# pc_badge_hrv_v1_1.net
KiCad netlist of a schematic drawn in EAGLE
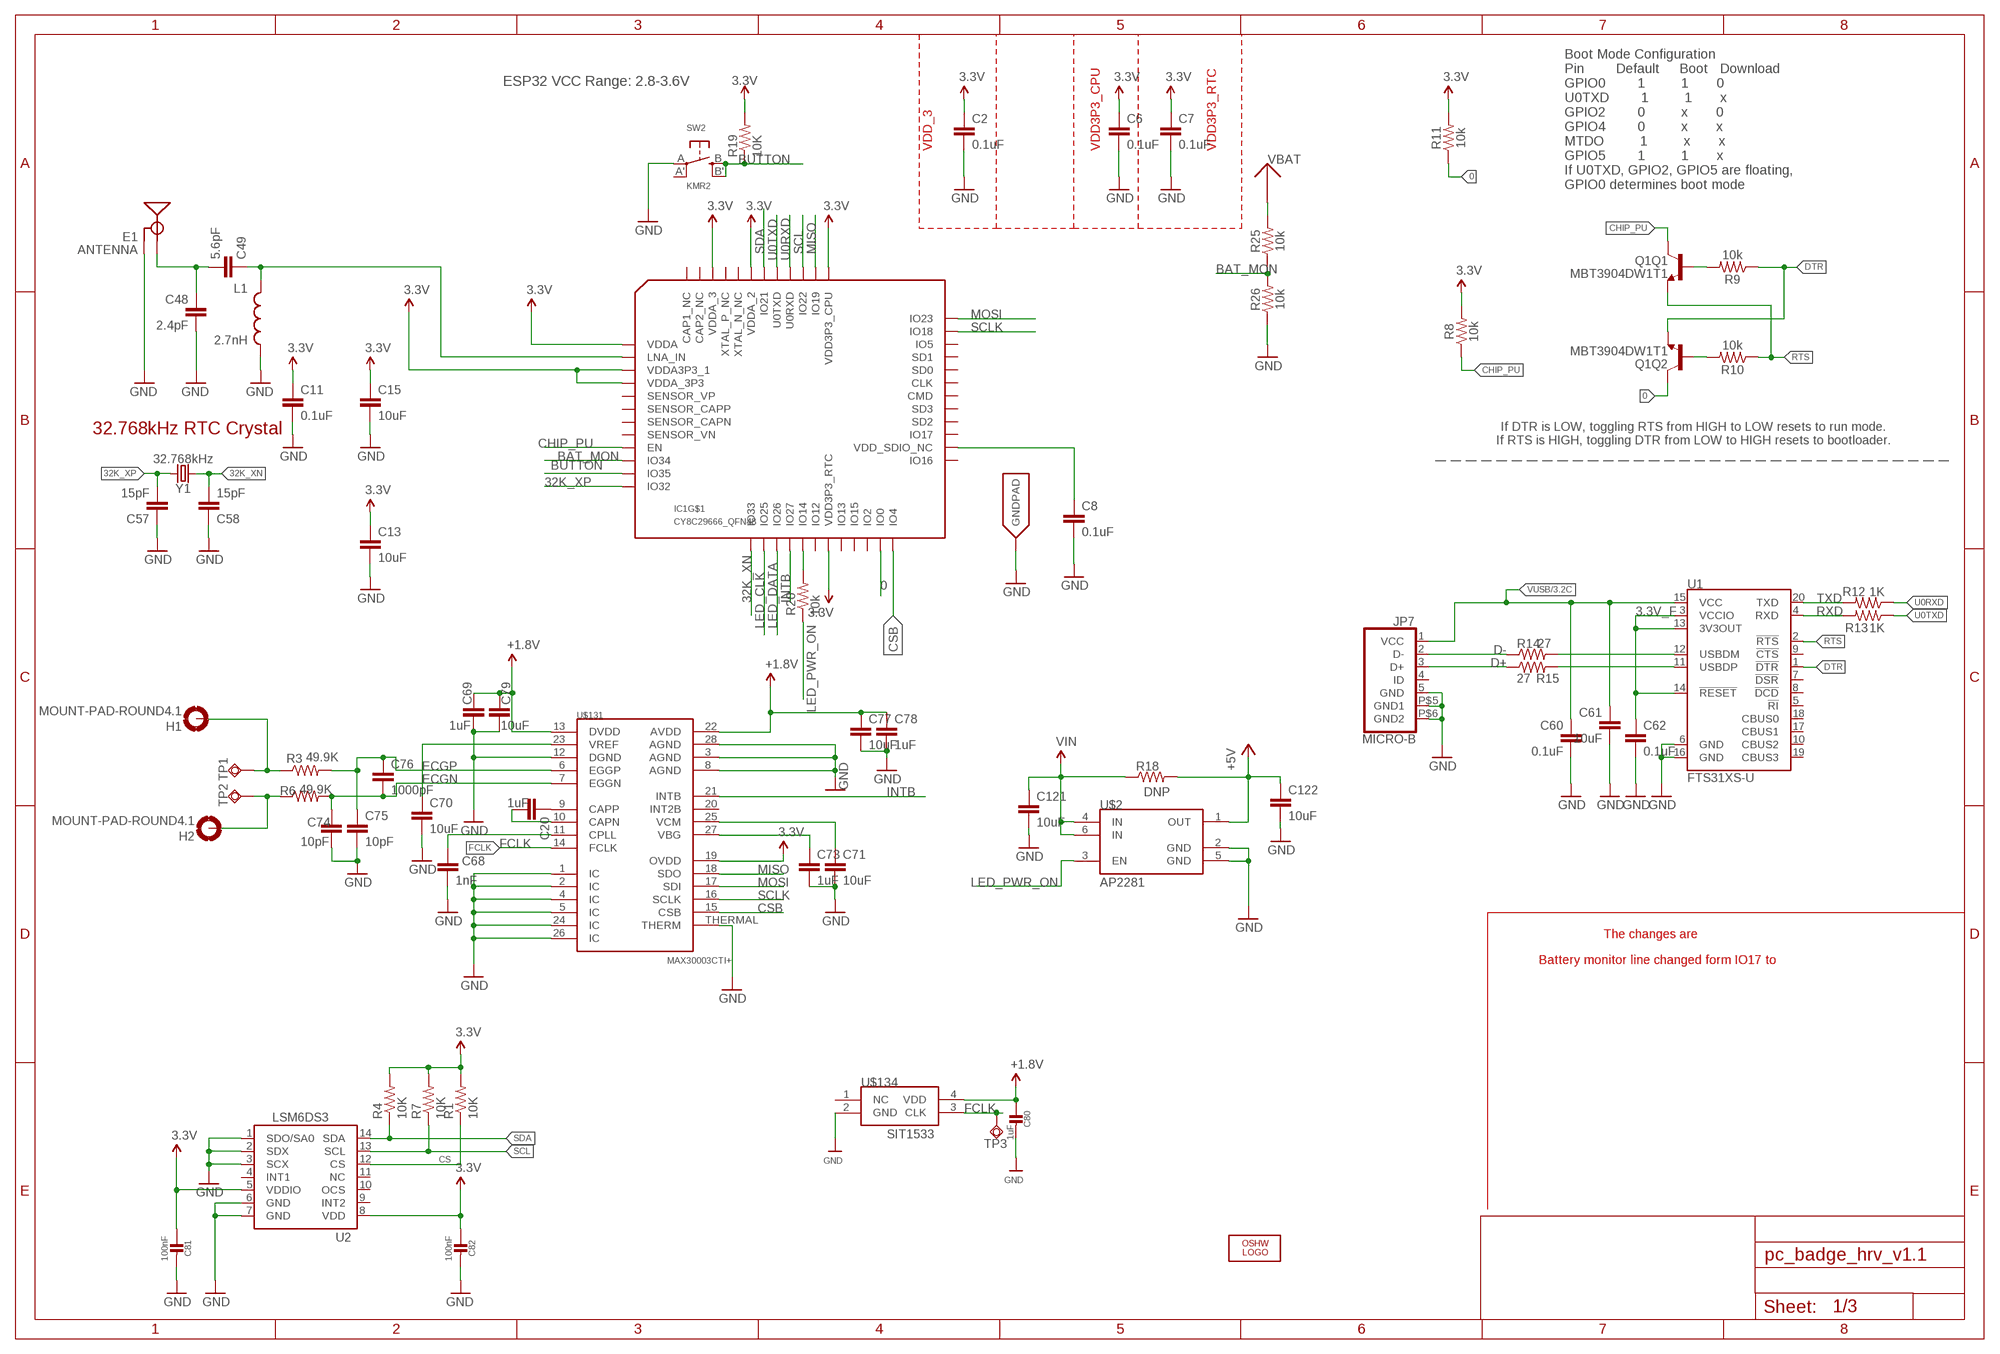
[diagram p0: schematic, sheet 1]
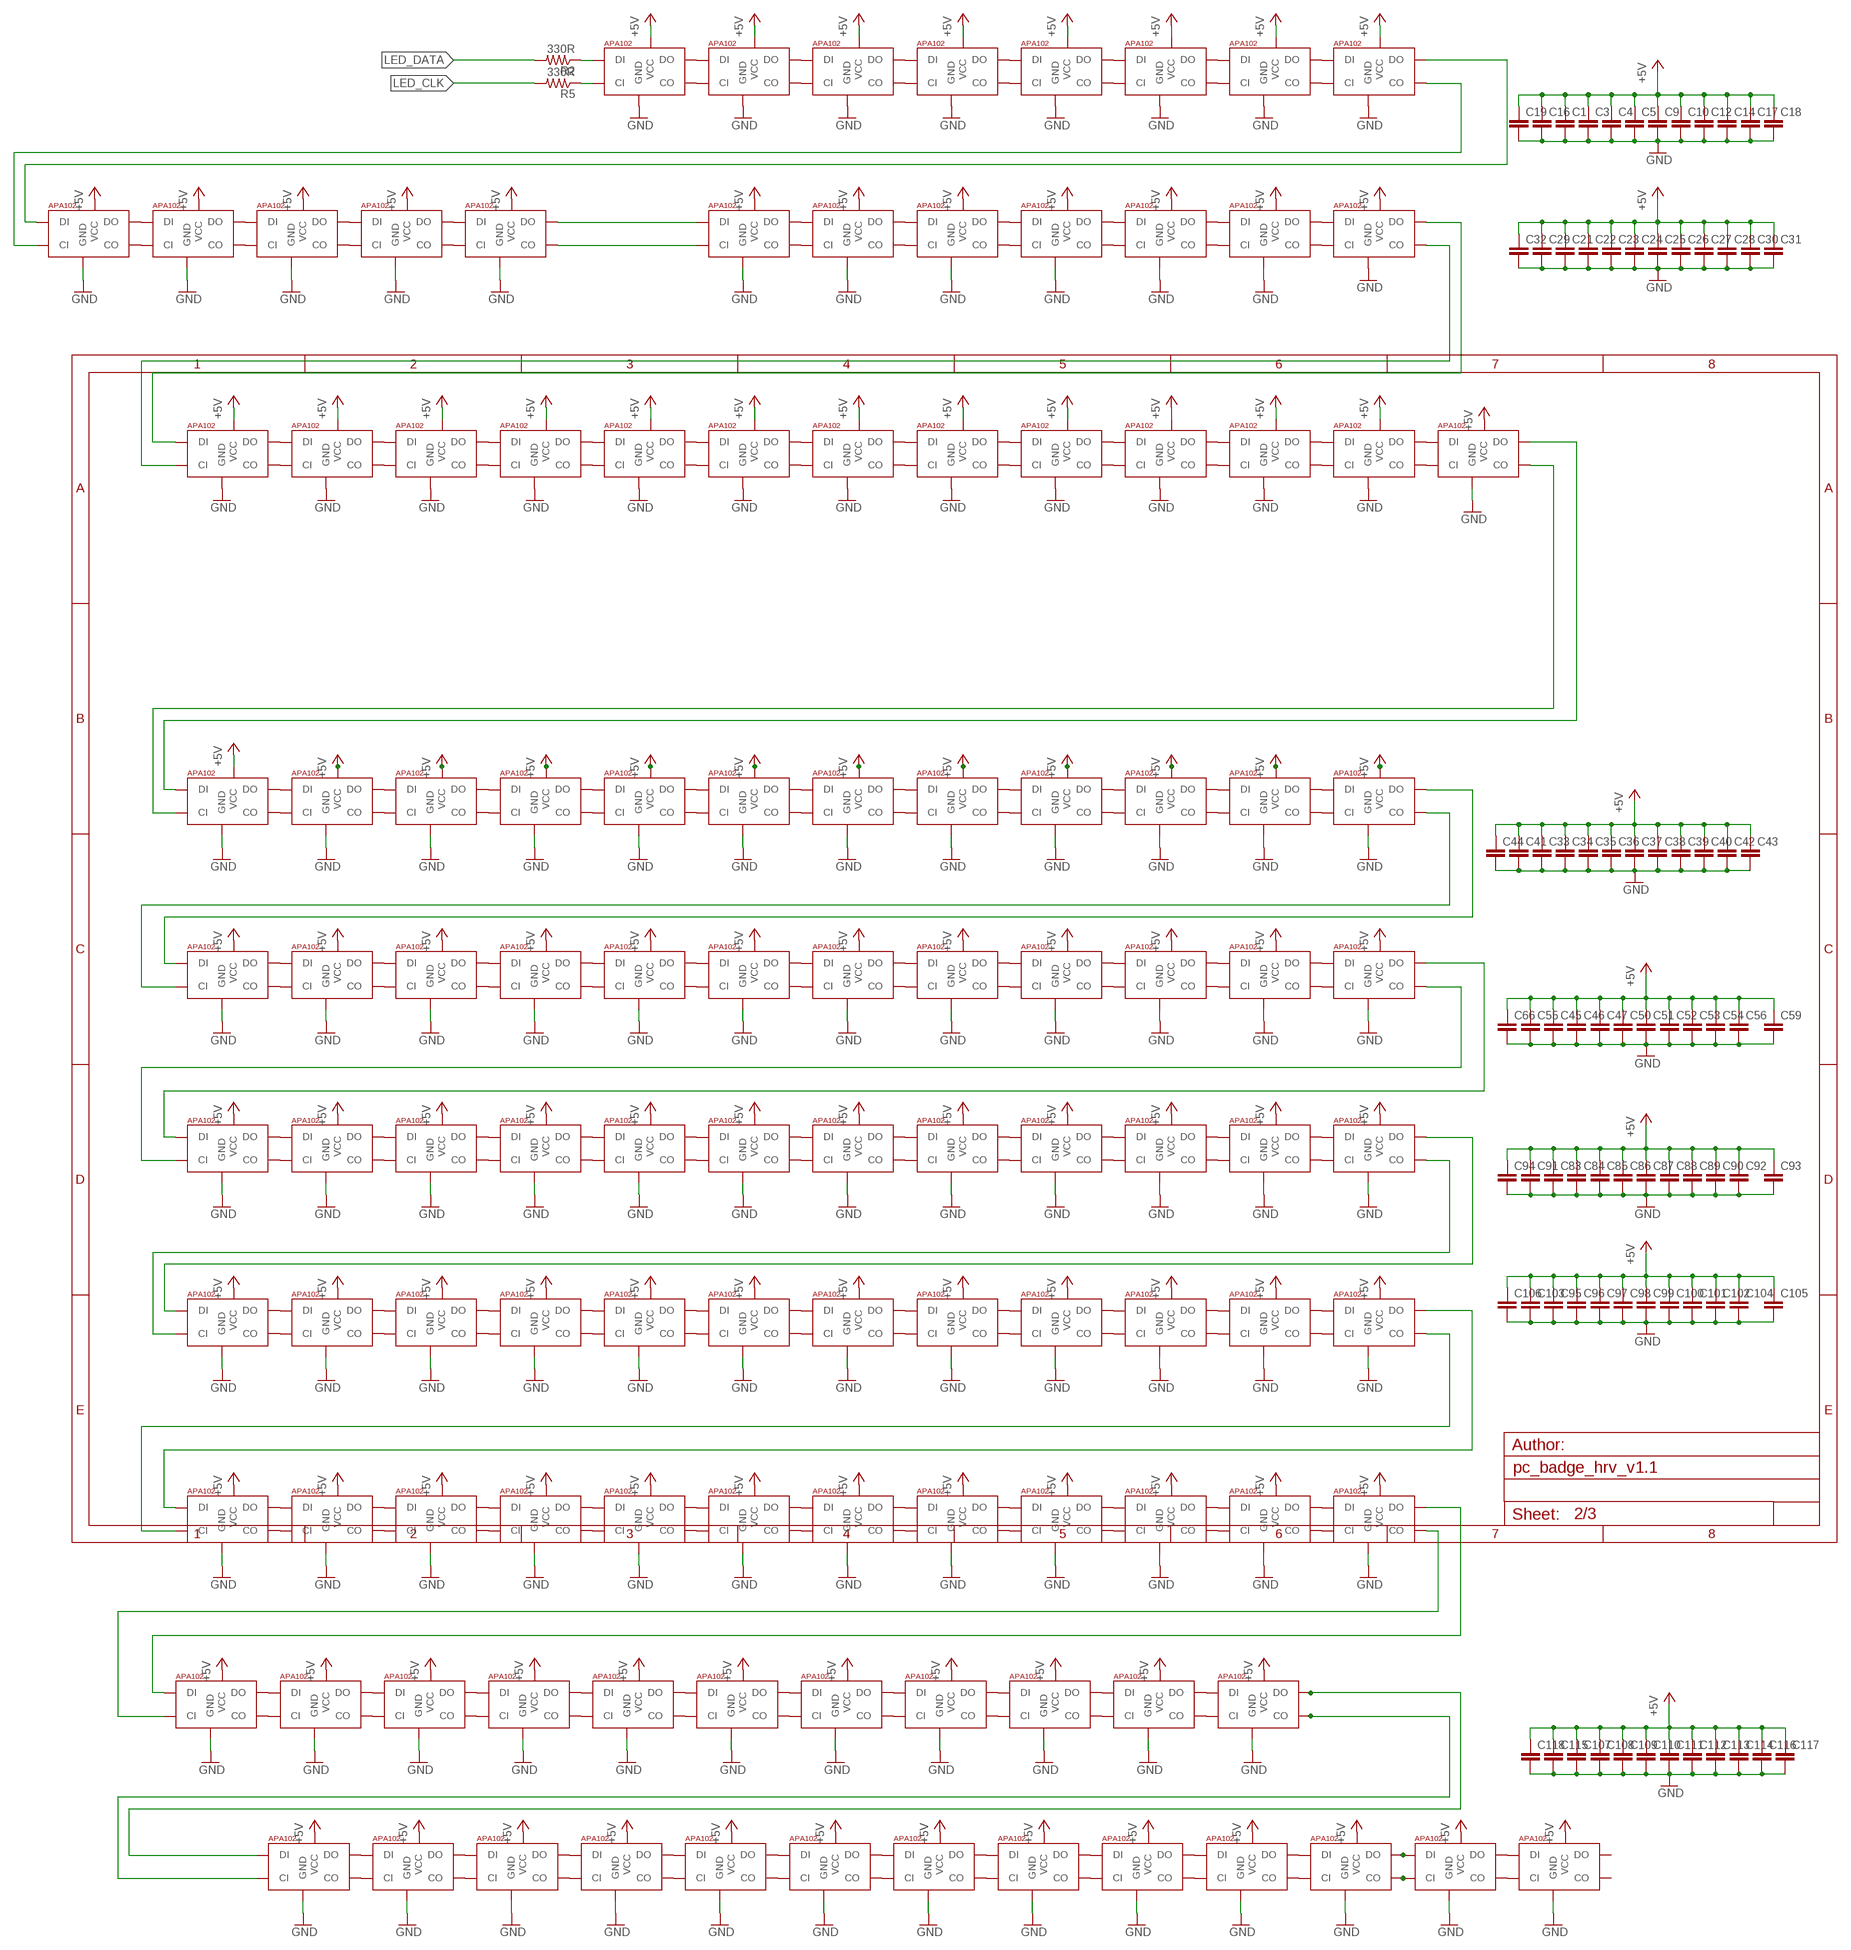
[diagram p1: schematic, sheet 2]
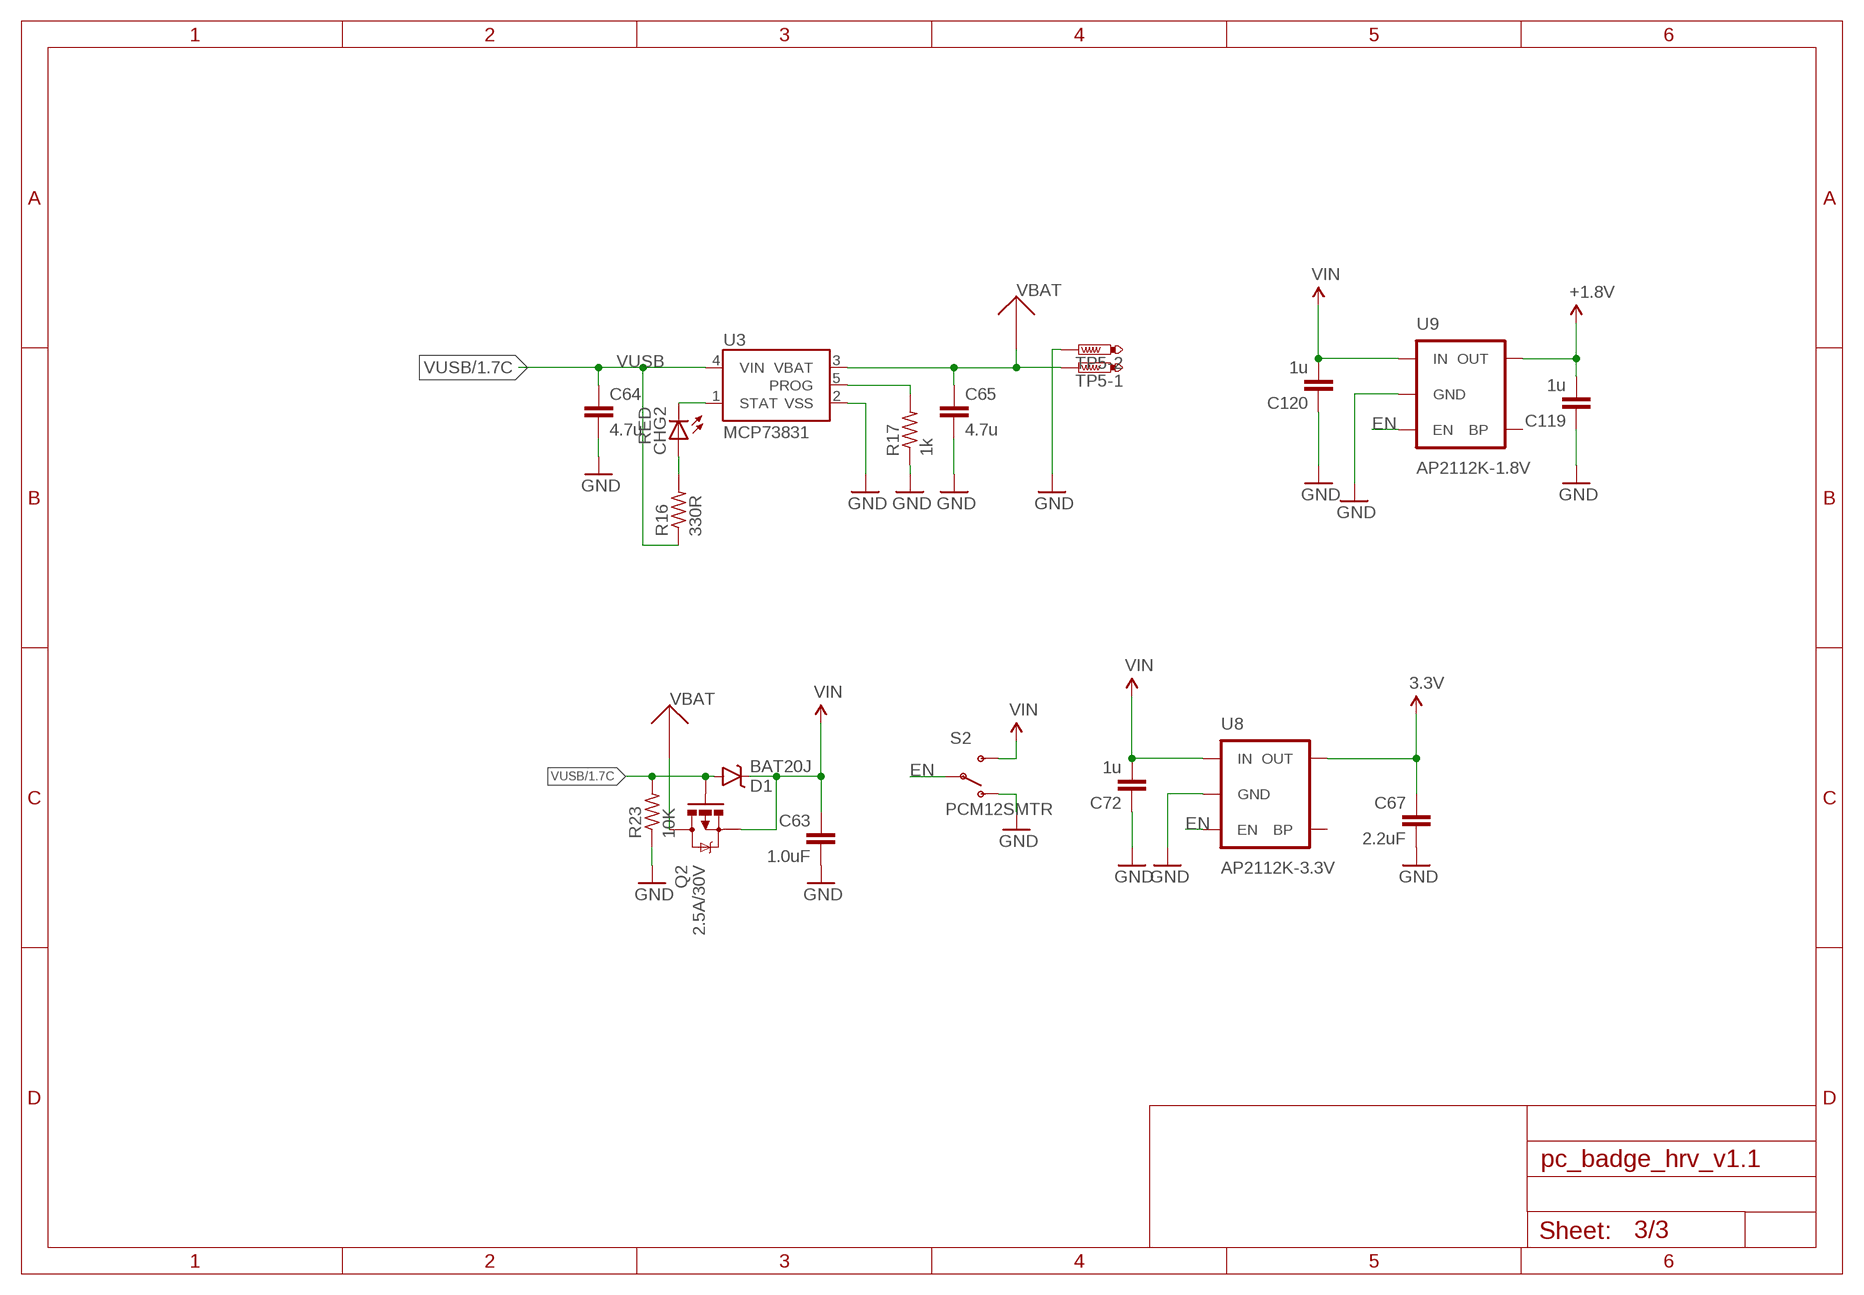
[diagram p2: schematic, sheet 3]

(export (version "E")
  (design (tool "Eeschema 10.0.6"))
  (components
    (comp (ref "C2")
      (value "0.1uF")
      (footprint "eagle-import:0402")
      (libsource (lib "eagle-import") (part "0.1UF-0402-16V-10%"))
    )
    (comp (ref "C6")
      (value "0.1uF")
      (footprint "eagle-import:0402")
      (libsource (lib "eagle-import") (part "0.1UF-0402-16V-10%"))
    )
    (comp (ref "C7")
      (value "0.1uF")
      (footprint "eagle-import:0402")
      (libsource (lib "eagle-import") (part "0.1UF-0402-16V-10%"))
    )
    (comp (ref "C8")
      (value "0.1uF")
      (footprint "eagle-import:0402")
      (libsource (lib "eagle-import") (part "0.1UF-0402-16V-10%"))
    )
    (comp (ref "C11")
      (value "0.1uF")
      (footprint "eagle-import:0402")
      (libsource (lib "eagle-import") (part "0.1UF-0402-16V-10%"))
    )
    (comp (ref "C13")
      (value "10uF")
      (footprint "eagle-import:0603")
      (libsource (lib "eagle-import") (part "10UF-0603-6.3V-20%"))
    )
    (comp (ref "C15")
      (value "10uF")
      (footprint "eagle-import:0603")
      (libsource (lib "eagle-import") (part "10UF-0603-6.3V-20%"))
    )
    (comp (ref "C20")
      (value "1uF")
      (footprint "eagle-import:C0402")
      (libsource (lib "eagle-import") (part "C-EUC0402"))
    )
    (comp (ref "C48")
      (value "2.4pF")
      (footprint "eagle-import:0603")
      (libsource (lib "eagle-import") (part "2.4PF-0603-50V-5%"))
    )
    (comp (ref "C49")
      (value "5.6pF")
      (footprint "eagle-import:0603")
      (libsource (lib "eagle-import") (part "5.6PF-50V-5%(0603)"))
    )
    (comp (ref "C57")
      (value "15pF")
      (footprint "eagle-import:0603")
      (libsource (lib "eagle-import") (part "15PF-0603-50V-5%"))
    )
    (comp (ref "C58")
      (value "15pF")
      (footprint "eagle-import:0603")
      (libsource (lib "eagle-import") (part "15PF-0603-50V-5%"))
    )
    (comp (ref "C60")
      (value "0.1uF")
      (footprint "eagle-import:C0402")
      (libsource (lib "eagle-import") (part "C-EUC0402"))
    )
    (comp (ref "C61")
      (value "10uF")
      (footprint "eagle-import:C0805")
      (libsource (lib "eagle-import") (part "C-EUC0805"))
    )
    (comp (ref "C62")
      (value "0.1uF")
      (footprint "eagle-import:C0402")
      (libsource (lib "eagle-import") (part "C-EUC0402"))
    )
    (comp (ref "C68")
      (value "1nF")
      (footprint "eagle-import:C0402")
      (libsource (lib "eagle-import") (part "C-EUC0402"))
    )
    (comp (ref "C69")
      (value "1uF")
      (footprint "eagle-import:C0402")
      (libsource (lib "eagle-import") (part "C-EUC0402"))
    )
    (comp (ref "C70")
      (value "10uF")
      (footprint "eagle-import:C0402")
      (libsource (lib "eagle-import") (part "C-EUC0402"))
    )
    (comp (ref "C71")
      (value "10uF")
      (footprint "eagle-import:C0402")
      (libsource (lib "eagle-import") (part "C-EUC0402"))
    )
    (comp (ref "C73")
      (value "1uF")
      (footprint "eagle-import:C0402")
      (libsource (lib "eagle-import") (part "C-EUC0402"))
    )
    (comp (ref "C74")
      (value "10pF")
      (footprint "eagle-import:C0402")
      (libsource (lib "eagle-import") (part "C-EUC0402"))
    )
    (comp (ref "C75")
      (value "10pF")
      (footprint "eagle-import:C0402")
      (libsource (lib "eagle-import") (part "C-EUC0402"))
    )
    (comp (ref "C76")
      (value "1000pF")
      (footprint "eagle-import:C0402")
      (libsource (lib "eagle-import") (part "C-EUC0402"))
    )
    (comp (ref "C77")
      (value "10uF")
      (footprint "eagle-import:C0402")
      (libsource (lib "eagle-import") (part "C-EUC0402"))
    )
    (comp (ref "C78")
      (value "1uF")
      (footprint "eagle-import:C0402")
      (libsource (lib "eagle-import") (part "C-EUC0402"))
    )
    (comp (ref "C79")
      (value "10uF")
      (footprint "eagle-import:C0402")
      (libsource (lib "eagle-import") (part "C-EUC0402"))
    )
    (comp (ref "C80")
      (value "1uF")
      (footprint "eagle-import:_0402")
      (libsource (lib "eagle-import") (part "CAP_CERAMIC_0402"))
    )
    (comp (ref "C81")
      (value "100nF")
      (footprint "eagle-import:_0402")
      (libsource (lib "eagle-import") (part "CAP_CERAMIC_0402"))
    )
    (comp (ref "C82")
      (value "100nF")
      (footprint "eagle-import:_0402")
      (libsource (lib "eagle-import") (part "CAP_CERAMIC_0402"))
    )
    (comp (ref "C121")
      (value "10uF")
      (footprint "eagle-import:C0402")
      (libsource (lib "eagle-import") (part "C-EUC0402"))
    )
    (comp (ref "C122")
      (value "10uF")
      (footprint "eagle-import:C0402")
      (libsource (lib "eagle-import") (part "C-EUC0402"))
    )
    (comp (ref "E1")
      (value "ANTENNA")
      (footprint "eagle-import:TRACE_ANTENNA_2.4GHZ_25.7MM_TUNED")
      (libsource (lib "eagle-import") (part "ANTENNATRACE-TUNED"))
    )
    (comp (ref "H1")
      (value "MOUNT-PAD-ROUND4.1")
      (footprint "eagle-import:4,1-PAD")
      (libsource (lib "eagle-import") (part "MOUNT-PAD-ROUND4.1"))
    )
    (comp (ref "H2")
      (value "MOUNT-PAD-ROUND4.1")
      (footprint "eagle-import:4,1-PAD")
      (libsource (lib "eagle-import") (part "MOUNT-PAD-ROUND4.1"))
    )
    (comp (ref "IC1")
      (value "CY8C29666_QFN48")
      (footprint "eagle-import:QFN48")
      (libsource (lib "eagle-import") (part "CY8C29666_QFN48"))
    )
    (comp (ref "JP7")
      (value "MICRO-B")
      (footprint "eagle-import:MICRO-B")
      (libsource (lib "eagle-import") (part "MICRO-B"))
    )
    (comp (ref "L1")
      (value "2.7nH")
      (footprint "eagle-import:0603")
      (libsource (lib "eagle-import") (part "INDUCTOR0603"))
    )
    (comp (ref "LOGO3")
      (value "OSHW_LOGO_FILLX0200-NT")
      (footprint "eagle-import:OSHW_FILLX200_NOTEXT")
      (libsource (lib "eagle-import") (part "OSHW_LOGO_FILLX0200-NT"))
    )
    (comp (ref "Q1")
      (value "MBT3904DW1T1")
      (footprint "eagle-import:SC70-6")
      (libsource (lib "eagle-import") (part "MBT3904DW1T1"))
    )
    (comp (ref "R1")
      (value "10K")
      (footprint "eagle-import:0402-RES")
      (libsource (lib "eagle-import") (part "RESISTOR0402-RES"))
    )
    (comp (ref "R3")
      (value "49.9K")
      (footprint "eagle-import:0402-RES")
      (libsource (lib "eagle-import") (part "RESISTOR0402-RES"))
    )
    (comp (ref "R4")
      (value "10K")
      (footprint "eagle-import:0402-RES")
      (libsource (lib "eagle-import") (part "RESISTOR0402-RES"))
    )
    (comp (ref "R6")
      (value "49.9K")
      (footprint "eagle-import:0402-RES")
      (libsource (lib "eagle-import") (part "RESISTOR0402-RES"))
    )
    (comp (ref "R7")
      (value "10K")
      (footprint "eagle-import:0402-RES")
      (libsource (lib "eagle-import") (part "RESISTOR0402-RES"))
    )
    (comp (ref "R8")
      (value "10k")
      (footprint "eagle-import:0603")
      (libsource (lib "eagle-import") (part "10KOHM-1/10W-1%(0603)0603"))
    )
    (comp (ref "R9")
      (value "10k")
      (footprint "eagle-import:0603")
      (libsource (lib "eagle-import") (part "10KOHM-0603-1/10W-1%"))
    )
    (comp (ref "R10")
      (value "10k")
      (footprint "eagle-import:0603")
      (libsource (lib "eagle-import") (part "10KOHM-0603-1/10W-1%"))
    )
    (comp (ref "R11")
      (value "10k")
      (footprint "eagle-import:0603")
      (libsource (lib "eagle-import") (part "10KOHM-1/10W-1%(0603)0603"))
    )
    (comp (ref "R12")
      (value "1K")
      (footprint "eagle-import:R0402")
      (libsource (lib "eagle-import") (part "R-US_R0402"))
    )
    (comp (ref "R13")
      (value "1K")
      (footprint "eagle-import:R0402")
      (libsource (lib "eagle-import") (part "R-US_R0402"))
    )
    (comp (ref "R14")
      (value "27")
      (footprint "eagle-import:R0402")
      (libsource (lib "eagle-import") (part "R-US_R0402"))
    )
    (comp (ref "R15")
      (value "27")
      (footprint "eagle-import:R0402")
      (libsource (lib "eagle-import") (part "R-US_R0402"))
    )
    (comp (ref "R18")
      (value "DNP")
      (footprint "eagle-import:R0402")
      (libsource (lib "eagle-import") (part "R-US_R0402"))
    )
    (comp (ref "R19")
      (value "10K")
      (footprint "eagle-import:R0402")
      (libsource (lib "eagle-import") (part "R-US_R0402"))
    )
    (comp (ref "R20")
      (value "10k")
      (footprint "eagle-import:R0402")
      (libsource (lib "eagle-import") (part "R-US_R0402"))
    )
    (comp (ref "R25")
      (value "10k")
      (footprint "eagle-import:0603")
      (libsource (lib "eagle-import") (part "10KOHM-1/10W-1%(0603)0603"))
    )
    (comp (ref "R26")
      (value "10k")
      (footprint "eagle-import:0603")
      (libsource (lib "eagle-import") (part "10KOHM-1/10W-1%(0603)0603"))
    )
    (comp (ref "SW2")
      (value "KMR2")
      (footprint "eagle-import:BTN_KMR2_4.6X2.8")
      (libsource (lib "eagle-import") (part "SWITCH_TACT_SMT4.6X2.8"))
    )
    (comp (ref "TP1")
      (value "TPSQTP11R")
      (footprint "eagle-import:TP11R")
      (libsource (lib "eagle-import") (part "TPSQTP11R"))
    )
    (comp (ref "TP2")
      (value "TPSQTP11R")
      (footprint "eagle-import:TP11R")
      (libsource (lib "eagle-import") (part "TPSQTP11R"))
    )
    (comp (ref "TP3")
      (value "TPSQTP11R")
      (footprint "eagle-import:TP11R")
      (libsource (lib "eagle-import") (part "TPSQTP11R"))
    )
    (comp (ref "U$2")
      (value "AP2281")
      (footprint "eagle-import:SOT26")
      (libsource (lib "eagle-import") (part "AP2281"))
    )
    (comp (ref "U$131")
      (value "MAX30003CTI+")
      (footprint "eagle-import:QFN-28")
      (libsource (lib "eagle-import") (part "MAX30003"))
    )
    (comp (ref "U$134")
      (value "SIT1533")
      (footprint "eagle-import:SIT1533")
      (libsource (lib "eagle-import") (part "SIT1533"))
    )
    (comp (ref "U1")
      (value "FTS31XS-U")
      (footprint "eagle-import:SSOP20_L")
      (libsource (lib "eagle-import") (part "FT231XS"))
    )
    (comp (ref "U2")
      (value "LSM6DS3")
      (footprint "eagle-import:LGA14L")
      (libsource (lib "eagle-import") (part "LSM6DS3"))
    )
    (comp (ref "Y1")
      (value "32.768kHz")
      (footprint "eagle-import:CRYSTAL-SMD-3.2X1.5MM")
      (libsource (lib "eagle-import") (part "CRYSTAL-32.768KHZSMD-3.2X1.5"))
    )
    (comp (ref "C1")
      (value "C-EUC0402K")
      (footprint "eagle-import:C0402K")
      (libsource (lib "eagle-import") (part "C-EUC0402K"))
    )
    (comp (ref "C3")
      (value "C-EUC0402K")
      (footprint "eagle-import:C0402K")
      (libsource (lib "eagle-import") (part "C-EUC0402K"))
    )
    (comp (ref "C4")
      (value "C-EUC0402K")
      (footprint "eagle-import:C0402K")
      (libsource (lib "eagle-import") (part "C-EUC0402K"))
    )
    (comp (ref "C5")
      (value "C-EUC0402K")
      (footprint "eagle-import:C0402K")
      (libsource (lib "eagle-import") (part "C-EUC0402K"))
    )
    (comp (ref "C9")
      (value "C-EUC0402K")
      (footprint "eagle-import:C0402K")
      (libsource (lib "eagle-import") (part "C-EUC0402K"))
    )
    (comp (ref "C10")
      (value "C-EUC0402K")
      (footprint "eagle-import:C0402K")
      (libsource (lib "eagle-import") (part "C-EUC0402K"))
    )
    (comp (ref "C12")
      (value "C-EUC0402K")
      (footprint "eagle-import:C0402K")
      (libsource (lib "eagle-import") (part "C-EUC0402K"))
    )
    (comp (ref "C14")
      (value "C-EUC0402K")
      (footprint "eagle-import:C0402K")
      (libsource (lib "eagle-import") (part "C-EUC0402K"))
    )
    (comp (ref "C16")
      (value "C-EUC0402K")
      (footprint "eagle-import:C0402K")
      (libsource (lib "eagle-import") (part "C-EUC0402K"))
    )
    (comp (ref "C17")
      (value "C-EUC0402K")
      (footprint "eagle-import:C0402K")
      (libsource (lib "eagle-import") (part "C-EUC0402K"))
    )
    (comp (ref "C18")
      (value "C-EUC0402K")
      (footprint "eagle-import:C0402K")
      (libsource (lib "eagle-import") (part "C-EUC0402K"))
    )
    (comp (ref "C19")
      (value "C-EUC0402K")
      (footprint "eagle-import:C0402K")
      (libsource (lib "eagle-import") (part "C-EUC0402K"))
    )
    (comp (ref "C21")
      (value "C-EUC0402K")
      (footprint "eagle-import:C0402K")
      (libsource (lib "eagle-import") (part "C-EUC0402K"))
    )
    (comp (ref "C22")
      (value "C-EUC0402K")
      (footprint "eagle-import:C0402K")
      (libsource (lib "eagle-import") (part "C-EUC0402K"))
    )
    (comp (ref "C23")
      (value "C-EUC0402K")
      (footprint "eagle-import:C0402K")
      (libsource (lib "eagle-import") (part "C-EUC0402K"))
    )
    (comp (ref "C24")
      (value "C-EUC0402K")
      (footprint "eagle-import:C0402K")
      (libsource (lib "eagle-import") (part "C-EUC0402K"))
    )
    (comp (ref "C25")
      (value "C-EUC0402K")
      (footprint "eagle-import:C0402K")
      (libsource (lib "eagle-import") (part "C-EUC0402K"))
    )
    (comp (ref "C26")
      (value "C-EUC0402K")
      (footprint "eagle-import:C0402K")
      (libsource (lib "eagle-import") (part "C-EUC0402K"))
    )
    (comp (ref "C27")
      (value "C-EUC0402K")
      (footprint "eagle-import:C0402K")
      (libsource (lib "eagle-import") (part "C-EUC0402K"))
    )
    (comp (ref "C28")
      (value "C-EUC0402K")
      (footprint "eagle-import:C0402K")
      (libsource (lib "eagle-import") (part "C-EUC0402K"))
    )
    (comp (ref "C29")
      (value "C-EUC0402K")
      (footprint "eagle-import:C0402K")
      (libsource (lib "eagle-import") (part "C-EUC0402K"))
    )
    (comp (ref "C30")
      (value "C-EUC0402K")
      (footprint "eagle-import:C0402K")
      (libsource (lib "eagle-import") (part "C-EUC0402K"))
    )
    (comp (ref "C31")
      (value "C-EUC0402K")
      (footprint "eagle-import:C0402K")
      (libsource (lib "eagle-import") (part "C-EUC0402K"))
    )
    (comp (ref "C32")
      (value "C-EUC0402K")
      (footprint "eagle-import:C0402K")
      (libsource (lib "eagle-import") (part "C-EUC0402K"))
    )
    (comp (ref "C33")
      (value "C-EUC0402K")
      (footprint "eagle-import:C0402K")
      (libsource (lib "eagle-import") (part "C-EUC0402K"))
    )
    (comp (ref "C34")
      (value "C-EUC0402K")
      (footprint "eagle-import:C0402K")
      (libsource (lib "eagle-import") (part "C-EUC0402K"))
    )
    (comp (ref "C35")
      (value "C-EUC0402K")
      (footprint "eagle-import:C0402K")
      (libsource (lib "eagle-import") (part "C-EUC0402K"))
    )
    (comp (ref "C36")
      (value "C-EUC0402K")
      (footprint "eagle-import:C0402K")
      (libsource (lib "eagle-import") (part "C-EUC0402K"))
    )
    (comp (ref "C37")
      (value "C-EUC0402K")
      (footprint "eagle-import:C0402K")
      (libsource (lib "eagle-import") (part "C-EUC0402K"))
    )
    (comp (ref "C38")
      (value "C-EUC0402K")
      (footprint "eagle-import:C0402K")
      (libsource (lib "eagle-import") (part "C-EUC0402K"))
    )
    (comp (ref "C39")
      (value "C-EUC0402K")
      (footprint "eagle-import:C0402K")
      (libsource (lib "eagle-import") (part "C-EUC0402K"))
    )
    (comp (ref "C40")
      (value "C-EUC0402K")
      (footprint "eagle-import:C0402K")
      (libsource (lib "eagle-import") (part "C-EUC0402K"))
    )
    (comp (ref "C41")
      (value "C-EUC0402K")
      (footprint "eagle-import:C0402K")
      (libsource (lib "eagle-import") (part "C-EUC0402K"))
    )
    (comp (ref "C42")
      (value "C-EUC0402K")
      (footprint "eagle-import:C0402K")
      (libsource (lib "eagle-import") (part "C-EUC0402K"))
    )
    (comp (ref "C43")
      (value "C-EUC0402K")
      (footprint "eagle-import:C0402K")
      (libsource (lib "eagle-import") (part "C-EUC0402K"))
    )
    (comp (ref "C44")
      (value "C-EUC0402K")
      (footprint "eagle-import:C0402K")
      (libsource (lib "eagle-import") (part "C-EUC0402K"))
    )
    (comp (ref "C45")
      (value "C-EUC0402K")
      (footprint "eagle-import:C0402K")
      (libsource (lib "eagle-import") (part "C-EUC0402K"))
    )
    (comp (ref "C46")
      (value "C-EUC0402K")
      (footprint "eagle-import:C0402K")
      (libsource (lib "eagle-import") (part "C-EUC0402K"))
    )
    (comp (ref "C47")
      (value "C-EUC0402K")
      (footprint "eagle-import:C0402K")
      (libsource (lib "eagle-import") (part "C-EUC0402K"))
    )
    (comp (ref "C50")
      (value "C-EUC0402K")
      (footprint "eagle-import:C0402K")
      (libsource (lib "eagle-import") (part "C-EUC0402K"))
    )
    (comp (ref "C51")
      (value "C-EUC0402K")
      (footprint "eagle-import:C0402K")
      (libsource (lib "eagle-import") (part "C-EUC0402K"))
    )
    (comp (ref "C52")
      (value "C-EUC0402K")
      (footprint "eagle-import:C0402K")
      (libsource (lib "eagle-import") (part "C-EUC0402K"))
    )
    (comp (ref "C53")
      (value "C-EUC0402K")
      (footprint "eagle-import:C0402K")
      (libsource (lib "eagle-import") (part "C-EUC0402K"))
    )
    (comp (ref "C54")
      (value "C-EUC0402K")
      (footprint "eagle-import:C0402K")
      (libsource (lib "eagle-import") (part "C-EUC0402K"))
    )
    (comp (ref "C55")
      (value "C-EUC0402K")
      (footprint "eagle-import:C0402K")
      (libsource (lib "eagle-import") (part "C-EUC0402K"))
    )
    (comp (ref "C56")
      (value "C-EUC0402K")
      (footprint "eagle-import:C0402K")
      (libsource (lib "eagle-import") (part "C-EUC0402K"))
    )
    (comp (ref "C59")
      (value "C-EUC0402K")
      (footprint "eagle-import:C0402K")
      (libsource (lib "eagle-import") (part "C-EUC0402K"))
    )
    (comp (ref "C66")
      (value "C-EUC0402K")
      (footprint "eagle-import:C0402K")
      (libsource (lib "eagle-import") (part "C-EUC0402K"))
    )
    (comp (ref "C83")
      (value "C-EUC0402K")
      (footprint "eagle-import:C0402K")
      (libsource (lib "eagle-import") (part "C-EUC0402K"))
    )
    (comp (ref "C84")
      (value "C-EUC0402K")
      (footprint "eagle-import:C0402K")
      (libsource (lib "eagle-import") (part "C-EUC0402K"))
    )
    (comp (ref "C85")
      (value "C-EUC0402K")
      (footprint "eagle-import:C0402K")
      (libsource (lib "eagle-import") (part "C-EUC0402K"))
    )
    (comp (ref "C86")
      (value "C-EUC0402K")
      (footprint "eagle-import:C0402K")
      (libsource (lib "eagle-import") (part "C-EUC0402K"))
    )
    (comp (ref "C87")
      (value "C-EUC0402K")
      (footprint "eagle-import:C0402K")
      (libsource (lib "eagle-import") (part "C-EUC0402K"))
    )
    (comp (ref "C88")
      (value "C-EUC0402K")
      (footprint "eagle-import:C0402K")
      (libsource (lib "eagle-import") (part "C-EUC0402K"))
    )
    (comp (ref "C89")
      (value "C-EUC0402K")
      (footprint "eagle-import:C0402K")
      (libsource (lib "eagle-import") (part "C-EUC0402K"))
    )
    (comp (ref "C90")
      (value "C-EUC0402K")
      (footprint "eagle-import:C0402K")
      (libsource (lib "eagle-import") (part "C-EUC0402K"))
    )
    (comp (ref "C91")
      (value "C-EUC0402K")
      (footprint "eagle-import:C0402K")
      (libsource (lib "eagle-import") (part "C-EUC0402K"))
    )
    (comp (ref "C92")
      (value "C-EUC0402K")
      (footprint "eagle-import:C0402K")
      (libsource (lib "eagle-import") (part "C-EUC0402K"))
    )
    (comp (ref "C93")
      (value "C-EUC0402K")
      (footprint "eagle-import:C0402K")
      (libsource (lib "eagle-import") (part "C-EUC0402K"))
    )
    (comp (ref "C94")
      (value "C-EUC0402K")
      (footprint "eagle-import:C0402K")
      (libsource (lib "eagle-import") (part "C-EUC0402K"))
    )
    (comp (ref "C95")
      (value "C-EUC0402K")
      (footprint "eagle-import:C0402K")
      (libsource (lib "eagle-import") (part "C-EUC0402K"))
    )
    (comp (ref "C96")
      (value "C-EUC0402K")
      (footprint "eagle-import:C0402K")
      (libsource (lib "eagle-import") (part "C-EUC0402K"))
    )
    (comp (ref "C97")
      (value "C-EUC0402K")
      (footprint "eagle-import:C0402K")
      (libsource (lib "eagle-import") (part "C-EUC0402K"))
    )
    (comp (ref "C98")
      (value "C-EUC0402K")
      (footprint "eagle-import:C0402K")
      (libsource (lib "eagle-import") (part "C-EUC0402K"))
    )
    (comp (ref "C99")
      (value "C-EUC0402K")
      (footprint "eagle-import:C0402K")
      (libsource (lib "eagle-import") (part "C-EUC0402K"))
    )
    (comp (ref "C100")
      (value "C-EUC0402K")
      (footprint "eagle-import:C0402K")
      (libsource (lib "eagle-import") (part "C-EUC0402K"))
    )
    (comp (ref "C101")
      (value "C-EUC0402K")
      (footprint "eagle-import:C0402K")
      (libsource (lib "eagle-import") (part "C-EUC0402K"))
    )
    (comp (ref "C102")
      (value "C-EUC0402K")
      (footprint "eagle-import:C0402K")
      (libsource (lib "eagle-import") (part "C-EUC0402K"))
    )
    (comp (ref "C103")
      (value "C-EUC0402K")
      (footprint "eagle-import:C0402K")
      (libsource (lib "eagle-import") (part "C-EUC0402K"))
    )
    (comp (ref "C104")
      (value "C-EUC0402K")
      (footprint "eagle-import:C0402K")
      (libsource (lib "eagle-import") (part "C-EUC0402K"))
    )
    (comp (ref "C105")
      (value "C-EUC0402K")
      (footprint "eagle-import:C0402K")
      (libsource (lib "eagle-import") (part "C-EUC0402K"))
    )
    (comp (ref "C106")
      (value "C-EUC0402K")
      (footprint "eagle-import:C0402K")
      (libsource (lib "eagle-import") (part "C-EUC0402K"))
    )
    (comp (ref "C107")
      (value "C-EUC0402K")
      (footprint "eagle-import:C0402K")
      (libsource (lib "eagle-import") (part "C-EUC0402K"))
    )
    (comp (ref "C108")
      (value "C-EUC0402K")
      (footprint "eagle-import:C0402K")
      (libsource (lib "eagle-import") (part "C-EUC0402K"))
    )
    (comp (ref "C109")
      (value "C-EUC0402K")
      (footprint "eagle-import:C0402K")
      (libsource (lib "eagle-import") (part "C-EUC0402K"))
    )
    (comp (ref "C110")
      (value "C-EUC0402K")
      (footprint "eagle-import:C0402K")
      (libsource (lib "eagle-import") (part "C-EUC0402K"))
    )
    (comp (ref "C111")
      (value "C-EUC0402K")
      (footprint "eagle-import:C0402K")
      (libsource (lib "eagle-import") (part "C-EUC0402K"))
    )
    (comp (ref "C112")
      (value "C-EUC0402K")
      (footprint "eagle-import:C0402K")
      (libsource (lib "eagle-import") (part "C-EUC0402K"))
    )
    (comp (ref "C113")
      (value "C-EUC0402K")
      (footprint "eagle-import:C0402K")
      (libsource (lib "eagle-import") (part "C-EUC0402K"))
    )
    (comp (ref "C114")
      (value "C-EUC0402K")
      (footprint "eagle-import:C0402K")
      (libsource (lib "eagle-import") (part "C-EUC0402K"))
    )
    (comp (ref "C115")
      (value "C-EUC0402K")
      (footprint "eagle-import:C0402K")
      (libsource (lib "eagle-import") (part "C-EUC0402K"))
    )
    (comp (ref "C116")
      (value "C-EUC0402K")
      (footprint "eagle-import:C0402K")
      (libsource (lib "eagle-import") (part "C-EUC0402K"))
    )
    (comp (ref "C117")
      (value "C-EUC0402K")
      (footprint "eagle-import:C0402K")
      (libsource (lib "eagle-import") (part "C-EUC0402K"))
    )
    (comp (ref "C118")
      (value "C-EUC0402K")
      (footprint "eagle-import:C0402K")
      (libsource (lib "eagle-import") (part "C-EUC0402K"))
    )
    (comp (ref "R2")
      (value "330R")
      (footprint "eagle-import:R0402")
      (libsource (lib "eagle-import") (part "R-US_R0402"))
    )
    (comp (ref "R5")
      (value "330R")
      (footprint "eagle-import:R0402")
      (libsource (lib "eagle-import") (part "R-US_R0402"))
    )
    (comp (ref "U$9")
      (value "APA1022020")
      (footprint "eagle-import:APA102_2020")
      (libsource (lib "eagle-import") (part "APA1022020"))
    )
    (comp (ref "U$10")
      (value "APA1022020")
      (footprint "eagle-import:APA102_2020")
      (libsource (lib "eagle-import") (part "APA1022020"))
    )
    (comp (ref "U$11")
      (value "APA1022020")
      (footprint "eagle-import:APA102_2020")
      (libsource (lib "eagle-import") (part "APA1022020"))
    )
    (comp (ref "U$12")
      (value "APA1022020")
      (footprint "eagle-import:APA102_2020")
      (libsource (lib "eagle-import") (part "APA1022020"))
    )
    (comp (ref "U$13")
      (value "APA1022020")
      (footprint "eagle-import:APA102_2020")
      (libsource (lib "eagle-import") (part "APA1022020"))
    )
    (comp (ref "U$14")
      (value "APA1022020")
      (footprint "eagle-import:APA102_2020")
      (libsource (lib "eagle-import") (part "APA1022020"))
    )
    (comp (ref "U$15")
      (value "APA1022020")
      (footprint "eagle-import:APA102_2020")
      (libsource (lib "eagle-import") (part "APA1022020"))
    )
    (comp (ref "U$18")
      (value "APA1022020")
      (footprint "eagle-import:APA102_2020")
      (libsource (lib "eagle-import") (part "APA1022020"))
    )
    (comp (ref "U$19")
      (value "APA1022020")
      (footprint "eagle-import:APA102_2020")
      (libsource (lib "eagle-import") (part "APA1022020"))
    )
    (comp (ref "U$20")
      (value "APA1022020")
      (footprint "eagle-import:APA102_2020")
      (libsource (lib "eagle-import") (part "APA1022020"))
    )
    (comp (ref "U$21")
      (value "APA1022020")
      (footprint "eagle-import:APA102_2020")
      (libsource (lib "eagle-import") (part "APA1022020"))
    )
    (comp (ref "U$22")
      (value "APA1022020")
      (footprint "eagle-import:APA102_2020")
      (libsource (lib "eagle-import") (part "APA1022020"))
    )
    (comp (ref "U$24")
      (value "APA1022020")
      (footprint "eagle-import:APA102_2020")
      (libsource (lib "eagle-import") (part "APA1022020"))
    )
    (comp (ref "U$25")
      (value "APA1022020")
      (footprint "eagle-import:APA102_2020")
      (libsource (lib "eagle-import") (part "APA1022020"))
    )
    (comp (ref "U$27")
      (value "APA1022020")
      (footprint "eagle-import:APA102_2020")
      (libsource (lib "eagle-import") (part "APA1022020"))
    )
    (comp (ref "U$28")
      (value "APA1022020")
      (footprint "eagle-import:APA102_2020")
      (libsource (lib "eagle-import") (part "APA1022020"))
    )
    (comp (ref "U$29")
      (value "APA1022020")
      (footprint "eagle-import:APA102_2020")
      (libsource (lib "eagle-import") (part "APA1022020"))
    )
    (comp (ref "U$30")
      (value "APA1022020")
      (footprint "eagle-import:APA102_2020")
      (libsource (lib "eagle-import") (part "APA1022020"))
    )
    (comp (ref "U$31")
      (value "APA1022020")
      (footprint "eagle-import:APA102_2020")
      (libsource (lib "eagle-import") (part "APA1022020"))
    )
    (comp (ref "U$32")
      (value "APA1022020")
      (footprint "eagle-import:APA102_2020")
      (libsource (lib "eagle-import") (part "APA1022020"))
    )
    (comp (ref "U$33")
      (value "APA1022020")
      (footprint "eagle-import:APA102_2020")
      (libsource (lib "eagle-import") (part "APA1022020"))
    )
    (comp (ref "U$34")
      (value "APA1022020")
      (footprint "eagle-import:APA102_2020")
      (libsource (lib "eagle-import") (part "APA1022020"))
    )
    (comp (ref "U$35")
      (value "APA1022020")
      (footprint "eagle-import:APA102_2020")
      (libsource (lib "eagle-import") (part "APA1022020"))
    )
    (comp (ref "U$36")
      (value "APA1022020")
      (footprint "eagle-import:APA102_2020")
      (libsource (lib "eagle-import") (part "APA1022020"))
    )
    (comp (ref "U$37")
      (value "APA1022020")
      (footprint "eagle-import:APA102_2020")
      (libsource (lib "eagle-import") (part "APA1022020"))
    )
    (comp (ref "U$38")
      (value "APA1022020")
      (footprint "eagle-import:APA102_2020")
      (libsource (lib "eagle-import") (part "APA1022020"))
    )
    (comp (ref "U$39")
      (value "APA1022020")
      (footprint "eagle-import:APA102_2020")
      (libsource (lib "eagle-import") (part "APA1022020"))
    )
    (comp (ref "U$40")
      (value "APA1022020")
      (footprint "eagle-import:APA102_2020")
      (libsource (lib "eagle-import") (part "APA1022020"))
    )
    (comp (ref "U$41")
      (value "APA1022020")
      (footprint "eagle-import:APA102_2020")
      (libsource (lib "eagle-import") (part "APA1022020"))
    )
    (comp (ref "U$42")
      (value "APA1022020")
      (footprint "eagle-import:APA102_2020")
      (libsource (lib "eagle-import") (part "APA1022020"))
    )
    (comp (ref "U$43")
      (value "APA1022020")
      (footprint "eagle-import:APA102_2020")
      (libsource (lib "eagle-import") (part "APA1022020"))
    )
    (comp (ref "U$44")
      (value "APA1022020")
      (footprint "eagle-import:APA102_2020")
      (libsource (lib "eagle-import") (part "APA1022020"))
    )
    (comp (ref "U$45")
      (value "APA1022020")
      (footprint "eagle-import:APA102_2020")
      (libsource (lib "eagle-import") (part "APA1022020"))
    )
    (comp (ref "U$46")
      (value "APA1022020")
      (footprint "eagle-import:APA102_2020")
      (libsource (lib "eagle-import") (part "APA1022020"))
    )
    (comp (ref "U$47")
      (value "APA1022020")
      (footprint "eagle-import:APA102_2020")
      (libsource (lib "eagle-import") (part "APA1022020"))
    )
    (comp (ref "U$48")
      (value "APA1022020")
      (footprint "eagle-import:APA102_2020")
      (libsource (lib "eagle-import") (part "APA1022020"))
    )
    (comp (ref "U$49")
      (value "APA1022020")
      (footprint "eagle-import:APA102_2020")
      (libsource (lib "eagle-import") (part "APA1022020"))
    )
    (comp (ref "U$50")
      (value "APA1022020")
      (footprint "eagle-import:APA102_2020")
      (libsource (lib "eagle-import") (part "APA1022020"))
    )
    (comp (ref "U$51")
      (value "APA1022020")
      (footprint "eagle-import:APA102_2020")
      (libsource (lib "eagle-import") (part "APA1022020"))
    )
    (comp (ref "U$52")
      (value "APA1022020")
      (footprint "eagle-import:APA102_2020")
      (libsource (lib "eagle-import") (part "APA1022020"))
    )
    (comp (ref "U$53")
      (value "APA1022020")
      (footprint "eagle-import:APA102_2020")
      (libsource (lib "eagle-import") (part "APA1022020"))
    )
    (comp (ref "U$54")
      (value "APA1022020")
      (footprint "eagle-import:APA102_2020")
      (libsource (lib "eagle-import") (part "APA1022020"))
    )
    (comp (ref "U$55")
      (value "APA1022020")
      (footprint "eagle-import:APA102_2020")
      (libsource (lib "eagle-import") (part "APA1022020"))
    )
    (comp (ref "U$56")
      (value "APA1022020")
      (footprint "eagle-import:APA102_2020")
      (libsource (lib "eagle-import") (part "APA1022020"))
    )
    (comp (ref "U$57")
      (value "APA1022020")
      (footprint "eagle-import:APA102_2020")
      (libsource (lib "eagle-import") (part "APA1022020"))
    )
    (comp (ref "U$58")
      (value "APA1022020")
      (footprint "eagle-import:APA102_2020")
      (libsource (lib "eagle-import") (part "APA1022020"))
    )
    (comp (ref "U$59")
      (value "APA1022020")
      (footprint "eagle-import:APA102_2020")
      (libsource (lib "eagle-import") (part "APA1022020"))
    )
    (comp (ref "U$60")
      (value "APA1022020")
      (footprint "eagle-import:APA102_2020")
      (libsource (lib "eagle-import") (part "APA1022020"))
    )
    (comp (ref "U$61")
      (value "APA1022020")
      (footprint "eagle-import:APA102_2020")
      (libsource (lib "eagle-import") (part "APA1022020"))
    )
    (comp (ref "U$62")
      (value "APA1022020")
      (footprint "eagle-import:APA102_2020")
      (libsource (lib "eagle-import") (part "APA1022020"))
    )
    (comp (ref "U$63")
      (value "APA1022020")
      (footprint "eagle-import:APA102_2020")
      (libsource (lib "eagle-import") (part "APA1022020"))
    )
    (comp (ref "U$64")
      (value "APA1022020")
      (footprint "eagle-import:APA102_2020")
      (libsource (lib "eagle-import") (part "APA1022020"))
    )
    (comp (ref "U$65")
      (value "APA1022020")
      (footprint "eagle-import:APA102_2020")
      (libsource (lib "eagle-import") (part "APA1022020"))
    )
    (comp (ref "U$66")
      (value "APA1022020")
      (footprint "eagle-import:APA102_2020")
      (libsource (lib "eagle-import") (part "APA1022020"))
    )
    (comp (ref "U$67")
      (value "APA1022020")
      (footprint "eagle-import:APA102_2020")
      (libsource (lib "eagle-import") (part "APA1022020"))
    )
    (comp (ref "U$68")
      (value "APA1022020")
      (footprint "eagle-import:APA102_2020")
      (libsource (lib "eagle-import") (part "APA1022020"))
    )
    (comp (ref "U$69")
      (value "APA1022020")
      (footprint "eagle-import:APA102_2020")
      (libsource (lib "eagle-import") (part "APA1022020"))
    )
    (comp (ref "U$70")
      (value "APA1022020")
      (footprint "eagle-import:APA102_2020")
      (libsource (lib "eagle-import") (part "APA1022020"))
    )
    (comp (ref "U$71")
      (value "APA1022020")
      (footprint "eagle-import:APA102_2020")
      (libsource (lib "eagle-import") (part "APA1022020"))
    )
    (comp (ref "U$72")
      (value "APA1022020")
      (footprint "eagle-import:APA102_2020")
      (libsource (lib "eagle-import") (part "APA1022020"))
    )
    (comp (ref "U$73")
      (value "APA1022020")
      (footprint "eagle-import:APA102_2020")
      (libsource (lib "eagle-import") (part "APA1022020"))
    )
    (comp (ref "U$74")
      (value "APA1022020")
      (footprint "eagle-import:APA102_2020")
      (libsource (lib "eagle-import") (part "APA1022020"))
    )
    (comp (ref "U$75")
      (value "APA1022020")
      (footprint "eagle-import:APA102_2020")
      (libsource (lib "eagle-import") (part "APA1022020"))
    )
    (comp (ref "U$76")
      (value "APA1022020")
      (footprint "eagle-import:APA102_2020")
      (libsource (lib "eagle-import") (part "APA1022020"))
    )
    (comp (ref "U$77")
      (value "APA1022020")
      (footprint "eagle-import:APA102_2020")
      (libsource (lib "eagle-import") (part "APA1022020"))
    )
    (comp (ref "U$78")
      (value "APA1022020")
      (footprint "eagle-import:APA102_2020")
      (libsource (lib "eagle-import") (part "APA1022020"))
    )
    (comp (ref "U$79")
      (value "APA1022020")
      (footprint "eagle-import:APA102_2020")
      (libsource (lib "eagle-import") (part "APA1022020"))
    )
    (comp (ref "U$80")
      (value "APA1022020")
      (footprint "eagle-import:APA102_2020")
      (libsource (lib "eagle-import") (part "APA1022020"))
    )
    (comp (ref "U$81")
      (value "APA1022020")
      (footprint "eagle-import:APA102_2020")
      (libsource (lib "eagle-import") (part "APA1022020"))
    )
    (comp (ref "U$82")
      (value "APA1022020")
      (footprint "eagle-import:APA102_2020")
      (libsource (lib "eagle-import") (part "APA1022020"))
    )
    (comp (ref "U$83")
      (value "APA1022020")
      (footprint "eagle-import:APA102_2020")
      (libsource (lib "eagle-import") (part "APA1022020"))
    )
    (comp (ref "U$84")
      (value "APA1022020")
      (footprint "eagle-import:APA102_2020")
      (libsource (lib "eagle-import") (part "APA1022020"))
    )
    (comp (ref "U$85")
      (value "APA1022020")
      (footprint "eagle-import:APA102_2020")
      (libsource (lib "eagle-import") (part "APA1022020"))
    )
    (comp (ref "U$86")
      (value "APA1022020")
      (footprint "eagle-import:APA102_2020")
      (libsource (lib "eagle-import") (part "APA1022020"))
    )
    (comp (ref "U$87")
      (value "APA1022020")
      (footprint "eagle-import:APA102_2020")
      (libsource (lib "eagle-import") (part "APA1022020"))
    )
    (comp (ref "U$88")
      (value "APA1022020")
      (footprint "eagle-import:APA102_2020")
      (libsource (lib "eagle-import") (part "APA1022020"))
    )
    (comp (ref "U$89")
      (value "APA1022020")
      (footprint "eagle-import:APA102_2020")
      (libsource (lib "eagle-import") (part "APA1022020"))
    )
    (comp (ref "U$90")
      (value "APA1022020")
      (footprint "eagle-import:APA102_2020")
      (libsource (lib "eagle-import") (part "APA1022020"))
    )
    (comp (ref "U$91")
      (value "APA1022020")
      (footprint "eagle-import:APA102_2020")
      (libsource (lib "eagle-import") (part "APA1022020"))
    )
    (comp (ref "U$92")
      (value "APA1022020")
      (footprint "eagle-import:APA102_2020")
      (libsource (lib "eagle-import") (part "APA1022020"))
    )
    (comp (ref "U$93")
      (value "APA1022020")
      (footprint "eagle-import:APA102_2020")
      (libsource (lib "eagle-import") (part "APA1022020"))
    )
    (comp (ref "U$94")
      (value "APA1022020")
      (footprint "eagle-import:APA102_2020")
      (libsource (lib "eagle-import") (part "APA1022020"))
    )
    (comp (ref "U$95")
      (value "APA1022020")
      (footprint "eagle-import:APA102_2020")
      (libsource (lib "eagle-import") (part "APA1022020"))
    )
    (comp (ref "U$96")
      (value "APA1022020")
      (footprint "eagle-import:APA102_2020")
      (libsource (lib "eagle-import") (part "APA1022020"))
    )
    (comp (ref "U$97")
      (value "APA1022020")
      (footprint "eagle-import:APA102_2020")
      (libsource (lib "eagle-import") (part "APA1022020"))
    )
    (comp (ref "U$98")
      (value "APA1022020")
      (footprint "eagle-import:APA102_2020")
      (libsource (lib "eagle-import") (part "APA1022020"))
    )
    (comp (ref "U$99")
      (value "APA1022020")
      (footprint "eagle-import:APA102_2020")
      (libsource (lib "eagle-import") (part "APA1022020"))
    )
    (comp (ref "U$100")
      (value "APA1022020")
      (footprint "eagle-import:APA102_2020")
      (libsource (lib "eagle-import") (part "APA1022020"))
    )
    (comp (ref "U$101")
      (value "APA1022020")
      (footprint "eagle-import:APA102_2020")
      (libsource (lib "eagle-import") (part "APA1022020"))
    )
    (comp (ref "U$102")
      (value "APA1022020")
      (footprint "eagle-import:APA102_2020")
      (libsource (lib "eagle-import") (part "APA1022020"))
    )
    (comp (ref "U$103")
      (value "APA1022020")
      (footprint "eagle-import:APA102_2020")
      (libsource (lib "eagle-import") (part "APA1022020"))
    )
    (comp (ref "U$104")
      (value "APA1022020")
      (footprint "eagle-import:APA102_2020")
      (libsource (lib "eagle-import") (part "APA1022020"))
    )
    (comp (ref "U$106")
      (value "APA1022020")
      (footprint "eagle-import:APA102_2020")
      (libsource (lib "eagle-import") (part "APA1022020"))
    )
    (comp (ref "U$107")
      (value "APA1022020")
      (footprint "eagle-import:APA102_2020")
      (libsource (lib "eagle-import") (part "APA1022020"))
    )
    (comp (ref "U$108")
      (value "APA1022020")
      (footprint "eagle-import:APA102_2020")
      (libsource (lib "eagle-import") (part "APA1022020"))
    )
    (comp (ref "U$109")
      (value "APA1022020")
      (footprint "eagle-import:APA102_2020")
      (libsource (lib "eagle-import") (part "APA1022020"))
    )
    (comp (ref "U$110")
      (value "APA1022020")
      (footprint "eagle-import:APA102_2020")
      (libsource (lib "eagle-import") (part "APA1022020"))
    )
    (comp (ref "U$111")
      (value "APA1022020")
      (footprint "eagle-import:APA102_2020")
      (libsource (lib "eagle-import") (part "APA1022020"))
    )
    (comp (ref "U$112")
      (value "APA1022020")
      (footprint "eagle-import:APA102_2020")
      (libsource (lib "eagle-import") (part "APA1022020"))
    )
    (comp (ref "U$113")
      (value "APA1022020")
      (footprint "eagle-import:APA102_2020")
      (libsource (lib "eagle-import") (part "APA1022020"))
    )
    (comp (ref "U$114")
      (value "APA1022020")
      (footprint "eagle-import:APA102_2020")
      (libsource (lib "eagle-import") (part "APA1022020"))
    )
    (comp (ref "U$115")
      (value "APA1022020")
      (footprint "eagle-import:APA102_2020")
      (libsource (lib "eagle-import") (part "APA1022020"))
    )
    (comp (ref "U$116")
      (value "APA1022020")
      (footprint "eagle-import:APA102_2020")
      (libsource (lib "eagle-import") (part "APA1022020"))
    )
    (comp (ref "U$117")
      (value "APA1022020")
      (footprint "eagle-import:APA102_2020")
      (libsource (lib "eagle-import") (part "APA1022020"))
    )
    (comp (ref "U$118")
      (value "APA1022020")
      (footprint "eagle-import:APA102_2020")
      (libsource (lib "eagle-import") (part "APA1022020"))
    )
    (comp (ref "U$119")
      (value "APA1022020")
      (footprint "eagle-import:APA102_2020")
      (libsource (lib "eagle-import") (part "APA1022020"))
    )
    (comp (ref "U$120")
      (value "APA1022020")
      (footprint "eagle-import:APA102_2020")
      (libsource (lib "eagle-import") (part "APA1022020"))
    )
    (comp (ref "U$121")
      (value "APA1022020")
      (footprint "eagle-import:APA102_2020")
      (libsource (lib "eagle-import") (part "APA1022020"))
    )
    (comp (ref "U$122")
      (value "APA1022020")
      (footprint "eagle-import:APA102_2020")
      (libsource (lib "eagle-import") (part "APA1022020"))
    )
    (comp (ref "U$123")
      (value "APA1022020")
      (footprint "eagle-import:APA102_2020")
      (libsource (lib "eagle-import") (part "APA1022020"))
    )
    (comp (ref "U$124")
      (value "APA1022020")
      (footprint "eagle-import:APA102_2020")
      (libsource (lib "eagle-import") (part "APA1022020"))
    )
    (comp (ref "U$125")
      (value "APA1022020")
      (footprint "eagle-import:APA102_2020")
      (libsource (lib "eagle-import") (part "APA1022020"))
    )
    (comp (ref "U$126")
      (value "APA1022020")
      (footprint "eagle-import:APA102_2020")
      (libsource (lib "eagle-import") (part "APA1022020"))
    )
    (comp (ref "U$127")
      (value "APA1022020")
      (footprint "eagle-import:APA102_2020")
      (libsource (lib "eagle-import") (part "APA1022020"))
    )
    (comp (ref "U$128")
      (value "APA1022020")
      (footprint "eagle-import:APA102_2020")
      (libsource (lib "eagle-import") (part "APA1022020"))
    )
    (comp (ref "U$129")
      (value "APA1022020")
      (footprint "eagle-import:APA102_2020")
      (libsource (lib "eagle-import") (part "APA1022020"))
    )
    (comp (ref "U$130")
      (value "APA1022020")
      (footprint "eagle-import:APA102_2020")
      (libsource (lib "eagle-import") (part "APA1022020"))
    )
    (comp (ref "C63")
      (value "1.0uF")
      (footprint "eagle-import:C0402")
      (libsource (lib "eagle-import") (part "C-EUC0402"))
    )
    (comp (ref "C64")
      (value "4.7u")
      (footprint "eagle-import:C0805")
      (libsource (lib "eagle-import") (part "C-EUC0805"))
    )
    (comp (ref "C65")
      (value "4.7u")
      (footprint "eagle-import:C0805")
      (libsource (lib "eagle-import") (part "C-EUC0805"))
    )
    (comp (ref "C67")
      (value "2.2uF")
      (footprint "eagle-import:C0402")
      (libsource (lib "eagle-import") (part "C-EUC0402"))
    )
    (comp (ref "C72")
      (value "1u")
      (footprint "eagle-import:C0402")
      (libsource (lib "eagle-import") (part "C-EUC0402"))
    )
    (comp (ref "C119")
      (value "1u")
      (footprint "eagle-import:C0402")
      (libsource (lib "eagle-import") (part "C-EUC0402"))
    )
    (comp (ref "C120")
      (value "1u")
      (footprint "eagle-import:C0402")
      (libsource (lib "eagle-import") (part "C-EUC0402"))
    )
    (comp (ref "CHG2")
      (value "RED")
      (footprint "eagle-import:CHIPLED_0603")
      (libsource (lib "eagle-import") (part "LEDCHIPLED_0603"))
    )
    (comp (ref "D1")
      (value "BAT20J")
      (footprint "eagle-import:SOD-323")
      (libsource (lib "eagle-import") (part "DIODE-SCHOTTKY-BAT20J"))
    )
    (comp (ref "Q2")
      (value "2.5A/30V")
      (footprint "eagle-import:SOT23-3")
      (libsource (lib "eagle-import") (part "MOSFET-PCHANNELDMG2307L"))
    )
    (comp (ref "R16")
      (value "330R")
      (footprint "eagle-import:R0402")
      (libsource (lib "eagle-import") (part "R-US_R0402"))
    )
    (comp (ref "R17")
      (value "1k")
      (footprint "eagle-import:R0402")
      (libsource (lib "eagle-import") (part "R-US_R0402"))
    )
    (comp (ref "R23")
      (value "10K")
      (footprint "eagle-import:R0402")
      (libsource (lib "eagle-import") (part "R-US_R0402"))
    )
    (comp (ref "S2")
      (value "PCM12SMTR")
      (footprint "eagle-import:SWITCH-SPST-SMD-A")
      (libsource (lib "eagle-import") (part "SWITCH-SPDT-SMD-A"))
    )
    (comp (ref "TP5")
      (value "PTR2")
      (footprint "eagle-import:P2-38-17")
      (libsource (lib "eagle-import") (part "PTR2"))
    )
    (comp (ref "U3")
      (value "MCP73831")
      (footprint "eagle-import:SOT23-5")
      (libsource (lib "eagle-import") (part "MCP73831"))
    )
    (comp (ref "U8")
      (value "AP2112K-3.3V")
      (footprint "eagle-import:SOT23-5")
      (libsource (lib "eagle-import") (part "V_REG_LDOSMD"))
    )
    (comp (ref "U9")
      (value "AP2112K-1.8V")
      (footprint "eagle-import:SOT23-5")
      (libsource (lib "eagle-import") (part "V_REG_LDOSMD"))
    )
  )
  (nets
    (net (code "1") (name "+1.8V") (class "Default")
      (node (ref "C119") (pin "2") (pinfunction "2_2") (pintype "passive"))
      (node (ref "C69") (pin "1") (pinfunction "1_1") (pintype "passive"))
      (node (ref "C77") (pin "1") (pinfunction "1_1") (pintype "passive"))
      (node (ref "C78") (pin "1") (pinfunction "1_1") (pintype "passive"))
      (node (ref "C79") (pin "1") (pinfunction "1_1") (pintype "passive"))
      (node (ref "C80") (pin "1") (pinfunction "1_1") (pintype "passive"))
      (node (ref "U$131") (pin "13") (pinfunction "DVDD_13") (pintype "bidirectional"))
      (node (ref "U$131") (pin "22") (pinfunction "AVDD_22") (pintype "bidirectional"))
      (node (ref "U$134") (pin "4") (pinfunction "VDD_4") (pintype "bidirectional"))
      (node (ref "U9") (pin "5") (pinfunction "OUT_5") (pintype "passive"))
    )
    (net (code "2") (name "+5V") (class "Default")
      (node (ref "C1") (pin "1") (pinfunction "1_1") (pintype "passive"))
      (node (ref "C10") (pin "1") (pinfunction "1_1") (pintype "passive"))
      (node (ref "C100") (pin "1") (pinfunction "1_1") (pintype "passive"))
      (node (ref "C101") (pin "1") (pinfunction "1_1") (pintype "passive"))
      (node (ref "C102") (pin "1") (pinfunction "1_1") (pintype "passive"))
      (node (ref "C103") (pin "1") (pinfunction "1_1") (pintype "passive"))
      (node (ref "C104") (pin "1") (pinfunction "1_1") (pintype "passive"))
      (node (ref "C105") (pin "1") (pinfunction "1_1") (pintype "passive"))
      (node (ref "C106") (pin "1") (pinfunction "1_1") (pintype "passive"))
      (node (ref "C107") (pin "1") (pinfunction "1_1") (pintype "passive"))
      (node (ref "C108") (pin "1") (pinfunction "1_1") (pintype "passive"))
      (node (ref "C109") (pin "1") (pinfunction "1_1") (pintype "passive"))
      (node (ref "C110") (pin "1") (pinfunction "1_1") (pintype "passive"))
      (node (ref "C111") (pin "1") (pinfunction "1_1") (pintype "passive"))
      (node (ref "C112") (pin "1") (pinfunction "1_1") (pintype "passive"))
      (node (ref "C113") (pin "1") (pinfunction "1_1") (pintype "passive"))
      (node (ref "C114") (pin "1") (pinfunction "1_1") (pintype "passive"))
      (node (ref "C115") (pin "1") (pinfunction "1_1") (pintype "passive"))
      (node (ref "C116") (pin "1") (pinfunction "1_1") (pintype "passive"))
      (node (ref "C117") (pin "1") (pinfunction "1_1") (pintype "passive"))
      (node (ref "C118") (pin "1") (pinfunction "1_1") (pintype "passive"))
      (node (ref "C12") (pin "1") (pinfunction "1_1") (pintype "passive"))
      (node (ref "C122") (pin "1") (pinfunction "1_1") (pintype "passive"))
      (node (ref "C14") (pin "1") (pinfunction "1_1") (pintype "passive"))
      (node (ref "C16") (pin "1") (pinfunction "1_1") (pintype "passive"))
      (node (ref "C17") (pin "1") (pinfunction "1_1") (pintype "passive"))
      (node (ref "C18") (pin "1") (pinfunction "1_1") (pintype "passive"))
      (node (ref "C19") (pin "1") (pinfunction "1_1") (pintype "passive"))
      (node (ref "C21") (pin "1") (pinfunction "1_1") (pintype "passive"))
      (node (ref "C22") (pin "1") (pinfunction "1_1") (pintype "passive"))
      (node (ref "C23") (pin "1") (pinfunction "1_1") (pintype "passive"))
      (node (ref "C24") (pin "1") (pinfunction "1_1") (pintype "passive"))
      (node (ref "C25") (pin "1") (pinfunction "1_1") (pintype "passive"))
      (node (ref "C26") (pin "1") (pinfunction "1_1") (pintype "passive"))
      (node (ref "C27") (pin "1") (pinfunction "1_1") (pintype "passive"))
      (node (ref "C28") (pin "1") (pinfunction "1_1") (pintype "passive"))
      (node (ref "C29") (pin "1") (pinfunction "1_1") (pintype "passive"))
      (node (ref "C3") (pin "1") (pinfunction "1_1") (pintype "passive"))
      (node (ref "C30") (pin "1") (pinfunction "1_1") (pintype "passive"))
      (node (ref "C31") (pin "1") (pinfunction "1_1") (pintype "passive"))
      (node (ref "C32") (pin "1") (pinfunction "1_1") (pintype "passive"))
      (node (ref "C33") (pin "1") (pinfunction "1_1") (pintype "passive"))
      (node (ref "C34") (pin "1") (pinfunction "1_1") (pintype "passive"))
      (node (ref "C35") (pin "1") (pinfunction "1_1") (pintype "passive"))
      (node (ref "C36") (pin "1") (pinfunction "1_1") (pintype "passive"))
      (node (ref "C37") (pin "1") (pinfunction "1_1") (pintype "passive"))
      (node (ref "C38") (pin "1") (pinfunction "1_1") (pintype "passive"))
      (node (ref "C39") (pin "1") (pinfunction "1_1") (pintype "passive"))
      (node (ref "C4") (pin "1") (pinfunction "1_1") (pintype "passive"))
      (node (ref "C40") (pin "1") (pinfunction "1_1") (pintype "passive"))
      (node (ref "C41") (pin "1") (pinfunction "1_1") (pintype "passive"))
      (node (ref "C42") (pin "1") (pinfunction "1_1") (pintype "passive"))
      (node (ref "C43") (pin "1") (pinfunction "1_1") (pintype "passive"))
      (node (ref "C44") (pin "1") (pinfunction "1_1") (pintype "passive"))
      (node (ref "C45") (pin "1") (pinfunction "1_1") (pintype "passive"))
      (node (ref "C46") (pin "1") (pinfunction "1_1") (pintype "passive"))
      (node (ref "C47") (pin "1") (pinfunction "1_1") (pintype "passive"))
      (node (ref "C5") (pin "1") (pinfunction "1_1") (pintype "passive"))
      (node (ref "C50") (pin "1") (pinfunction "1_1") (pintype "passive"))
      (node (ref "C51") (pin "1") (pinfunction "1_1") (pintype "passive"))
      (node (ref "C52") (pin "1") (pinfunction "1_1") (pintype "passive"))
      (node (ref "C53") (pin "1") (pinfunction "1_1") (pintype "passive"))
      (node (ref "C54") (pin "1") (pinfunction "1_1") (pintype "passive"))
      (node (ref "C55") (pin "1") (pinfunction "1_1") (pintype "passive"))
      (node (ref "C56") (pin "1") (pinfunction "1_1") (pintype "passive"))
      (node (ref "C59") (pin "1") (pinfunction "1_1") (pintype "passive"))
      (node (ref "C66") (pin "1") (pinfunction "1_1") (pintype "passive"))
      (node (ref "C83") (pin "1") (pinfunction "1_1") (pintype "passive"))
      (node (ref "C84") (pin "1") (pinfunction "1_1") (pintype "passive"))
      (node (ref "C85") (pin "1") (pinfunction "1_1") (pintype "passive"))
      (node (ref "C86") (pin "1") (pinfunction "1_1") (pintype "passive"))
      (node (ref "C87") (pin "1") (pinfunction "1_1") (pintype "passive"))
      (node (ref "C88") (pin "1") (pinfunction "1_1") (pintype "passive"))
      (node (ref "C89") (pin "1") (pinfunction "1_1") (pintype "passive"))
      (node (ref "C9") (pin "1") (pinfunction "1_1") (pintype "passive"))
      (node (ref "C90") (pin "1") (pinfunction "1_1") (pintype "passive"))
      (node (ref "C91") (pin "1") (pinfunction "1_1") (pintype "passive"))
      (node (ref "C92") (pin "1") (pinfunction "1_1") (pintype "passive"))
      (node (ref "C93") (pin "1") (pinfunction "1_1") (pintype "passive"))
      (node (ref "C94") (pin "1") (pinfunction "1_1") (pintype "passive"))
      (node (ref "C95") (pin "1") (pinfunction "1_1") (pintype "passive"))
      (node (ref "C96") (pin "1") (pinfunction "1_1") (pintype "passive"))
      (node (ref "C97") (pin "1") (pinfunction "1_1") (pintype "passive"))
      (node (ref "C98") (pin "1") (pinfunction "1_1") (pintype "passive"))
      (node (ref "C99") (pin "1") (pinfunction "1_1") (pintype "passive"))
      (node (ref "R18") (pin "2") (pinfunction "2_2") (pintype "passive"))
      (node (ref "U$10") (pin "V_CC") (pinfunction "VCC_V_CC") (pintype "bidirectional"))
      (node (ref "U$100") (pin "V_CC") (pinfunction "VCC_V_CC") (pintype "bidirectional"))
      (node (ref "U$101") (pin "V_CC") (pinfunction "VCC_V_CC") (pintype "bidirectional"))
      (node (ref "U$102") (pin "V_CC") (pinfunction "VCC_V_CC") (pintype "bidirectional"))
      (node (ref "U$103") (pin "V_CC") (pinfunction "VCC_V_CC") (pintype "bidirectional"))
      (node (ref "U$104") (pin "V_CC") (pinfunction "VCC_V_CC") (pintype "bidirectional"))
      (node (ref "U$106") (pin "V_CC") (pinfunction "VCC_V_CC") (pintype "bidirectional"))
      (node (ref "U$107") (pin "V_CC") (pinfunction "VCC_V_CC") (pintype "bidirectional"))
      (node (ref "U$108") (pin "V_CC") (pinfunction "VCC_V_CC") (pintype "bidirectional"))
      (node (ref "U$109") (pin "V_CC") (pinfunction "VCC_V_CC") (pintype "bidirectional"))
      (node (ref "U$11") (pin "V_CC") (pinfunction "VCC_V_CC") (pintype "bidirectional"))
      (node (ref "U$110") (pin "V_CC") (pinfunction "VCC_V_CC") (pintype "bidirectional"))
      (node (ref "U$111") (pin "V_CC") (pinfunction "VCC_V_CC") (pintype "bidirectional"))
      (node (ref "U$112") (pin "V_CC") (pinfunction "VCC_V_CC") (pintype "bidirectional"))
      (node (ref "U$113") (pin "V_CC") (pinfunction "VCC_V_CC") (pintype "bidirectional"))
      (node (ref "U$114") (pin "V_CC") (pinfunction "VCC_V_CC") (pintype "bidirectional"))
      (node (ref "U$115") (pin "V_CC") (pinfunction "VCC_V_CC") (pintype "bidirectional"))
      (node (ref "U$116") (pin "V_CC") (pinfunction "VCC_V_CC") (pintype "bidirectional"))
      (node (ref "U$117") (pin "V_CC") (pinfunction "VCC_V_CC") (pintype "bidirectional"))
      (node (ref "U$118") (pin "V_CC") (pinfunction "VCC_V_CC") (pintype "bidirectional"))
      (node (ref "U$119") (pin "V_CC") (pinfunction "VCC_V_CC") (pintype "bidirectional"))
      (node (ref "U$12") (pin "V_CC") (pinfunction "VCC_V_CC") (pintype "bidirectional"))
      (node (ref "U$120") (pin "V_CC") (pinfunction "VCC_V_CC") (pintype "bidirectional"))
      (node (ref "U$121") (pin "V_CC") (pinfunction "VCC_V_CC") (pintype "bidirectional"))
      (node (ref "U$122") (pin "V_CC") (pinfunction "VCC_V_CC") (pintype "bidirectional"))
      (node (ref "U$123") (pin "V_CC") (pinfunction "VCC_V_CC") (pintype "bidirectional"))
      (node (ref "U$124") (pin "V_CC") (pinfunction "VCC_V_CC") (pintype "bidirectional"))
      (node (ref "U$125") (pin "V_CC") (pinfunction "VCC_V_CC") (pintype "bidirectional"))
      (node (ref "U$126") (pin "V_CC") (pinfunction "VCC_V_CC") (pintype "bidirectional"))
      (node (ref "U$127") (pin "V_CC") (pinfunction "VCC_V_CC") (pintype "bidirectional"))
      (node (ref "U$128") (pin "V_CC") (pinfunction "VCC_V_CC") (pintype "bidirectional"))
      (node (ref "U$129") (pin "V_CC") (pinfunction "VCC_V_CC") (pintype "bidirectional"))
      (node (ref "U$13") (pin "V_CC") (pinfunction "VCC_V_CC") (pintype "bidirectional"))
      (node (ref "U$130") (pin "V_CC") (pinfunction "VCC_V_CC") (pintype "bidirectional"))
      (node (ref "U$14") (pin "V_CC") (pinfunction "VCC_V_CC") (pintype "bidirectional"))
      (node (ref "U$15") (pin "V_CC") (pinfunction "VCC_V_CC") (pintype "bidirectional"))
      (node (ref "U$18") (pin "V_CC") (pinfunction "VCC_V_CC") (pintype "bidirectional"))
      (node (ref "U$19") (pin "V_CC") (pinfunction "VCC_V_CC") (pintype "bidirectional"))
      (node (ref "U$2") (pin "1") (pinfunction "OUT_1") (pintype "bidirectional"))
      (node (ref "U$20") (pin "V_CC") (pinfunction "VCC_V_CC") (pintype "bidirectional"))
      (node (ref "U$21") (pin "V_CC") (pinfunction "VCC_V_CC") (pintype "bidirectional"))
      (node (ref "U$22") (pin "V_CC") (pinfunction "VCC_V_CC") (pintype "bidirectional"))
      (node (ref "U$24") (pin "V_CC") (pinfunction "VCC_V_CC") (pintype "bidirectional"))
      (node (ref "U$25") (pin "V_CC") (pinfunction "VCC_V_CC") (pintype "bidirectional"))
      (node (ref "U$27") (pin "V_CC") (pinfunction "VCC_V_CC") (pintype "bidirectional"))
      (node (ref "U$28") (pin "V_CC") (pinfunction "VCC_V_CC") (pintype "bidirectional"))
      (node (ref "U$29") (pin "V_CC") (pinfunction "VCC_V_CC") (pintype "bidirectional"))
      (node (ref "U$30") (pin "V_CC") (pinfunction "VCC_V_CC") (pintype "bidirectional"))
      (node (ref "U$31") (pin "V_CC") (pinfunction "VCC_V_CC") (pintype "bidirectional"))
      (node (ref "U$32") (pin "V_CC") (pinfunction "VCC_V_CC") (pintype "bidirectional"))
      (node (ref "U$33") (pin "V_CC") (pinfunction "VCC_V_CC") (pintype "bidirectional"))
      (node (ref "U$34") (pin "V_CC") (pinfunction "VCC_V_CC") (pintype "bidirectional"))
      (node (ref "U$35") (pin "V_CC") (pinfunction "VCC_V_CC") (pintype "bidirectional"))
      (node (ref "U$36") (pin "V_CC") (pinfunction "VCC_V_CC") (pintype "bidirectional"))
      (node (ref "U$37") (pin "V_CC") (pinfunction "VCC_V_CC") (pintype "bidirectional"))
      (node (ref "U$38") (pin "V_CC") (pinfunction "VCC_V_CC") (pintype "bidirectional"))
      (node (ref "U$39") (pin "V_CC") (pinfunction "VCC_V_CC") (pintype "bidirectional"))
      (node (ref "U$40") (pin "V_CC") (pinfunction "VCC_V_CC") (pintype "bidirectional"))
      (node (ref "U$41") (pin "V_CC") (pinfunction "VCC_V_CC") (pintype "bidirectional"))
      (node (ref "U$42") (pin "V_CC") (pinfunction "VCC_V_CC") (pintype "bidirectional"))
      (node (ref "U$43") (pin "V_CC") (pinfunction "VCC_V_CC") (pintype "bidirectional"))
      (node (ref "U$44") (pin "V_CC") (pinfunction "VCC_V_CC") (pintype "bidirectional"))
      (node (ref "U$45") (pin "V_CC") (pinfunction "VCC_V_CC") (pintype "bidirectional"))
      (node (ref "U$46") (pin "V_CC") (pinfunction "VCC_V_CC") (pintype "bidirectional"))
      (node (ref "U$47") (pin "V_CC") (pinfunction "VCC_V_CC") (pintype "bidirectional"))
      (node (ref "U$48") (pin "V_CC") (pinfunction "VCC_V_CC") (pintype "bidirectional"))
      (node (ref "U$49") (pin "V_CC") (pinfunction "VCC_V_CC") (pintype "bidirectional"))
      (node (ref "U$50") (pin "V_CC") (pinfunction "VCC_V_CC") (pintype "bidirectional"))
      (node (ref "U$51") (pin "V_CC") (pinfunction "VCC_V_CC") (pintype "bidirectional"))
      (node (ref "U$52") (pin "V_CC") (pinfunction "VCC_V_CC") (pintype "bidirectional"))
      (node (ref "U$53") (pin "V_CC") (pinfunction "VCC_V_CC") (pintype "bidirectional"))
      (node (ref "U$54") (pin "V_CC") (pinfunction "VCC_V_CC") (pintype "bidirectional"))
      (node (ref "U$55") (pin "V_CC") (pinfunction "VCC_V_CC") (pintype "bidirectional"))
      (node (ref "U$56") (pin "V_CC") (pinfunction "VCC_V_CC") (pintype "bidirectional"))
      (node (ref "U$57") (pin "V_CC") (pinfunction "VCC_V_CC") (pintype "bidirectional"))
      (node (ref "U$58") (pin "V_CC") (pinfunction "VCC_V_CC") (pintype "bidirectional"))
      (node (ref "U$59") (pin "V_CC") (pinfunction "VCC_V_CC") (pintype "bidirectional"))
      (node (ref "U$60") (pin "V_CC") (pinfunction "VCC_V_CC") (pintype "bidirectional"))
      (node (ref "U$61") (pin "V_CC") (pinfunction "VCC_V_CC") (pintype "bidirectional"))
      (node (ref "U$62") (pin "V_CC") (pinfunction "VCC_V_CC") (pintype "bidirectional"))
      (node (ref "U$63") (pin "V_CC") (pinfunction "VCC_V_CC") (pintype "bidirectional"))
      (node (ref "U$64") (pin "V_CC") (pinfunction "VCC_V_CC") (pintype "bidirectional"))
      (node (ref "U$65") (pin "V_CC") (pinfunction "VCC_V_CC") (pintype "bidirectional"))
      (node (ref "U$66") (pin "V_CC") (pinfunction "VCC_V_CC") (pintype "bidirectional"))
      (node (ref "U$67") (pin "V_CC") (pinfunction "VCC_V_CC") (pintype "bidirectional"))
      (node (ref "U$68") (pin "V_CC") (pinfunction "VCC_V_CC") (pintype "bidirectional"))
      (node (ref "U$69") (pin "V_CC") (pinfunction "VCC_V_CC") (pintype "bidirectional"))
      (node (ref "U$70") (pin "V_CC") (pinfunction "VCC_V_CC") (pintype "bidirectional"))
      (node (ref "U$71") (pin "V_CC") (pinfunction "VCC_V_CC") (pintype "bidirectional"))
      (node (ref "U$72") (pin "V_CC") (pinfunction "VCC_V_CC") (pintype "bidirectional"))
      (node (ref "U$73") (pin "V_CC") (pinfunction "VCC_V_CC") (pintype "bidirectional"))
      (node (ref "U$74") (pin "V_CC") (pinfunction "VCC_V_CC") (pintype "bidirectional"))
      (node (ref "U$75") (pin "V_CC") (pinfunction "VCC_V_CC") (pintype "bidirectional"))
      (node (ref "U$76") (pin "V_CC") (pinfunction "VCC_V_CC") (pintype "bidirectional"))
      (node (ref "U$77") (pin "V_CC") (pinfunction "VCC_V_CC") (pintype "bidirectional"))
      (node (ref "U$78") (pin "V_CC") (pinfunction "VCC_V_CC") (pintype "bidirectional"))
      (node (ref "U$79") (pin "V_CC") (pinfunction "VCC_V_CC") (pintype "bidirectional"))
      (node (ref "U$80") (pin "V_CC") (pinfunction "VCC_V_CC") (pintype "bidirectional"))
      (node (ref "U$81") (pin "V_CC") (pinfunction "VCC_V_CC") (pintype "bidirectional"))
      (node (ref "U$82") (pin "V_CC") (pinfunction "VCC_V_CC") (pintype "bidirectional"))
      (node (ref "U$83") (pin "V_CC") (pinfunction "VCC_V_CC") (pintype "bidirectional"))
      (node (ref "U$84") (pin "V_CC") (pinfunction "VCC_V_CC") (pintype "bidirectional"))
      (node (ref "U$85") (pin "V_CC") (pinfunction "VCC_V_CC") (pintype "bidirectional"))
      (node (ref "U$86") (pin "V_CC") (pinfunction "VCC_V_CC") (pintype "bidirectional"))
      (node (ref "U$87") (pin "V_CC") (pinfunction "VCC_V_CC") (pintype "bidirectional"))
      (node (ref "U$88") (pin "V_CC") (pinfunction "VCC_V_CC") (pintype "bidirectional"))
      (node (ref "U$89") (pin "V_CC") (pinfunction "VCC_V_CC") (pintype "bidirectional"))
      (node (ref "U$9") (pin "V_CC") (pinfunction "VCC_V_CC") (pintype "bidirectional"))
      (node (ref "U$90") (pin "V_CC") (pinfunction "VCC_V_CC") (pintype "bidirectional"))
      (node (ref "U$91") (pin "V_CC") (pinfunction "VCC_V_CC") (pintype "bidirectional"))
      (node (ref "U$92") (pin "V_CC") (pinfunction "VCC_V_CC") (pintype "bidirectional"))
      (node (ref "U$93") (pin "V_CC") (pinfunction "VCC_V_CC") (pintype "bidirectional"))
      (node (ref "U$94") (pin "V_CC") (pinfunction "VCC_V_CC") (pintype "bidirectional"))
      (node (ref "U$95") (pin "V_CC") (pinfunction "VCC_V_CC") (pintype "bidirectional"))
      (node (ref "U$96") (pin "V_CC") (pinfunction "VCC_V_CC") (pintype "bidirectional"))
      (node (ref "U$97") (pin "V_CC") (pinfunction "VCC_V_CC") (pintype "bidirectional"))
      (node (ref "U$98") (pin "V_CC") (pinfunction "VCC_V_CC") (pintype "bidirectional"))
      (node (ref "U$99") (pin "V_CC") (pinfunction "VCC_V_CC") (pintype "bidirectional"))
    )
    (net (code "3") (name "0") (class "Default")
      (node (ref "IC1") (pin "23") (pinfunction "IO0_23") (pintype "bidirectional"))
      (node (ref "Q1") (pin "6") (pinfunction "C_6") (pintype "passive"))
      (node (ref "R11") (pin "1") (pinfunction "1_1") (pintype "passive"))
    )
    (net (code "4") (name "3.3V") (class "Default")
      (node (ref "C11") (pin "1") (pinfunction "1_1") (pintype "passive"))
      (node (ref "C13") (pin "1") (pinfunction "1_1") (pintype "passive"))
      (node (ref "C15") (pin "1") (pinfunction "1_1") (pintype "passive"))
      (node (ref "C2") (pin "1") (pinfunction "1_1") (pintype "passive"))
      (node (ref "C6") (pin "1") (pinfunction "1_1") (pintype "passive"))
      (node (ref "C67") (pin "1") (pinfunction "1_1") (pintype "passive"))
      (node (ref "C7") (pin "1") (pinfunction "1_1") (pintype "passive"))
      (node (ref "C81") (pin "1") (pinfunction "1_1") (pintype "passive"))
      (node (ref "C82") (pin "1") (pinfunction "1_1") (pintype "passive"))
      (node (ref "IC1") (pin "1") (pinfunction "VDDA_1") (pintype "bidirectional"))
      (node (ref "IC1") (pin "19") (pinfunction "VDD3P3_RTC_19") (pintype "bidirectional"))
      (node (ref "IC1") (pin "3") (pinfunction "VDDA3P3_1_3") (pintype "bidirectional"))
      (node (ref "IC1") (pin "37") (pinfunction "VDD3P3_CPU_37") (pintype "bidirectional"))
      (node (ref "IC1") (pin "4") (pinfunction "VDDA_3P3_4") (pintype "bidirectional"))
      (node (ref "IC1") (pin "43") (pinfunction "VDDA_2_43") (pintype "bidirectional"))
      (node (ref "IC1") (pin "46") (pinfunction "VDDA_3_46") (pintype "bidirectional"))
      (node (ref "R1") (pin "2") (pinfunction "2_2") (pintype "passive"))
      (node (ref "R11") (pin "2") (pinfunction "2_2") (pintype "passive"))
      (node (ref "R19") (pin "2") (pinfunction "2_2") (pintype "passive"))
      (node (ref "R4") (pin "2") (pinfunction "2_2") (pintype "passive"))
      (node (ref "R7") (pin "2") (pinfunction "2_2") (pintype "passive"))
      (node (ref "R8") (pin "2") (pinfunction "2_2") (pintype "passive"))
      (node (ref "U$131") (pin "19") (pinfunction "OVDD_19") (pintype "bidirectional"))
      (node (ref "U2") (pin "5") (pinfunction "VDDIO_5") (pintype "bidirectional"))
      (node (ref "U2") (pin "8") (pinfunction "VDD_8") (pintype "bidirectional"))
      (node (ref "U8") (pin "5") (pinfunction "OUT_5") (pintype "passive"))
    )
    (net (code "5") (name "3.3V_F") (class "Default")
      (node (ref "C62") (pin "1") (pinfunction "1_1") (pintype "passive"))
      (node (ref "U1") (pin "13") (pinfunction "3V3OUT_13") (pintype "bidirectional"))
      (node (ref "U1") (pin "14") (pinfunction "~{RESET}_14") (pintype "bidirectional"))
      (node (ref "U1") (pin "3") (pinfunction "VCCIO_3") (pintype "bidirectional"))
    )
    (net (code "6") (name "32K_XN") (class "Default")
      (node (ref "C58") (pin "2") (pinfunction "2_2") (pintype "passive"))
      (node (ref "IC1") (pin "13") (pinfunction "IO33_13") (pintype "bidirectional"))
      (node (ref "Y1") (pin "P$2") (pinfunction "2_P$2") (pintype "passive"))
    )
    (net (code "7") (name "32K_XP") (class "Default")
      (node (ref "C57") (pin "2") (pinfunction "2_2") (pintype "passive"))
      (node (ref "IC1") (pin "12") (pinfunction "IO32_12") (pintype "bidirectional"))
      (node (ref "Y1") (pin "P$1") (pinfunction "1_P$1") (pintype "passive"))
    )
    (net (code "8") (name "BAT_MON") (class "Default")
      (node (ref "IC1") (pin "10") (pinfunction "IO34_10") (pintype "bidirectional"))
      (node (ref "R25") (pin "1") (pinfunction "1_1") (pintype "passive"))
      (node (ref "R26") (pin "2") (pinfunction "2_2") (pintype "passive"))
    )
    (net (code "9") (name "BUTTON") (class "Default")
      (node (ref "IC1") (pin "11") (pinfunction "IO35_11") (pintype "bidirectional"))
      (node (ref "R19") (pin "1") (pinfunction "1_1") (pintype "passive"))
      (node (ref "SW2") (pin "B") (pinfunction "S_B") (pintype "passive"))
      (node (ref "SW2") (pin "B'") (pinfunction "S1_B'") (pintype "passive"))
    )
    (net (code "10") (name "CHIP_PU") (class "Default")
      (node (ref "IC1") (pin "9") (pinfunction "EN_9") (pintype "bidirectional"))
      (node (ref "Q1") (pin "3") (pinfunction "C_3") (pintype "passive"))
      (node (ref "R8") (pin "1") (pinfunction "1_1") (pintype "passive"))
    )
    (net (code "11") (name "CS") (class "Default")
      (node (ref "R1") (pin "1") (pinfunction "1_1") (pintype "passive"))
      (node (ref "U2") (pin "12") (pinfunction "CS_12") (pintype "bidirectional"))
    )
    (net (code "12") (name "CSB") (class "Default")
      (node (ref "IC1") (pin "24") (pinfunction "IO4_24") (pintype "bidirectional"))
      (node (ref "U$131") (pin "15") (pinfunction "CSB_15") (pintype "bidirectional"))
    )
    (net (code "13") (name "D+") (class "Default")
      (node (ref "JP7") (pin "3") (pinfunction "D+_3") (pintype "bidirectional"))
      (node (ref "R15") (pin "1") (pinfunction "1_1") (pintype "passive"))
    )
    (net (code "14") (name "D-") (class "Default")
      (node (ref "JP7") (pin "2") (pinfunction "D-_2") (pintype "bidirectional"))
      (node (ref "R14") (pin "1") (pinfunction "1_1") (pintype "passive"))
    )
    (net (code "15") (name "DTR") (class "Default")
      (node (ref "Q1") (pin "1") (pinfunction "E_1") (pintype "passive"))
      (node (ref "R9") (pin "1") (pinfunction "1_1") (pintype "passive"))
      (node (ref "U1") (pin "1") (pinfunction "~{DTR}_1") (pintype "bidirectional"))
    )
    (net (code "16") (name "ECGN") (class "Default")
      (node (ref "C74") (pin "1") (pinfunction "1_1") (pintype "passive"))
      (node (ref "C76") (pin "2") (pinfunction "2_2") (pintype "passive"))
      (node (ref "R6") (pin "2") (pinfunction "2_2") (pintype "passive"))
      (node (ref "U$131") (pin "7") (pinfunction "EGGN_7") (pintype "bidirectional"))
    )
    (net (code "17") (name "ECGP") (class "Default")
      (node (ref "C75") (pin "1") (pinfunction "1_1") (pintype "passive"))
      (node (ref "C76") (pin "1") (pinfunction "1_1") (pintype "passive"))
      (node (ref "R3") (pin "2") (pinfunction "2_2") (pintype "passive"))
      (node (ref "U$131") (pin "6") (pinfunction "EGGP_6") (pintype "bidirectional"))
    )
    (net (code "18") (name "EN") (class "Default")
      (node (ref "S2") (pin "2") (pinfunction "P_2") (pintype "passive"))
      (node (ref "U8") (pin "3") (pinfunction "EN_3") (pintype "input"))
      (node (ref "U9") (pin "3") (pinfunction "EN_3") (pintype "input"))
    )
    (net (code "19") (name "FCLK") (class "Default")
      (node (ref "TP3") (pin "TP") (pinfunction "TP_TP") (pintype "input"))
      (node (ref "U$131") (pin "14") (pinfunction "FCLK_14") (pintype "bidirectional"))
      (node (ref "U$134") (pin "3") (pinfunction "CLK_3") (pintype "bidirectional"))
    )
    (net (code "20") (name "GND") (class "Default")
      (node (ref "C1") (pin "2") (pinfunction "2_2") (pintype "passive"))
      (node (ref "C10") (pin "2") (pinfunction "2_2") (pintype "passive"))
      (node (ref "C100") (pin "2") (pinfunction "2_2") (pintype "passive"))
      (node (ref "C101") (pin "2") (pinfunction "2_2") (pintype "passive"))
      (node (ref "C102") (pin "2") (pinfunction "2_2") (pintype "passive"))
      (node (ref "C103") (pin "2") (pinfunction "2_2") (pintype "passive"))
      (node (ref "C104") (pin "2") (pinfunction "2_2") (pintype "passive"))
      (node (ref "C105") (pin "2") (pinfunction "2_2") (pintype "passive"))
      (node (ref "C106") (pin "2") (pinfunction "2_2") (pintype "passive"))
      (node (ref "C107") (pin "2") (pinfunction "2_2") (pintype "passive"))
      (node (ref "C108") (pin "2") (pinfunction "2_2") (pintype "passive"))
      (node (ref "C109") (pin "2") (pinfunction "2_2") (pintype "passive"))
      (node (ref "C11") (pin "2") (pinfunction "2_2") (pintype "passive"))
      (node (ref "C110") (pin "2") (pinfunction "2_2") (pintype "passive"))
      (node (ref "C111") (pin "2") (pinfunction "2_2") (pintype "passive"))
      (node (ref "C112") (pin "2") (pinfunction "2_2") (pintype "passive"))
      (node (ref "C113") (pin "2") (pinfunction "2_2") (pintype "passive"))
      (node (ref "C114") (pin "2") (pinfunction "2_2") (pintype "passive"))
      (node (ref "C115") (pin "2") (pinfunction "2_2") (pintype "passive"))
      (node (ref "C116") (pin "2") (pinfunction "2_2") (pintype "passive"))
      (node (ref "C117") (pin "2") (pinfunction "2_2") (pintype "passive"))
      (node (ref "C118") (pin "2") (pinfunction "2_2") (pintype "passive"))
      (node (ref "C119") (pin "1") (pinfunction "1_1") (pintype "passive"))
      (node (ref "C12") (pin "2") (pinfunction "2_2") (pintype "passive"))
      (node (ref "C120") (pin "1") (pinfunction "1_1") (pintype "passive"))
      (node (ref "C121") (pin "2") (pinfunction "2_2") (pintype "passive"))
      (node (ref "C122") (pin "2") (pinfunction "2_2") (pintype "passive"))
      (node (ref "C13") (pin "2") (pinfunction "2_2") (pintype "passive"))
      (node (ref "C14") (pin "2") (pinfunction "2_2") (pintype "passive"))
      (node (ref "C15") (pin "2") (pinfunction "2_2") (pintype "passive"))
      (node (ref "C16") (pin "2") (pinfunction "2_2") (pintype "passive"))
      (node (ref "C17") (pin "2") (pinfunction "2_2") (pintype "passive"))
      (node (ref "C18") (pin "2") (pinfunction "2_2") (pintype "passive"))
      (node (ref "C19") (pin "2") (pinfunction "2_2") (pintype "passive"))
      (node (ref "C2") (pin "2") (pinfunction "2_2") (pintype "passive"))
      (node (ref "C21") (pin "2") (pinfunction "2_2") (pintype "passive"))
      (node (ref "C22") (pin "2") (pinfunction "2_2") (pintype "passive"))
      (node (ref "C23") (pin "2") (pinfunction "2_2") (pintype "passive"))
      (node (ref "C24") (pin "2") (pinfunction "2_2") (pintype "passive"))
      (node (ref "C25") (pin "2") (pinfunction "2_2") (pintype "passive"))
      (node (ref "C26") (pin "2") (pinfunction "2_2") (pintype "passive"))
      (node (ref "C27") (pin "2") (pinfunction "2_2") (pintype "passive"))
      (node (ref "C28") (pin "2") (pinfunction "2_2") (pintype "passive"))
      (node (ref "C29") (pin "2") (pinfunction "2_2") (pintype "passive"))
      (node (ref "C3") (pin "2") (pinfunction "2_2") (pintype "passive"))
      (node (ref "C30") (pin "2") (pinfunction "2_2") (pintype "passive"))
      (node (ref "C31") (pin "2") (pinfunction "2_2") (pintype "passive"))
      (node (ref "C32") (pin "2") (pinfunction "2_2") (pintype "passive"))
      (node (ref "C33") (pin "2") (pinfunction "2_2") (pintype "passive"))
      (node (ref "C34") (pin "2") (pinfunction "2_2") (pintype "passive"))
      (node (ref "C35") (pin "2") (pinfunction "2_2") (pintype "passive"))
      (node (ref "C36") (pin "2") (pinfunction "2_2") (pintype "passive"))
      (node (ref "C37") (pin "2") (pinfunction "2_2") (pintype "passive"))
      (node (ref "C38") (pin "2") (pinfunction "2_2") (pintype "passive"))
      (node (ref "C39") (pin "2") (pinfunction "2_2") (pintype "passive"))
      (node (ref "C4") (pin "2") (pinfunction "2_2") (pintype "passive"))
      (node (ref "C40") (pin "2") (pinfunction "2_2") (pintype "passive"))
      (node (ref "C41") (pin "2") (pinfunction "2_2") (pintype "passive"))
      (node (ref "C42") (pin "2") (pinfunction "2_2") (pintype "passive"))
      (node (ref "C43") (pin "2") (pinfunction "2_2") (pintype "passive"))
      (node (ref "C44") (pin "2") (pinfunction "2_2") (pintype "passive"))
      (node (ref "C45") (pin "2") (pinfunction "2_2") (pintype "passive"))
      (node (ref "C46") (pin "2") (pinfunction "2_2") (pintype "passive"))
      (node (ref "C47") (pin "2") (pinfunction "2_2") (pintype "passive"))
      (node (ref "C48") (pin "2") (pinfunction "2_2") (pintype "passive"))
      (node (ref "C5") (pin "2") (pinfunction "2_2") (pintype "passive"))
      (node (ref "C50") (pin "2") (pinfunction "2_2") (pintype "passive"))
      (node (ref "C51") (pin "2") (pinfunction "2_2") (pintype "passive"))
      (node (ref "C52") (pin "2") (pinfunction "2_2") (pintype "passive"))
      (node (ref "C53") (pin "2") (pinfunction "2_2") (pintype "passive"))
      (node (ref "C54") (pin "2") (pinfunction "2_2") (pintype "passive"))
      (node (ref "C55") (pin "2") (pinfunction "2_2") (pintype "passive"))
      (node (ref "C56") (pin "2") (pinfunction "2_2") (pintype "passive"))
      (node (ref "C57") (pin "1") (pinfunction "1_1") (pintype "passive"))
      (node (ref "C58") (pin "1") (pinfunction "1_1") (pintype "passive"))
      (node (ref "C59") (pin "2") (pinfunction "2_2") (pintype "passive"))
      (node (ref "C6") (pin "2") (pinfunction "2_2") (pintype "passive"))
      (node (ref "C60") (pin "2") (pinfunction "2_2") (pintype "passive"))
      (node (ref "C61") (pin "2") (pinfunction "2_2") (pintype "passive"))
      (node (ref "C62") (pin "2") (pinfunction "2_2") (pintype "passive"))
      (node (ref "C63") (pin "2") (pinfunction "2_2") (pintype "passive"))
      (node (ref "C64") (pin "2") (pinfunction "2_2") (pintype "passive"))
      (node (ref "C65") (pin "2") (pinfunction "2_2") (pintype "passive"))
      (node (ref "C66") (pin "2") (pinfunction "2_2") (pintype "passive"))
      (node (ref "C67") (pin "2") (pinfunction "2_2") (pintype "passive"))
      (node (ref "C68") (pin "2") (pinfunction "2_2") (pintype "passive"))
      (node (ref "C69") (pin "2") (pinfunction "2_2") (pintype "passive"))
      (node (ref "C7") (pin "2") (pinfunction "2_2") (pintype "passive"))
      (node (ref "C70") (pin "2") (pinfunction "2_2") (pintype "passive"))
      (node (ref "C71") (pin "2") (pinfunction "2_2") (pintype "passive"))
      (node (ref "C72") (pin "1") (pinfunction "1_1") (pintype "passive"))
      (node (ref "C73") (pin "2") (pinfunction "2_2") (pintype "passive"))
      (node (ref "C74") (pin "2") (pinfunction "2_2") (pintype "passive"))
      (node (ref "C75") (pin "2") (pinfunction "2_2") (pintype "passive"))
      (node (ref "C77") (pin "2") (pinfunction "2_2") (pintype "passive"))
      (node (ref "C78") (pin "2") (pinfunction "2_2") (pintype "passive"))
      (node (ref "C79") (pin "2") (pinfunction "2_2") (pintype "passive"))
      (node (ref "C8") (pin "2") (pinfunction "2_2") (pintype "passive"))
      (node (ref "C80") (pin "2") (pinfunction "2_2") (pintype "passive"))
      (node (ref "C81") (pin "2") (pinfunction "2_2") (pintype "passive"))
      (node (ref "C82") (pin "2") (pinfunction "2_2") (pintype "passive"))
      (node (ref "C83") (pin "2") (pinfunction "2_2") (pintype "passive"))
      (node (ref "C84") (pin "2") (pinfunction "2_2") (pintype "passive"))
      (node (ref "C85") (pin "2") (pinfunction "2_2") (pintype "passive"))
      (node (ref "C86") (pin "2") (pinfunction "2_2") (pintype "passive"))
      (node (ref "C87") (pin "2") (pinfunction "2_2") (pintype "passive"))
      (node (ref "C88") (pin "2") (pinfunction "2_2") (pintype "passive"))
      (node (ref "C89") (pin "2") (pinfunction "2_2") (pintype "passive"))
      (node (ref "C9") (pin "2") (pinfunction "2_2") (pintype "passive"))
      (node (ref "C90") (pin "2") (pinfunction "2_2") (pintype "passive"))
      (node (ref "C91") (pin "2") (pinfunction "2_2") (pintype "passive"))
      (node (ref "C92") (pin "2") (pinfunction "2_2") (pintype "passive"))
      (node (ref "C93") (pin "2") (pinfunction "2_2") (pintype "passive"))
      (node (ref "C94") (pin "2") (pinfunction "2_2") (pintype "passive"))
      (node (ref "C95") (pin "2") (pinfunction "2_2") (pintype "passive"))
      (node (ref "C96") (pin "2") (pinfunction "2_2") (pintype "passive"))
      (node (ref "C97") (pin "2") (pinfunction "2_2") (pintype "passive"))
      (node (ref "C98") (pin "2") (pinfunction "2_2") (pintype "passive"))
      (node (ref "C99") (pin "2") (pinfunction "2_2") (pintype "passive"))
      (node (ref "E1") (pin "GND") (pinfunction "GND_GND") (pintype "bidirectional"))
      (node (ref "E1") (pin "GND2") (pinfunction "GND_GND2") (pintype "bidirectional"))
      (node (ref "IC1") (pin "EXP") (pinfunction "GNDPAD_EXP") (pintype "power_in"))
      (node (ref "JP7") (pin "5") (pinfunction "GND_5") (pintype "bidirectional"))
      (node (ref "JP7") (pin "P$5") (pinfunction "GND1_P$5") (pintype "bidirectional"))
      (node (ref "JP7") (pin "P$6") (pinfunction "GND2_P$6") (pintype "bidirectional"))
      (node (ref "L1") (pin "2") (pinfunction "2_2") (pintype "passive"))
      (node (ref "R17") (pin "1") (pinfunction "1_1") (pintype "passive"))
      (node (ref "R23") (pin "1") (pinfunction "1_1") (pintype "passive"))
      (node (ref "R26") (pin "1") (pinfunction "1_1") (pintype "passive"))
      (node (ref "S2") (pin "1") (pinfunction "O_1") (pintype "passive"))
      (node (ref "SW2") (pin "A") (pinfunction "P_A") (pintype "passive"))
      (node (ref "TP5") (pin "TP-2") (pinfunction "TP_TP-2") (pintype "input"))
      (node (ref "U$10") (pin "GND") (pinfunction "GND_GND") (pintype "bidirectional"))
      (node (ref "U$100") (pin "GND") (pinfunction "GND_GND") (pintype "bidirectional"))
      (node (ref "U$101") (pin "GND") (pinfunction "GND_GND") (pintype "bidirectional"))
      (node (ref "U$102") (pin "GND") (pinfunction "GND_GND") (pintype "bidirectional"))
      (node (ref "U$103") (pin "GND") (pinfunction "GND_GND") (pintype "bidirectional"))
      (node (ref "U$104") (pin "GND") (pinfunction "GND_GND") (pintype "bidirectional"))
      (node (ref "U$106") (pin "GND") (pinfunction "GND_GND") (pintype "bidirectional"))
      (node (ref "U$107") (pin "GND") (pinfunction "GND_GND") (pintype "bidirectional"))
      (node (ref "U$108") (pin "GND") (pinfunction "GND_GND") (pintype "bidirectional"))
      (node (ref "U$109") (pin "GND") (pinfunction "GND_GND") (pintype "bidirectional"))
      (node (ref "U$11") (pin "GND") (pinfunction "GND_GND") (pintype "bidirectional"))
      (node (ref "U$110") (pin "GND") (pinfunction "GND_GND") (pintype "bidirectional"))
      (node (ref "U$111") (pin "GND") (pinfunction "GND_GND") (pintype "bidirectional"))
      (node (ref "U$112") (pin "GND") (pinfunction "GND_GND") (pintype "bidirectional"))
      (node (ref "U$113") (pin "GND") (pinfunction "GND_GND") (pintype "bidirectional"))
      (node (ref "U$114") (pin "GND") (pinfunction "GND_GND") (pintype "bidirectional"))
      (node (ref "U$115") (pin "GND") (pinfunction "GND_GND") (pintype "bidirectional"))
      (node (ref "U$116") (pin "GND") (pinfunction "GND_GND") (pintype "bidirectional"))
      (node (ref "U$117") (pin "GND") (pinfunction "GND_GND") (pintype "bidirectional"))
      (node (ref "U$118") (pin "GND") (pinfunction "GND_GND") (pintype "bidirectional"))
      (node (ref "U$119") (pin "GND") (pinfunction "GND_GND") (pintype "bidirectional"))
      (node (ref "U$12") (pin "GND") (pinfunction "GND_GND") (pintype "bidirectional"))
      (node (ref "U$120") (pin "GND") (pinfunction "GND_GND") (pintype "bidirectional"))
      (node (ref "U$121") (pin "GND") (pinfunction "GND_GND") (pintype "bidirectional"))
      (node (ref "U$122") (pin "GND") (pinfunction "GND_GND") (pintype "bidirectional"))
      (node (ref "U$123") (pin "GND") (pinfunction "GND_GND") (pintype "bidirectional"))
      (node (ref "U$124") (pin "GND") (pinfunction "GND_GND") (pintype "bidirectional"))
      (node (ref "U$125") (pin "GND") (pinfunction "GND_GND") (pintype "bidirectional"))
      (node (ref "U$126") (pin "GND") (pinfunction "GND_GND") (pintype "bidirectional"))
      (node (ref "U$127") (pin "GND") (pinfunction "GND_GND") (pintype "bidirectional"))
      (node (ref "U$128") (pin "GND") (pinfunction "GND_GND") (pintype "bidirectional"))
      (node (ref "U$129") (pin "GND") (pinfunction "GND_GND") (pintype "bidirectional"))
      (node (ref "U$13") (pin "GND") (pinfunction "GND_GND") (pintype "bidirectional"))
      (node (ref "U$130") (pin "GND") (pinfunction "GND_GND") (pintype "bidirectional"))
      (node (ref "U$131") (pin "1") (pinfunction "IC_1") (pintype "bidirectional"))
      (node (ref "U$131") (pin "12") (pinfunction "DGND_12") (pintype "bidirectional"))
      (node (ref "U$131") (pin "2") (pinfunction "IC_2") (pintype "bidirectional"))
      (node (ref "U$131") (pin "24") (pinfunction "IC_24") (pintype "bidirectional"))
      (node (ref "U$131") (pin "26") (pinfunction "IC_26") (pintype "bidirectional"))
      (node (ref "U$131") (pin "28") (pinfunction "AGND_28") (pintype "bidirectional"))
      (node (ref "U$131") (pin "3") (pinfunction "AGND_3") (pintype "bidirectional"))
      (node (ref "U$131") (pin "4") (pinfunction "IC_4") (pintype "bidirectional"))
      (node (ref "U$131") (pin "5") (pinfunction "IC_5") (pintype "bidirectional"))
      (node (ref "U$131") (pin "8") (pinfunction "AGND_8") (pintype "bidirectional"))
      (node (ref "U$131") (pin "THERMAL") (pinfunction "THERM_THERMAL") (pintype "bidirectional"))
      (node (ref "U$134") (pin "2") (pinfunction "GND_2") (pintype "bidirectional"))
      (node (ref "U$14") (pin "GND") (pinfunction "GND_GND") (pintype "bidirectional"))
      (node (ref "U$15") (pin "GND") (pinfunction "GND_GND") (pintype "bidirectional"))
      (node (ref "U$18") (pin "GND") (pinfunction "GND_GND") (pintype "bidirectional"))
      (node (ref "U$19") (pin "GND") (pinfunction "GND_GND") (pintype "bidirectional"))
      (node (ref "U$2") (pin "2") (pinfunction "GND_2") (pintype "bidirectional"))
      (node (ref "U$2") (pin "5") (pinfunction "GND_5") (pintype "bidirectional"))
      (node (ref "U$20") (pin "GND") (pinfunction "GND_GND") (pintype "bidirectional"))
      (node (ref "U$21") (pin "GND") (pinfunction "GND_GND") (pintype "bidirectional"))
      (node (ref "U$22") (pin "GND") (pinfunction "GND_GND") (pintype "bidirectional"))
      (node (ref "U$24") (pin "GND") (pinfunction "GND_GND") (pintype "bidirectional"))
      (node (ref "U$25") (pin "GND") (pinfunction "GND_GND") (pintype "bidirectional"))
      (node (ref "U$27") (pin "GND") (pinfunction "GND_GND") (pintype "bidirectional"))
      (node (ref "U$28") (pin "GND") (pinfunction "GND_GND") (pintype "bidirectional"))
      (node (ref "U$29") (pin "GND") (pinfunction "GND_GND") (pintype "bidirectional"))
      (node (ref "U$30") (pin "GND") (pinfunction "GND_GND") (pintype "bidirectional"))
      (node (ref "U$31") (pin "GND") (pinfunction "GND_GND") (pintype "bidirectional"))
      (node (ref "U$32") (pin "GND") (pinfunction "GND_GND") (pintype "bidirectional"))
      (node (ref "U$33") (pin "GND") (pinfunction "GND_GND") (pintype "bidirectional"))
      (node (ref "U$34") (pin "GND") (pinfunction "GND_GND") (pintype "bidirectional"))
      (node (ref "U$35") (pin "GND") (pinfunction "GND_GND") (pintype "bidirectional"))
      (node (ref "U$36") (pin "GND") (pinfunction "GND_GND") (pintype "bidirectional"))
      (node (ref "U$37") (pin "GND") (pinfunction "GND_GND") (pintype "bidirectional"))
      (node (ref "U$38") (pin "GND") (pinfunction "GND_GND") (pintype "bidirectional"))
      (node (ref "U$39") (pin "GND") (pinfunction "GND_GND") (pintype "bidirectional"))
      (node (ref "U$40") (pin "GND") (pinfunction "GND_GND") (pintype "bidirectional"))
      (node (ref "U$41") (pin "GND") (pinfunction "GND_GND") (pintype "bidirectional"))
      (node (ref "U$42") (pin "GND") (pinfunction "GND_GND") (pintype "bidirectional"))
      (node (ref "U$43") (pin "GND") (pinfunction "GND_GND") (pintype "bidirectional"))
      (node (ref "U$44") (pin "GND") (pinfunction "GND_GND") (pintype "bidirectional"))
      (node (ref "U$45") (pin "GND") (pinfunction "GND_GND") (pintype "bidirectional"))
      (node (ref "U$46") (pin "GND") (pinfunction "GND_GND") (pintype "bidirectional"))
      (node (ref "U$47") (pin "GND") (pinfunction "GND_GND") (pintype "bidirectional"))
      (node (ref "U$48") (pin "GND") (pinfunction "GND_GND") (pintype "bidirectional"))
      (node (ref "U$49") (pin "GND") (pinfunction "GND_GND") (pintype "bidirectional"))
      (node (ref "U$50") (pin "GND") (pinfunction "GND_GND") (pintype "bidirectional"))
      (node (ref "U$51") (pin "GND") (pinfunction "GND_GND") (pintype "bidirectional"))
      (node (ref "U$52") (pin "GND") (pinfunction "GND_GND") (pintype "bidirectional"))
      (node (ref "U$53") (pin "GND") (pinfunction "GND_GND") (pintype "bidirectional"))
      (node (ref "U$54") (pin "GND") (pinfunction "GND_GND") (pintype "bidirectional"))
      (node (ref "U$55") (pin "GND") (pinfunction "GND_GND") (pintype "bidirectional"))
      (node (ref "U$56") (pin "GND") (pinfunction "GND_GND") (pintype "bidirectional"))
      (node (ref "U$57") (pin "GND") (pinfunction "GND_GND") (pintype "bidirectional"))
      (node (ref "U$58") (pin "GND") (pinfunction "GND_GND") (pintype "bidirectional"))
      (node (ref "U$59") (pin "GND") (pinfunction "GND_GND") (pintype "bidirectional"))
      (node (ref "U$60") (pin "GND") (pinfunction "GND_GND") (pintype "bidirectional"))
      (node (ref "U$61") (pin "GND") (pinfunction "GND_GND") (pintype "bidirectional"))
      (node (ref "U$62") (pin "GND") (pinfunction "GND_GND") (pintype "bidirectional"))
      (node (ref "U$63") (pin "GND") (pinfunction "GND_GND") (pintype "bidirectional"))
      (node (ref "U$64") (pin "GND") (pinfunction "GND_GND") (pintype "bidirectional"))
      (node (ref "U$65") (pin "GND") (pinfunction "GND_GND") (pintype "bidirectional"))
      (node (ref "U$66") (pin "GND") (pinfunction "GND_GND") (pintype "bidirectional"))
      (node (ref "U$67") (pin "GND") (pinfunction "GND_GND") (pintype "bidirectional"))
      (node (ref "U$68") (pin "GND") (pinfunction "GND_GND") (pintype "bidirectional"))
      (node (ref "U$69") (pin "GND") (pinfunction "GND_GND") (pintype "bidirectional"))
      (node (ref "U$70") (pin "GND") (pinfunction "GND_GND") (pintype "bidirectional"))
      (node (ref "U$71") (pin "GND") (pinfunction "GND_GND") (pintype "bidirectional"))
      (node (ref "U$72") (pin "GND") (pinfunction "GND_GND") (pintype "bidirectional"))
      (node (ref "U$73") (pin "GND") (pinfunction "GND_GND") (pintype "bidirectional"))
      (node (ref "U$74") (pin "GND") (pinfunction "GND_GND") (pintype "bidirectional"))
      (node (ref "U$75") (pin "GND") (pinfunction "GND_GND") (pintype "bidirectional"))
      (node (ref "U$76") (pin "GND") (pinfunction "GND_GND") (pintype "bidirectional"))
      (node (ref "U$77") (pin "GND") (pinfunction "GND_GND") (pintype "bidirectional"))
      (node (ref "U$78") (pin "GND") (pinfunction "GND_GND") (pintype "bidirectional"))
      (node (ref "U$79") (pin "GND") (pinfunction "GND_GND") (pintype "bidirectional"))
      (node (ref "U$80") (pin "GND") (pinfunction "GND_GND") (pintype "bidirectional"))
      (node (ref "U$81") (pin "GND") (pinfunction "GND_GND") (pintype "bidirectional"))
      (node (ref "U$82") (pin "GND") (pinfunction "GND_GND") (pintype "bidirectional"))
      (node (ref "U$83") (pin "GND") (pinfunction "GND_GND") (pintype "bidirectional"))
      (node (ref "U$84") (pin "GND") (pinfunction "GND_GND") (pintype "bidirectional"))
      (node (ref "U$85") (pin "GND") (pinfunction "GND_GND") (pintype "bidirectional"))
      (node (ref "U$86") (pin "GND") (pinfunction "GND_GND") (pintype "bidirectional"))
      (node (ref "U$87") (pin "GND") (pinfunction "GND_GND") (pintype "bidirectional"))
      (node (ref "U$88") (pin "GND") (pinfunction "GND_GND") (pintype "bidirectional"))
      (node (ref "U$89") (pin "GND") (pinfunction "GND_GND") (pintype "bidirectional"))
      (node (ref "U$9") (pin "GND") (pinfunction "GND_GND") (pintype "bidirectional"))
      (node (ref "U$90") (pin "GND") (pinfunction "GND_GND") (pintype "bidirectional"))
      (node (ref "U$91") (pin "GND") (pinfunction "GND_GND") (pintype "bidirectional"))
      (node (ref "U$92") (pin "GND") (pinfunction "GND_GND") (pintype "bidirectional"))
      (node (ref "U$93") (pin "GND") (pinfunction "GND_GND") (pintype "bidirectional"))
      (node (ref "U$94") (pin "GND") (pinfunction "GND_GND") (pintype "bidirectional"))
      (node (ref "U$95") (pin "GND") (pinfunction "GND_GND") (pintype "bidirectional"))
      (node (ref "U$96") (pin "GND") (pinfunction "GND_GND") (pintype "bidirectional"))
      (node (ref "U$97") (pin "GND") (pinfunction "GND_GND") (pintype "bidirectional"))
      (node (ref "U$98") (pin "GND") (pinfunction "GND_GND") (pintype "bidirectional"))
      (node (ref "U$99") (pin "GND") (pinfunction "GND_GND") (pintype "bidirectional"))
      (node (ref "U1") (pin "16") (pinfunction "GND_16") (pintype "bidirectional"))
      (node (ref "U1") (pin "6") (pinfunction "GND_6") (pintype "bidirectional"))
      (node (ref "U2") (pin "1") (pinfunction "SDO/SA0_1") (pintype "bidirectional"))
      (node (ref "U2") (pin "2") (pinfunction "SDX_2") (pintype "bidirectional"))
      (node (ref "U2") (pin "3") (pinfunction "SCX_3") (pintype "bidirectional"))
      (node (ref "U2") (pin "6") (pinfunction "GND_6") (pintype "bidirectional"))
      (node (ref "U2") (pin "7") (pinfunction "GND_7") (pintype "bidirectional"))
      (node (ref "U3") (pin "2") (pinfunction "VSS_2") (pintype "power_in"))
      (node (ref "U8") (pin "2") (pinfunction "GND_2") (pintype "input"))
      (node (ref "U9") (pin "2") (pinfunction "GND_2") (pintype "input"))
    )
    (net (code "21") (name "INTB") (class "Default")
      (node (ref "IC1") (pin "16") (pinfunction "IO27_16") (pintype "bidirectional"))
      (node (ref "U$131") (pin "21") (pinfunction "INTB_21") (pintype "bidirectional"))
    )
    (net (code "22") (name "IO12") (class "Default")
      (node (ref "IC1") (pin "18") (pinfunction "IO12_18") (pintype "power_in"))
    )
    (net (code "23") (name "LED_CLK") (class "Default")
      (node (ref "IC1") (pin "14") (pinfunction "IO25_14") (pintype "bidirectional"))
      (node (ref "R5") (pin "2") (pinfunction "2_2") (pintype "passive"))
    )
    (net (code "24") (name "LED_DATA") (class "Default")
      (node (ref "IC1") (pin "15") (pinfunction "IO26_15") (pintype "bidirectional"))
      (node (ref "R2") (pin "2") (pinfunction "2_2") (pintype "passive"))
    )
    (net (code "25") (name "LED_PWR_ON") (class "Default")
      (node (ref "R20") (pin "1") (pinfunction "1_1") (pintype "passive"))
      (node (ref "U$2") (pin "3") (pinfunction "EN_3") (pintype "bidirectional"))
    )
    (net (code "26") (name "MISO") (class "Default")
      (node (ref "IC1") (pin "38") (pinfunction "IO19_38") (pintype "bidirectional"))
      (node (ref "U$131") (pin "18") (pinfunction "SDO_18") (pintype "bidirectional"))
    )
    (net (code "27") (name "MOSI") (class "Default")
      (node (ref "IC1") (pin "36") (pinfunction "IO23_36") (pintype "bidirectional"))
      (node (ref "U$131") (pin "17") (pinfunction "SDI_17") (pintype "bidirectional"))
    )
    (net (code "28") (name "Net-(CHG2-PadA)") (class "Default")
      (node (ref "CHG2") (pin "A") (pinfunction "A_A") (pintype "passive"))
      (node (ref "R16") (pin "2") (pinfunction "2_2") (pintype "passive"))
    )
    (net (code "29") (name "Net-(E1-SIGNAL)") (class "Default")
      (node (ref "C48") (pin "1") (pinfunction "1_1") (pintype "passive"))
      (node (ref "C49") (pin "2") (pinfunction "2_2") (pintype "passive"))
      (node (ref "E1") (pin "ANT") (pinfunction "SIGNAL_ANT") (pintype "bidirectional"))
    )
    (net (code "30") (name "Net-(H1-MOUNT)") (class "Default")
      (node (ref "H1") (pin "B4,1") (pinfunction "MOUNT_B4,1") (pintype "passive"))
      (node (ref "R3") (pin "1") (pinfunction "1_1") (pintype "passive"))
      (node (ref "TP1") (pin "TP") (pinfunction "TP_TP") (pintype "input"))
    )
    (net (code "31") (name "Net-(H2-MOUNT)") (class "Default")
      (node (ref "H2") (pin "B4,1") (pinfunction "MOUNT_B4,1") (pintype "passive"))
      (node (ref "R6") (pin "1") (pinfunction "1_1") (pintype "passive"))
      (node (ref "TP2") (pin "TP") (pinfunction "TP_TP") (pintype "input"))
    )
    (net (code "32") (name "Net-(IC1A-IO14)") (class "Default")
      (node (ref "IC1") (pin "17") (pinfunction "IO14_17") (pintype "bidirectional"))
      (node (ref "R20") (pin "2") (pinfunction "2_2") (pintype "passive"))
    )
    (net (code "33") (name "Net-(IC1A-LNA_IN)") (class "Default")
      (node (ref "C49") (pin "1") (pinfunction "1_1") (pintype "passive"))
      (node (ref "IC1") (pin "2") (pinfunction "LNA_IN_2") (pintype "bidirectional"))
      (node (ref "L1") (pin "1") (pinfunction "1_1") (pintype "passive"))
    )
    (net (code "34") (name "Net-(IC1A-VDD_SDIO_NC)") (class "Default")
      (node (ref "C8") (pin "1") (pinfunction "1_1") (pintype "passive"))
      (node (ref "IC1") (pin "26") (pinfunction "VDD_SDIO_NC_26") (pintype "bidirectional"))
    )
    (net (code "35") (name "Net-(Q1A-B)") (class "Default")
      (node (ref "Q1") (pin "5") (pinfunction "B_5") (pintype "passive"))
      (node (ref "R9") (pin "2") (pinfunction "2_2") (pintype "passive"))
    )
    (net (code "36") (name "Net-(Q1B-B)") (class "Default")
      (node (ref "Q1") (pin "2") (pinfunction "B_2") (pintype "passive"))
      (node (ref "R10") (pin "2") (pinfunction "2_2") (pintype "passive"))
    )
    (net (code "37") (name "Net-(U$9-CI)") (class "Default")
      (node (ref "R5") (pin "1") (pinfunction "1_1") (pintype "passive"))
      (node (ref "U$9") (pin "C_IN") (pinfunction "CI_C_IN") (pintype "bidirectional"))
    )
    (net (code "38") (name "Net-(U$9-DI)") (class "Default")
      (node (ref "R2") (pin "1") (pinfunction "1_1") (pintype "passive"))
      (node (ref "U$9") (pin "D_IN") (pinfunction "DI_D_IN") (pintype "bidirectional"))
    )
    (net (code "39") (name "Net-(U$10-CI)") (class "Default")
      (node (ref "U$10") (pin "C_IN") (pinfunction "CI_C_IN") (pintype "bidirectional"))
      (node (ref "U$9") (pin "CL_OUT") (pinfunction "CO_CL_OUT") (pintype "bidirectional"))
    )
    (net (code "40") (name "Net-(U$10-CO)") (class "Default")
      (node (ref "U$10") (pin "CL_OUT") (pinfunction "CO_CL_OUT") (pintype "bidirectional"))
      (node (ref "U$11") (pin "C_IN") (pinfunction "CI_C_IN") (pintype "bidirectional"))
    )
    (net (code "41") (name "Net-(U$10-DI)") (class "Default")
      (node (ref "U$10") (pin "D_IN") (pinfunction "DI_D_IN") (pintype "bidirectional"))
      (node (ref "U$9") (pin "D_OUT") (pinfunction "DO_D_OUT") (pintype "bidirectional"))
    )
    (net (code "42") (name "Net-(U$10-DO)") (class "Default")
      (node (ref "U$10") (pin "D_OUT") (pinfunction "DO_D_OUT") (pintype "bidirectional"))
      (node (ref "U$11") (pin "D_IN") (pinfunction "DI_D_IN") (pintype "bidirectional"))
    )
    (net (code "43") (name "Net-(U$11-CO)") (class "Default")
      (node (ref "U$11") (pin "CL_OUT") (pinfunction "CO_CL_OUT") (pintype "bidirectional"))
      (node (ref "U$12") (pin "C_IN") (pinfunction "CI_C_IN") (pintype "bidirectional"))
    )
    (net (code "44") (name "Net-(U$11-DO)") (class "Default")
      (node (ref "U$11") (pin "D_OUT") (pinfunction "DO_D_OUT") (pintype "bidirectional"))
      (node (ref "U$12") (pin "D_IN") (pinfunction "DI_D_IN") (pintype "bidirectional"))
    )
    (net (code "45") (name "Net-(U$12-CO)") (class "Default")
      (node (ref "U$12") (pin "CL_OUT") (pinfunction "CO_CL_OUT") (pintype "bidirectional"))
      (node (ref "U$13") (pin "C_IN") (pinfunction "CI_C_IN") (pintype "bidirectional"))
    )
    (net (code "46") (name "Net-(U$12-DO)") (class "Default")
      (node (ref "U$12") (pin "D_OUT") (pinfunction "DO_D_OUT") (pintype "bidirectional"))
      (node (ref "U$13") (pin "D_IN") (pinfunction "DI_D_IN") (pintype "bidirectional"))
    )
    (net (code "47") (name "Net-(U$13-CO)") (class "Default")
      (node (ref "U$13") (pin "CL_OUT") (pinfunction "CO_CL_OUT") (pintype "bidirectional"))
      (node (ref "U$14") (pin "C_IN") (pinfunction "CI_C_IN") (pintype "bidirectional"))
    )
    (net (code "48") (name "Net-(U$13-DO)") (class "Default")
      (node (ref "U$13") (pin "D_OUT") (pinfunction "DO_D_OUT") (pintype "bidirectional"))
      (node (ref "U$14") (pin "D_IN") (pinfunction "DI_D_IN") (pintype "bidirectional"))
    )
    (net (code "49") (name "Net-(U$14-CO)") (class "Default")
      (node (ref "U$14") (pin "CL_OUT") (pinfunction "CO_CL_OUT") (pintype "bidirectional"))
      (node (ref "U$15") (pin "C_IN") (pinfunction "CI_C_IN") (pintype "bidirectional"))
    )
    (net (code "50") (name "Net-(U$14-DO)") (class "Default")
      (node (ref "U$14") (pin "D_OUT") (pinfunction "DO_D_OUT") (pintype "bidirectional"))
      (node (ref "U$15") (pin "D_IN") (pinfunction "DI_D_IN") (pintype "bidirectional"))
    )
    (net (code "51") (name "Net-(U$15-CO)") (class "Default")
      (node (ref "U$15") (pin "CL_OUT") (pinfunction "CO_CL_OUT") (pintype "bidirectional"))
      (node (ref "U$18") (pin "C_IN") (pinfunction "CI_C_IN") (pintype "bidirectional"))
    )
    (net (code "52") (name "Net-(U$15-DO)") (class "Default")
      (node (ref "U$15") (pin "D_OUT") (pinfunction "DO_D_OUT") (pintype "bidirectional"))
      (node (ref "U$18") (pin "D_IN") (pinfunction "DI_D_IN") (pintype "bidirectional"))
    )
    (net (code "53") (name "Net-(U$18-CO)") (class "Default")
      (node (ref "U$18") (pin "CL_OUT") (pinfunction "CO_CL_OUT") (pintype "bidirectional"))
      (node (ref "U$19") (pin "C_IN") (pinfunction "CI_C_IN") (pintype "bidirectional"))
    )
    (net (code "54") (name "Net-(U$18-DO)") (class "Default")
      (node (ref "U$18") (pin "D_OUT") (pinfunction "DO_D_OUT") (pintype "bidirectional"))
      (node (ref "U$19") (pin "D_IN") (pinfunction "DI_D_IN") (pintype "bidirectional"))
    )
    (net (code "55") (name "Net-(U$19-CO)") (class "Default")
      (node (ref "U$19") (pin "CL_OUT") (pinfunction "CO_CL_OUT") (pintype "bidirectional"))
      (node (ref "U$20") (pin "C_IN") (pinfunction "CI_C_IN") (pintype "bidirectional"))
    )
    (net (code "56") (name "Net-(U$19-DO)") (class "Default")
      (node (ref "U$19") (pin "D_OUT") (pinfunction "DO_D_OUT") (pintype "bidirectional"))
      (node (ref "U$20") (pin "D_IN") (pinfunction "DI_D_IN") (pintype "bidirectional"))
    )
    (net (code "57") (name "Net-(U$20-CO)") (class "Default")
      (node (ref "U$20") (pin "CL_OUT") (pinfunction "CO_CL_OUT") (pintype "bidirectional"))
      (node (ref "U$21") (pin "C_IN") (pinfunction "CI_C_IN") (pintype "bidirectional"))
    )
    (net (code "58") (name "Net-(U$20-DO)") (class "Default")
      (node (ref "U$20") (pin "D_OUT") (pinfunction "DO_D_OUT") (pintype "bidirectional"))
      (node (ref "U$21") (pin "D_IN") (pinfunction "DI_D_IN") (pintype "bidirectional"))
    )
    (net (code "59") (name "Net-(U$21-CO)") (class "Default")
      (node (ref "U$21") (pin "CL_OUT") (pinfunction "CO_CL_OUT") (pintype "bidirectional"))
      (node (ref "U$22") (pin "C_IN") (pinfunction "CI_C_IN") (pintype "bidirectional"))
    )
    (net (code "60") (name "Net-(U$21-DO)") (class "Default")
      (node (ref "U$21") (pin "D_OUT") (pinfunction "DO_D_OUT") (pintype "bidirectional"))
      (node (ref "U$22") (pin "D_IN") (pinfunction "DI_D_IN") (pintype "bidirectional"))
    )
    (net (code "61") (name "Net-(U$22-CO)") (class "Default")
      (node (ref "U$22") (pin "CL_OUT") (pinfunction "CO_CL_OUT") (pintype "bidirectional"))
      (node (ref "U$24") (pin "C_IN") (pinfunction "CI_C_IN") (pintype "bidirectional"))
    )
    (net (code "62") (name "Net-(U$22-DO)") (class "Default")
      (node (ref "U$22") (pin "D_OUT") (pinfunction "DO_D_OUT") (pintype "bidirectional"))
      (node (ref "U$24") (pin "D_IN") (pinfunction "DI_D_IN") (pintype "bidirectional"))
    )
    (net (code "63") (name "Net-(U$24-CO)") (class "Default")
      (node (ref "U$24") (pin "CL_OUT") (pinfunction "CO_CL_OUT") (pintype "bidirectional"))
      (node (ref "U$25") (pin "C_IN") (pinfunction "CI_C_IN") (pintype "bidirectional"))
    )
    (net (code "64") (name "Net-(U$24-DO)") (class "Default")
      (node (ref "U$24") (pin "D_OUT") (pinfunction "DO_D_OUT") (pintype "bidirectional"))
      (node (ref "U$25") (pin "D_IN") (pinfunction "DI_D_IN") (pintype "bidirectional"))
    )
    (net (code "65") (name "Net-(U$25-CO)") (class "Default")
      (node (ref "U$25") (pin "CL_OUT") (pinfunction "CO_CL_OUT") (pintype "bidirectional"))
      (node (ref "U$27") (pin "C_IN") (pinfunction "CI_C_IN") (pintype "bidirectional"))
    )
    (net (code "66") (name "Net-(U$25-DO)") (class "Default")
      (node (ref "U$25") (pin "D_OUT") (pinfunction "DO_D_OUT") (pintype "bidirectional"))
      (node (ref "U$27") (pin "D_IN") (pinfunction "DI_D_IN") (pintype "bidirectional"))
    )
    (net (code "67") (name "Net-(U$27-CO)") (class "Default")
      (node (ref "U$27") (pin "CL_OUT") (pinfunction "CO_CL_OUT") (pintype "bidirectional"))
      (node (ref "U$28") (pin "C_IN") (pinfunction "CI_C_IN") (pintype "bidirectional"))
    )
    (net (code "68") (name "Net-(U$27-DO)") (class "Default")
      (node (ref "U$27") (pin "D_OUT") (pinfunction "DO_D_OUT") (pintype "bidirectional"))
      (node (ref "U$28") (pin "D_IN") (pinfunction "DI_D_IN") (pintype "bidirectional"))
    )
    (net (code "69") (name "Net-(U$28-CO)") (class "Default")
      (node (ref "U$28") (pin "CL_OUT") (pinfunction "CO_CL_OUT") (pintype "bidirectional"))
      (node (ref "U$29") (pin "C_IN") (pinfunction "CI_C_IN") (pintype "bidirectional"))
    )
    (net (code "70") (name "Net-(U$28-DO)") (class "Default")
      (node (ref "U$28") (pin "D_OUT") (pinfunction "DO_D_OUT") (pintype "bidirectional"))
      (node (ref "U$29") (pin "D_IN") (pinfunction "DI_D_IN") (pintype "bidirectional"))
    )
    (net (code "71") (name "Net-(U$29-CO)") (class "Default")
      (node (ref "U$29") (pin "CL_OUT") (pinfunction "CO_CL_OUT") (pintype "bidirectional"))
      (node (ref "U$30") (pin "C_IN") (pinfunction "CI_C_IN") (pintype "bidirectional"))
    )
    (net (code "72") (name "Net-(U$29-DO)") (class "Default")
      (node (ref "U$29") (pin "D_OUT") (pinfunction "DO_D_OUT") (pintype "bidirectional"))
      (node (ref "U$30") (pin "D_IN") (pinfunction "DI_D_IN") (pintype "bidirectional"))
    )
    (net (code "73") (name "Net-(U$30-CO)") (class "Default")
      (node (ref "U$30") (pin "CL_OUT") (pinfunction "CO_CL_OUT") (pintype "bidirectional"))
      (node (ref "U$31") (pin "C_IN") (pinfunction "CI_C_IN") (pintype "bidirectional"))
    )
    (net (code "74") (name "Net-(U$30-DO)") (class "Default")
      (node (ref "U$30") (pin "D_OUT") (pinfunction "DO_D_OUT") (pintype "bidirectional"))
      (node (ref "U$31") (pin "D_IN") (pinfunction "DI_D_IN") (pintype "bidirectional"))
    )
    (net (code "75") (name "Net-(U$32-CO)") (class "Default")
      (node (ref "U$32") (pin "CL_OUT") (pinfunction "CO_CL_OUT") (pintype "bidirectional"))
      (node (ref "U$33") (pin "C_IN") (pinfunction "CI_C_IN") (pintype "bidirectional"))
    )
    (net (code "76") (name "Net-(U$32-DO)") (class "Default")
      (node (ref "U$32") (pin "D_OUT") (pinfunction "DO_D_OUT") (pintype "bidirectional"))
      (node (ref "U$33") (pin "D_IN") (pinfunction "DI_D_IN") (pintype "bidirectional"))
    )
    (net (code "77") (name "Net-(U$33-CO)") (class "Default")
      (node (ref "U$33") (pin "CL_OUT") (pinfunction "CO_CL_OUT") (pintype "bidirectional"))
      (node (ref "U$34") (pin "C_IN") (pinfunction "CI_C_IN") (pintype "bidirectional"))
    )
    (net (code "78") (name "Net-(U$33-DO)") (class "Default")
      (node (ref "U$33") (pin "D_OUT") (pinfunction "DO_D_OUT") (pintype "bidirectional"))
      (node (ref "U$34") (pin "D_IN") (pinfunction "DI_D_IN") (pintype "bidirectional"))
    )
    (net (code "79") (name "Net-(U$34-CO)") (class "Default")
      (node (ref "U$34") (pin "CL_OUT") (pinfunction "CO_CL_OUT") (pintype "bidirectional"))
      (node (ref "U$35") (pin "C_IN") (pinfunction "CI_C_IN") (pintype "bidirectional"))
    )
    (net (code "80") (name "Net-(U$34-DO)") (class "Default")
      (node (ref "U$34") (pin "D_OUT") (pinfunction "DO_D_OUT") (pintype "bidirectional"))
      (node (ref "U$35") (pin "D_IN") (pinfunction "DI_D_IN") (pintype "bidirectional"))
    )
    (net (code "81") (name "Net-(U$35-CO)") (class "Default")
      (node (ref "U$35") (pin "CL_OUT") (pinfunction "CO_CL_OUT") (pintype "bidirectional"))
      (node (ref "U$36") (pin "C_IN") (pinfunction "CI_C_IN") (pintype "bidirectional"))
    )
    (net (code "82") (name "Net-(U$35-DO)") (class "Default")
      (node (ref "U$35") (pin "D_OUT") (pinfunction "DO_D_OUT") (pintype "bidirectional"))
      (node (ref "U$36") (pin "D_IN") (pinfunction "DI_D_IN") (pintype "bidirectional"))
    )
    (net (code "83") (name "Net-(U$36-CO)") (class "Default")
      (node (ref "U$36") (pin "CL_OUT") (pinfunction "CO_CL_OUT") (pintype "bidirectional"))
      (node (ref "U$37") (pin "C_IN") (pinfunction "CI_C_IN") (pintype "bidirectional"))
    )
    (net (code "84") (name "Net-(U$36-DO)") (class "Default")
      (node (ref "U$36") (pin "D_OUT") (pinfunction "DO_D_OUT") (pintype "bidirectional"))
      (node (ref "U$37") (pin "D_IN") (pinfunction "DI_D_IN") (pintype "bidirectional"))
    )
    (net (code "85") (name "Net-(U$37-CO)") (class "Default")
      (node (ref "U$37") (pin "CL_OUT") (pinfunction "CO_CL_OUT") (pintype "bidirectional"))
      (node (ref "U$38") (pin "C_IN") (pinfunction "CI_C_IN") (pintype "bidirectional"))
    )
    (net (code "86") (name "Net-(U$37-DO)") (class "Default")
      (node (ref "U$37") (pin "D_OUT") (pinfunction "DO_D_OUT") (pintype "bidirectional"))
      (node (ref "U$38") (pin "D_IN") (pinfunction "DI_D_IN") (pintype "bidirectional"))
    )
    (net (code "87") (name "Net-(U$38-CO)") (class "Default")
      (node (ref "U$38") (pin "CL_OUT") (pinfunction "CO_CL_OUT") (pintype "bidirectional"))
      (node (ref "U$39") (pin "C_IN") (pinfunction "CI_C_IN") (pintype "bidirectional"))
    )
    (net (code "88") (name "Net-(U$38-DO)") (class "Default")
      (node (ref "U$38") (pin "D_OUT") (pinfunction "DO_D_OUT") (pintype "bidirectional"))
      (node (ref "U$39") (pin "D_IN") (pinfunction "DI_D_IN") (pintype "bidirectional"))
    )
    (net (code "89") (name "Net-(U$39-CO)") (class "Default")
      (node (ref "U$39") (pin "CL_OUT") (pinfunction "CO_CL_OUT") (pintype "bidirectional"))
      (node (ref "U$40") (pin "C_IN") (pinfunction "CI_C_IN") (pintype "bidirectional"))
    )
    (net (code "90") (name "Net-(U$39-DO)") (class "Default")
      (node (ref "U$39") (pin "D_OUT") (pinfunction "DO_D_OUT") (pintype "bidirectional"))
      (node (ref "U$40") (pin "D_IN") (pinfunction "DI_D_IN") (pintype "bidirectional"))
    )
    (net (code "91") (name "Net-(U$40-CO)") (class "Default")
      (node (ref "U$40") (pin "CL_OUT") (pinfunction "CO_CL_OUT") (pintype "bidirectional"))
      (node (ref "U$41") (pin "C_IN") (pinfunction "CI_C_IN") (pintype "bidirectional"))
    )
    (net (code "92") (name "Net-(U$40-DO)") (class "Default")
      (node (ref "U$40") (pin "D_OUT") (pinfunction "DO_D_OUT") (pintype "bidirectional"))
      (node (ref "U$41") (pin "D_IN") (pinfunction "DI_D_IN") (pintype "bidirectional"))
    )
    (net (code "93") (name "Net-(U$41-CO)") (class "Default")
      (node (ref "U$41") (pin "CL_OUT") (pinfunction "CO_CL_OUT") (pintype "bidirectional"))
      (node (ref "U$42") (pin "C_IN") (pinfunction "CI_C_IN") (pintype "bidirectional"))
    )
    (net (code "94") (name "Net-(U$41-DO)") (class "Default")
      (node (ref "U$41") (pin "D_OUT") (pinfunction "DO_D_OUT") (pintype "bidirectional"))
      (node (ref "U$42") (pin "D_IN") (pinfunction "DI_D_IN") (pintype "bidirectional"))
    )
    (net (code "95") (name "Net-(U$42-CO)") (class "Default")
      (node (ref "U$42") (pin "CL_OUT") (pinfunction "CO_CL_OUT") (pintype "bidirectional"))
      (node (ref "U$43") (pin "C_IN") (pinfunction "CI_C_IN") (pintype "bidirectional"))
    )
    (net (code "96") (name "Net-(U$42-DO)") (class "Default")
      (node (ref "U$42") (pin "D_OUT") (pinfunction "DO_D_OUT") (pintype "bidirectional"))
      (node (ref "U$43") (pin "D_IN") (pinfunction "DI_D_IN") (pintype "bidirectional"))
    )
    (net (code "97") (name "Net-(U$43-CO)") (class "Default")
      (node (ref "U$43") (pin "CL_OUT") (pinfunction "CO_CL_OUT") (pintype "bidirectional"))
      (node (ref "U$44") (pin "C_IN") (pinfunction "CI_C_IN") (pintype "bidirectional"))
    )
    (net (code "98") (name "Net-(U$43-DO)") (class "Default")
      (node (ref "U$43") (pin "D_OUT") (pinfunction "DO_D_OUT") (pintype "bidirectional"))
      (node (ref "U$44") (pin "D_IN") (pinfunction "DI_D_IN") (pintype "bidirectional"))
    )
    (net (code "99") (name "Net-(U$44-CO)") (class "Default")
      (node (ref "U$44") (pin "CL_OUT") (pinfunction "CO_CL_OUT") (pintype "bidirectional"))
      (node (ref "U$45") (pin "C_IN") (pinfunction "CI_C_IN") (pintype "bidirectional"))
    )
    (net (code "100") (name "Net-(U$44-DO)") (class "Default")
      (node (ref "U$44") (pin "D_OUT") (pinfunction "DO_D_OUT") (pintype "bidirectional"))
      (node (ref "U$45") (pin "D_IN") (pinfunction "DI_D_IN") (pintype "bidirectional"))
    )
    (net (code "101") (name "Net-(U$45-CO)") (class "Default")
      (node (ref "U$45") (pin "CL_OUT") (pinfunction "CO_CL_OUT") (pintype "bidirectional"))
      (node (ref "U$46") (pin "C_IN") (pinfunction "CI_C_IN") (pintype "bidirectional"))
    )
    (net (code "102") (name "Net-(U$45-DO)") (class "Default")
      (node (ref "U$45") (pin "D_OUT") (pinfunction "DO_D_OUT") (pintype "bidirectional"))
      (node (ref "U$46") (pin "D_IN") (pinfunction "DI_D_IN") (pintype "bidirectional"))
    )
    (net (code "103") (name "Net-(U$46-CO)") (class "Default")
      (node (ref "U$46") (pin "CL_OUT") (pinfunction "CO_CL_OUT") (pintype "bidirectional"))
      (node (ref "U$47") (pin "C_IN") (pinfunction "CI_C_IN") (pintype "bidirectional"))
    )
    (net (code "104") (name "Net-(U$46-DO)") (class "Default")
      (node (ref "U$46") (pin "D_OUT") (pinfunction "DO_D_OUT") (pintype "bidirectional"))
      (node (ref "U$47") (pin "D_IN") (pinfunction "DI_D_IN") (pintype "bidirectional"))
    )
    (net (code "105") (name "Net-(U$47-CO)") (class "Default")
      (node (ref "U$47") (pin "CL_OUT") (pinfunction "CO_CL_OUT") (pintype "bidirectional"))
      (node (ref "U$48") (pin "C_IN") (pinfunction "CI_C_IN") (pintype "bidirectional"))
    )
    (net (code "106") (name "Net-(U$47-DO)") (class "Default")
      (node (ref "U$47") (pin "D_OUT") (pinfunction "DO_D_OUT") (pintype "bidirectional"))
      (node (ref "U$48") (pin "D_IN") (pinfunction "DI_D_IN") (pintype "bidirectional"))
    )
    (net (code "107") (name "Net-(U$48-CO)") (class "Default")
      (node (ref "U$48") (pin "CL_OUT") (pinfunction "CO_CL_OUT") (pintype "bidirectional"))
      (node (ref "U$49") (pin "C_IN") (pinfunction "CI_C_IN") (pintype "bidirectional"))
    )
    (net (code "108") (name "Net-(U$48-DO)") (class "Default")
      (node (ref "U$48") (pin "D_OUT") (pinfunction "DO_D_OUT") (pintype "bidirectional"))
      (node (ref "U$49") (pin "D_IN") (pinfunction "DI_D_IN") (pintype "bidirectional"))
    )
    (net (code "109") (name "Net-(U$49-CO)") (class "Default")
      (node (ref "U$49") (pin "CL_OUT") (pinfunction "CO_CL_OUT") (pintype "bidirectional"))
      (node (ref "U$50") (pin "C_IN") (pinfunction "CI_C_IN") (pintype "bidirectional"))
    )
    (net (code "110") (name "Net-(U$49-DO)") (class "Default")
      (node (ref "U$49") (pin "D_OUT") (pinfunction "DO_D_OUT") (pintype "bidirectional"))
      (node (ref "U$50") (pin "D_IN") (pinfunction "DI_D_IN") (pintype "bidirectional"))
    )
    (net (code "111") (name "Net-(U$50-CO)") (class "Default")
      (node (ref "U$50") (pin "CL_OUT") (pinfunction "CO_CL_OUT") (pintype "bidirectional"))
      (node (ref "U$51") (pin "C_IN") (pinfunction "CI_C_IN") (pintype "bidirectional"))
    )
    (net (code "112") (name "Net-(U$50-DO)") (class "Default")
      (node (ref "U$50") (pin "D_OUT") (pinfunction "DO_D_OUT") (pintype "bidirectional"))
      (node (ref "U$51") (pin "D_IN") (pinfunction "DI_D_IN") (pintype "bidirectional"))
    )
    (net (code "113") (name "Net-(U$51-CO)") (class "Default")
      (node (ref "U$51") (pin "CL_OUT") (pinfunction "CO_CL_OUT") (pintype "bidirectional"))
      (node (ref "U$52") (pin "C_IN") (pinfunction "CI_C_IN") (pintype "bidirectional"))
    )
    (net (code "114") (name "Net-(U$51-DO)") (class "Default")
      (node (ref "U$51") (pin "D_OUT") (pinfunction "DO_D_OUT") (pintype "bidirectional"))
      (node (ref "U$52") (pin "D_IN") (pinfunction "DI_D_IN") (pintype "bidirectional"))
    )
    (net (code "115") (name "Net-(U$52-CO)") (class "Default")
      (node (ref "U$52") (pin "CL_OUT") (pinfunction "CO_CL_OUT") (pintype "bidirectional"))
      (node (ref "U$53") (pin "C_IN") (pinfunction "CI_C_IN") (pintype "bidirectional"))
    )
    (net (code "116") (name "Net-(U$52-DO)") (class "Default")
      (node (ref "U$52") (pin "D_OUT") (pinfunction "DO_D_OUT") (pintype "bidirectional"))
      (node (ref "U$53") (pin "D_IN") (pinfunction "DI_D_IN") (pintype "bidirectional"))
    )
    (net (code "117") (name "Net-(U$53-CO)") (class "Default")
      (node (ref "U$53") (pin "CL_OUT") (pinfunction "CO_CL_OUT") (pintype "bidirectional"))
      (node (ref "U$54") (pin "C_IN") (pinfunction "CI_C_IN") (pintype "bidirectional"))
    )
    (net (code "118") (name "Net-(U$53-DO)") (class "Default")
      (node (ref "U$53") (pin "D_OUT") (pinfunction "DO_D_OUT") (pintype "bidirectional"))
      (node (ref "U$54") (pin "D_IN") (pinfunction "DI_D_IN") (pintype "bidirectional"))
    )
    (net (code "119") (name "Net-(U$54-CO)") (class "Default")
      (node (ref "U$54") (pin "CL_OUT") (pinfunction "CO_CL_OUT") (pintype "bidirectional"))
      (node (ref "U$55") (pin "C_IN") (pinfunction "CI_C_IN") (pintype "bidirectional"))
    )
    (net (code "120") (name "Net-(U$54-DO)") (class "Default")
      (node (ref "U$54") (pin "D_OUT") (pinfunction "DO_D_OUT") (pintype "bidirectional"))
      (node (ref "U$55") (pin "D_IN") (pinfunction "DI_D_IN") (pintype "bidirectional"))
    )
    (net (code "121") (name "Net-(U$55-CO)") (class "Default")
      (node (ref "U$55") (pin "CL_OUT") (pinfunction "CO_CL_OUT") (pintype "bidirectional"))
      (node (ref "U$56") (pin "C_IN") (pinfunction "CI_C_IN") (pintype "bidirectional"))
    )
    (net (code "122") (name "Net-(U$55-DO)") (class "Default")
      (node (ref "U$55") (pin "D_OUT") (pinfunction "DO_D_OUT") (pintype "bidirectional"))
      (node (ref "U$56") (pin "D_IN") (pinfunction "DI_D_IN") (pintype "bidirectional"))
    )
    (net (code "123") (name "Net-(U$56-CO)") (class "Default")
      (node (ref "U$56") (pin "CL_OUT") (pinfunction "CO_CL_OUT") (pintype "bidirectional"))
      (node (ref "U$57") (pin "C_IN") (pinfunction "CI_C_IN") (pintype "bidirectional"))
    )
    (net (code "124") (name "Net-(U$56-DO)") (class "Default")
      (node (ref "U$56") (pin "D_OUT") (pinfunction "DO_D_OUT") (pintype "bidirectional"))
      (node (ref "U$57") (pin "D_IN") (pinfunction "DI_D_IN") (pintype "bidirectional"))
    )
    (net (code "125") (name "Net-(U$57-CO)") (class "Default")
      (node (ref "U$57") (pin "CL_OUT") (pinfunction "CO_CL_OUT") (pintype "bidirectional"))
      (node (ref "U$58") (pin "C_IN") (pinfunction "CI_C_IN") (pintype "bidirectional"))
    )
    (net (code "126") (name "Net-(U$57-DO)") (class "Default")
      (node (ref "U$57") (pin "D_OUT") (pinfunction "DO_D_OUT") (pintype "bidirectional"))
      (node (ref "U$58") (pin "D_IN") (pinfunction "DI_D_IN") (pintype "bidirectional"))
    )
    (net (code "127") (name "Net-(U$58-CO)") (class "Default")
      (node (ref "U$58") (pin "CL_OUT") (pinfunction "CO_CL_OUT") (pintype "bidirectional"))
      (node (ref "U$59") (pin "C_IN") (pinfunction "CI_C_IN") (pintype "bidirectional"))
    )
    (net (code "128") (name "Net-(U$58-DO)") (class "Default")
      (node (ref "U$58") (pin "D_OUT") (pinfunction "DO_D_OUT") (pintype "bidirectional"))
      (node (ref "U$59") (pin "D_IN") (pinfunction "DI_D_IN") (pintype "bidirectional"))
    )
    (net (code "129") (name "Net-(U$59-CO)") (class "Default")
      (node (ref "U$59") (pin "CL_OUT") (pinfunction "CO_CL_OUT") (pintype "bidirectional"))
      (node (ref "U$60") (pin "C_IN") (pinfunction "CI_C_IN") (pintype "bidirectional"))
    )
    (net (code "130") (name "Net-(U$59-DO)") (class "Default")
      (node (ref "U$59") (pin "D_OUT") (pinfunction "DO_D_OUT") (pintype "bidirectional"))
      (node (ref "U$60") (pin "D_IN") (pinfunction "DI_D_IN") (pintype "bidirectional"))
    )
    (net (code "131") (name "Net-(U$60-CO)") (class "Default")
      (node (ref "U$60") (pin "CL_OUT") (pinfunction "CO_CL_OUT") (pintype "bidirectional"))
      (node (ref "U$61") (pin "C_IN") (pinfunction "CI_C_IN") (pintype "bidirectional"))
    )
    (net (code "132") (name "Net-(U$60-DO)") (class "Default")
      (node (ref "U$60") (pin "D_OUT") (pinfunction "DO_D_OUT") (pintype "bidirectional"))
      (node (ref "U$61") (pin "D_IN") (pinfunction "DI_D_IN") (pintype "bidirectional"))
    )
    (net (code "133") (name "Net-(U$61-CO)") (class "Default")
      (node (ref "U$61") (pin "CL_OUT") (pinfunction "CO_CL_OUT") (pintype "bidirectional"))
      (node (ref "U$62") (pin "C_IN") (pinfunction "CI_C_IN") (pintype "bidirectional"))
    )
    (net (code "134") (name "Net-(U$61-DO)") (class "Default")
      (node (ref "U$61") (pin "D_OUT") (pinfunction "DO_D_OUT") (pintype "bidirectional"))
      (node (ref "U$62") (pin "D_IN") (pinfunction "DI_D_IN") (pintype "bidirectional"))
    )
    (net (code "135") (name "Net-(U$62-CO)") (class "Default")
      (node (ref "U$62") (pin "CL_OUT") (pinfunction "CO_CL_OUT") (pintype "bidirectional"))
      (node (ref "U$63") (pin "C_IN") (pinfunction "CI_C_IN") (pintype "bidirectional"))
    )
    (net (code "136") (name "Net-(U$62-DO)") (class "Default")
      (node (ref "U$62") (pin "D_OUT") (pinfunction "DO_D_OUT") (pintype "bidirectional"))
      (node (ref "U$63") (pin "D_IN") (pinfunction "DI_D_IN") (pintype "bidirectional"))
    )
    (net (code "137") (name "Net-(U$63-CO)") (class "Default")
      (node (ref "U$63") (pin "CL_OUT") (pinfunction "CO_CL_OUT") (pintype "bidirectional"))
      (node (ref "U$64") (pin "C_IN") (pinfunction "CI_C_IN") (pintype "bidirectional"))
    )
    (net (code "138") (name "Net-(U$63-DO)") (class "Default")
      (node (ref "U$63") (pin "D_OUT") (pinfunction "DO_D_OUT") (pintype "bidirectional"))
      (node (ref "U$64") (pin "D_IN") (pinfunction "DI_D_IN") (pintype "bidirectional"))
    )
    (net (code "139") (name "Net-(U$64-CO)") (class "Default")
      (node (ref "U$64") (pin "CL_OUT") (pinfunction "CO_CL_OUT") (pintype "bidirectional"))
      (node (ref "U$65") (pin "C_IN") (pinfunction "CI_C_IN") (pintype "bidirectional"))
    )
    (net (code "140") (name "Net-(U$64-DO)") (class "Default")
      (node (ref "U$64") (pin "D_OUT") (pinfunction "DO_D_OUT") (pintype "bidirectional"))
      (node (ref "U$65") (pin "D_IN") (pinfunction "DI_D_IN") (pintype "bidirectional"))
    )
    (net (code "141") (name "Net-(U$65-CO)") (class "Default")
      (node (ref "U$65") (pin "CL_OUT") (pinfunction "CO_CL_OUT") (pintype "bidirectional"))
      (node (ref "U$66") (pin "C_IN") (pinfunction "CI_C_IN") (pintype "bidirectional"))
    )
    (net (code "142") (name "Net-(U$65-DO)") (class "Default")
      (node (ref "U$65") (pin "D_OUT") (pinfunction "DO_D_OUT") (pintype "bidirectional"))
      (node (ref "U$66") (pin "D_IN") (pinfunction "DI_D_IN") (pintype "bidirectional"))
    )
    (net (code "143") (name "Net-(U$66-CO)") (class "Default")
      (node (ref "U$66") (pin "CL_OUT") (pinfunction "CO_CL_OUT") (pintype "bidirectional"))
      (node (ref "U$67") (pin "C_IN") (pinfunction "CI_C_IN") (pintype "bidirectional"))
    )
    (net (code "144") (name "Net-(U$66-DO)") (class "Default")
      (node (ref "U$66") (pin "D_OUT") (pinfunction "DO_D_OUT") (pintype "bidirectional"))
      (node (ref "U$67") (pin "D_IN") (pinfunction "DI_D_IN") (pintype "bidirectional"))
    )
    (net (code "145") (name "Net-(U$67-CO)") (class "Default")
      (node (ref "U$67") (pin "CL_OUT") (pinfunction "CO_CL_OUT") (pintype "bidirectional"))
      (node (ref "U$68") (pin "C_IN") (pinfunction "CI_C_IN") (pintype "bidirectional"))
    )
    (net (code "146") (name "Net-(U$67-DO)") (class "Default")
      (node (ref "U$67") (pin "D_OUT") (pinfunction "DO_D_OUT") (pintype "bidirectional"))
      (node (ref "U$68") (pin "D_IN") (pinfunction "DI_D_IN") (pintype "bidirectional"))
    )
    (net (code "147") (name "Net-(U$68-CO)") (class "Default")
      (node (ref "U$68") (pin "CL_OUT") (pinfunction "CO_CL_OUT") (pintype "bidirectional"))
      (node (ref "U$69") (pin "C_IN") (pinfunction "CI_C_IN") (pintype "bidirectional"))
    )
    (net (code "148") (name "Net-(U$68-DO)") (class "Default")
      (node (ref "U$68") (pin "D_OUT") (pinfunction "DO_D_OUT") (pintype "bidirectional"))
      (node (ref "U$69") (pin "D_IN") (pinfunction "DI_D_IN") (pintype "bidirectional"))
    )
    (net (code "149") (name "Net-(U$69-CO)") (class "Default")
      (node (ref "U$69") (pin "CL_OUT") (pinfunction "CO_CL_OUT") (pintype "bidirectional"))
      (node (ref "U$70") (pin "C_IN") (pinfunction "CI_C_IN") (pintype "bidirectional"))
    )
    (net (code "150") (name "Net-(U$69-DO)") (class "Default")
      (node (ref "U$69") (pin "D_OUT") (pinfunction "DO_D_OUT") (pintype "bidirectional"))
      (node (ref "U$70") (pin "D_IN") (pinfunction "DI_D_IN") (pintype "bidirectional"))
    )
    (net (code "151") (name "Net-(U$70-CO)") (class "Default")
      (node (ref "U$70") (pin "CL_OUT") (pinfunction "CO_CL_OUT") (pintype "bidirectional"))
      (node (ref "U$71") (pin "C_IN") (pinfunction "CI_C_IN") (pintype "bidirectional"))
    )
    (net (code "152") (name "Net-(U$70-DO)") (class "Default")
      (node (ref "U$70") (pin "D_OUT") (pinfunction "DO_D_OUT") (pintype "bidirectional"))
      (node (ref "U$71") (pin "D_IN") (pinfunction "DI_D_IN") (pintype "bidirectional"))
    )
    (net (code "153") (name "Net-(U$71-CO)") (class "Default")
      (node (ref "U$71") (pin "CL_OUT") (pinfunction "CO_CL_OUT") (pintype "bidirectional"))
      (node (ref "U$72") (pin "C_IN") (pinfunction "CI_C_IN") (pintype "bidirectional"))
    )
    (net (code "154") (name "Net-(U$71-DO)") (class "Default")
      (node (ref "U$71") (pin "D_OUT") (pinfunction "DO_D_OUT") (pintype "bidirectional"))
      (node (ref "U$72") (pin "D_IN") (pinfunction "DI_D_IN") (pintype "bidirectional"))
    )
    (net (code "155") (name "Net-(U$72-CO)") (class "Default")
      (node (ref "U$72") (pin "CL_OUT") (pinfunction "CO_CL_OUT") (pintype "bidirectional"))
      (node (ref "U$73") (pin "C_IN") (pinfunction "CI_C_IN") (pintype "bidirectional"))
    )
    (net (code "156") (name "Net-(U$72-DO)") (class "Default")
      (node (ref "U$72") (pin "D_OUT") (pinfunction "DO_D_OUT") (pintype "bidirectional"))
      (node (ref "U$73") (pin "D_IN") (pinfunction "DI_D_IN") (pintype "bidirectional"))
    )
    (net (code "157") (name "Net-(U$73-CO)") (class "Default")
      (node (ref "U$73") (pin "CL_OUT") (pinfunction "CO_CL_OUT") (pintype "bidirectional"))
      (node (ref "U$74") (pin "C_IN") (pinfunction "CI_C_IN") (pintype "bidirectional"))
    )
    (net (code "158") (name "Net-(U$73-DO)") (class "Default")
      (node (ref "U$73") (pin "D_OUT") (pinfunction "DO_D_OUT") (pintype "bidirectional"))
      (node (ref "U$74") (pin "D_IN") (pinfunction "DI_D_IN") (pintype "bidirectional"))
    )
    (net (code "159") (name "Net-(U$74-CO)") (class "Default")
      (node (ref "U$74") (pin "CL_OUT") (pinfunction "CO_CL_OUT") (pintype "bidirectional"))
      (node (ref "U$75") (pin "C_IN") (pinfunction "CI_C_IN") (pintype "bidirectional"))
    )
    (net (code "160") (name "Net-(U$74-DO)") (class "Default")
      (node (ref "U$74") (pin "D_OUT") (pinfunction "DO_D_OUT") (pintype "bidirectional"))
      (node (ref "U$75") (pin "D_IN") (pinfunction "DI_D_IN") (pintype "bidirectional"))
    )
    (net (code "161") (name "Net-(U$75-CO)") (class "Default")
      (node (ref "U$75") (pin "CL_OUT") (pinfunction "CO_CL_OUT") (pintype "bidirectional"))
      (node (ref "U$76") (pin "C_IN") (pinfunction "CI_C_IN") (pintype "bidirectional"))
    )
    (net (code "162") (name "Net-(U$75-DO)") (class "Default")
      (node (ref "U$75") (pin "D_OUT") (pinfunction "DO_D_OUT") (pintype "bidirectional"))
      (node (ref "U$76") (pin "D_IN") (pinfunction "DI_D_IN") (pintype "bidirectional"))
    )
    (net (code "163") (name "Net-(U$76-CO)") (class "Default")
      (node (ref "U$76") (pin "CL_OUT") (pinfunction "CO_CL_OUT") (pintype "bidirectional"))
      (node (ref "U$77") (pin "C_IN") (pinfunction "CI_C_IN") (pintype "bidirectional"))
    )
    (net (code "164") (name "Net-(U$76-DO)") (class "Default")
      (node (ref "U$76") (pin "D_OUT") (pinfunction "DO_D_OUT") (pintype "bidirectional"))
      (node (ref "U$77") (pin "D_IN") (pinfunction "DI_D_IN") (pintype "bidirectional"))
    )
    (net (code "165") (name "Net-(U$77-CO)") (class "Default")
      (node (ref "U$77") (pin "CL_OUT") (pinfunction "CO_CL_OUT") (pintype "bidirectional"))
      (node (ref "U$78") (pin "C_IN") (pinfunction "CI_C_IN") (pintype "bidirectional"))
    )
    (net (code "166") (name "Net-(U$77-DO)") (class "Default")
      (node (ref "U$77") (pin "D_OUT") (pinfunction "DO_D_OUT") (pintype "bidirectional"))
      (node (ref "U$78") (pin "D_IN") (pinfunction "DI_D_IN") (pintype "bidirectional"))
    )
    (net (code "167") (name "Net-(U$78-CO)") (class "Default")
      (node (ref "U$78") (pin "CL_OUT") (pinfunction "CO_CL_OUT") (pintype "bidirectional"))
      (node (ref "U$79") (pin "C_IN") (pinfunction "CI_C_IN") (pintype "bidirectional"))
    )
    (net (code "168") (name "Net-(U$78-DO)") (class "Default")
      (node (ref "U$78") (pin "D_OUT") (pinfunction "DO_D_OUT") (pintype "bidirectional"))
      (node (ref "U$79") (pin "D_IN") (pinfunction "DI_D_IN") (pintype "bidirectional"))
    )
    (net (code "169") (name "Net-(U$79-CO)") (class "Default")
      (node (ref "U$79") (pin "CL_OUT") (pinfunction "CO_CL_OUT") (pintype "bidirectional"))
      (node (ref "U$80") (pin "C_IN") (pinfunction "CI_C_IN") (pintype "bidirectional"))
    )
    (net (code "170") (name "Net-(U$79-DO)") (class "Default")
      (node (ref "U$79") (pin "D_OUT") (pinfunction "DO_D_OUT") (pintype "bidirectional"))
      (node (ref "U$80") (pin "D_IN") (pinfunction "DI_D_IN") (pintype "bidirectional"))
    )
    (net (code "171") (name "Net-(U$80-CO)") (class "Default")
      (node (ref "U$80") (pin "CL_OUT") (pinfunction "CO_CL_OUT") (pintype "bidirectional"))
      (node (ref "U$81") (pin "C_IN") (pinfunction "CI_C_IN") (pintype "bidirectional"))
    )
    (net (code "172") (name "Net-(U$80-DO)") (class "Default")
      (node (ref "U$80") (pin "D_OUT") (pinfunction "DO_D_OUT") (pintype "bidirectional"))
      (node (ref "U$81") (pin "D_IN") (pinfunction "DI_D_IN") (pintype "bidirectional"))
    )
    (net (code "173") (name "Net-(U$81-CO)") (class "Default")
      (node (ref "U$81") (pin "CL_OUT") (pinfunction "CO_CL_OUT") (pintype "bidirectional"))
      (node (ref "U$82") (pin "C_IN") (pinfunction "CI_C_IN") (pintype "bidirectional"))
    )
    (net (code "174") (name "Net-(U$81-DO)") (class "Default")
      (node (ref "U$81") (pin "D_OUT") (pinfunction "DO_D_OUT") (pintype "bidirectional"))
      (node (ref "U$82") (pin "D_IN") (pinfunction "DI_D_IN") (pintype "bidirectional"))
    )
    (net (code "175") (name "Net-(U$82-CO)") (class "Default")
      (node (ref "U$82") (pin "CL_OUT") (pinfunction "CO_CL_OUT") (pintype "bidirectional"))
      (node (ref "U$83") (pin "C_IN") (pinfunction "CI_C_IN") (pintype "bidirectional"))
    )
    (net (code "176") (name "Net-(U$82-DO)") (class "Default")
      (node (ref "U$82") (pin "D_OUT") (pinfunction "DO_D_OUT") (pintype "bidirectional"))
      (node (ref "U$83") (pin "D_IN") (pinfunction "DI_D_IN") (pintype "bidirectional"))
    )
    (net (code "177") (name "Net-(U$83-CO)") (class "Default")
      (node (ref "U$83") (pin "CL_OUT") (pinfunction "CO_CL_OUT") (pintype "bidirectional"))
      (node (ref "U$84") (pin "C_IN") (pinfunction "CI_C_IN") (pintype "bidirectional"))
    )
    (net (code "178") (name "Net-(U$83-DO)") (class "Default")
      (node (ref "U$83") (pin "D_OUT") (pinfunction "DO_D_OUT") (pintype "bidirectional"))
      (node (ref "U$84") (pin "D_IN") (pinfunction "DI_D_IN") (pintype "bidirectional"))
    )
    (net (code "179") (name "Net-(U$84-CO)") (class "Default")
      (node (ref "U$84") (pin "CL_OUT") (pinfunction "CO_CL_OUT") (pintype "bidirectional"))
      (node (ref "U$85") (pin "C_IN") (pinfunction "CI_C_IN") (pintype "bidirectional"))
    )
    (net (code "180") (name "Net-(U$84-DO)") (class "Default")
      (node (ref "U$84") (pin "D_OUT") (pinfunction "DO_D_OUT") (pintype "bidirectional"))
      (node (ref "U$85") (pin "D_IN") (pinfunction "DI_D_IN") (pintype "bidirectional"))
    )
    (net (code "181") (name "Net-(U$85-CO)") (class "Default")
      (node (ref "U$85") (pin "CL_OUT") (pinfunction "CO_CL_OUT") (pintype "bidirectional"))
      (node (ref "U$86") (pin "C_IN") (pinfunction "CI_C_IN") (pintype "bidirectional"))
    )
    (net (code "182") (name "Net-(U$85-DO)") (class "Default")
      (node (ref "U$85") (pin "D_OUT") (pinfunction "DO_D_OUT") (pintype "bidirectional"))
      (node (ref "U$86") (pin "D_IN") (pinfunction "DI_D_IN") (pintype "bidirectional"))
    )
    (net (code "183") (name "Net-(U$86-CO)") (class "Default")
      (node (ref "U$86") (pin "CL_OUT") (pinfunction "CO_CL_OUT") (pintype "bidirectional"))
      (node (ref "U$87") (pin "C_IN") (pinfunction "CI_C_IN") (pintype "bidirectional"))
    )
    (net (code "184") (name "Net-(U$86-DO)") (class "Default")
      (node (ref "U$86") (pin "D_OUT") (pinfunction "DO_D_OUT") (pintype "bidirectional"))
      (node (ref "U$87") (pin "D_IN") (pinfunction "DI_D_IN") (pintype "bidirectional"))
    )
    (net (code "185") (name "Net-(U$87-CO)") (class "Default")
      (node (ref "U$87") (pin "CL_OUT") (pinfunction "CO_CL_OUT") (pintype "bidirectional"))
      (node (ref "U$88") (pin "C_IN") (pinfunction "CI_C_IN") (pintype "bidirectional"))
    )
    (net (code "186") (name "Net-(U$87-DO)") (class "Default")
      (node (ref "U$87") (pin "D_OUT") (pinfunction "DO_D_OUT") (pintype "bidirectional"))
      (node (ref "U$88") (pin "D_IN") (pinfunction "DI_D_IN") (pintype "bidirectional"))
    )
    (net (code "187") (name "Net-(U$88-CO)") (class "Default")
      (node (ref "U$88") (pin "CL_OUT") (pinfunction "CO_CL_OUT") (pintype "bidirectional"))
      (node (ref "U$89") (pin "C_IN") (pinfunction "CI_C_IN") (pintype "bidirectional"))
    )
    (net (code "188") (name "Net-(U$88-DO)") (class "Default")
      (node (ref "U$88") (pin "D_OUT") (pinfunction "DO_D_OUT") (pintype "bidirectional"))
      (node (ref "U$89") (pin "D_IN") (pinfunction "DI_D_IN") (pintype "bidirectional"))
    )
    (net (code "189") (name "Net-(U$89-CO)") (class "Default")
      (node (ref "U$89") (pin "CL_OUT") (pinfunction "CO_CL_OUT") (pintype "bidirectional"))
      (node (ref "U$90") (pin "C_IN") (pinfunction "CI_C_IN") (pintype "bidirectional"))
    )
    (net (code "190") (name "Net-(U$89-DO)") (class "Default")
      (node (ref "U$89") (pin "D_OUT") (pinfunction "DO_D_OUT") (pintype "bidirectional"))
      (node (ref "U$90") (pin "D_IN") (pinfunction "DI_D_IN") (pintype "bidirectional"))
    )
    (net (code "191") (name "Net-(U$90-CO)") (class "Default")
      (node (ref "U$90") (pin "CL_OUT") (pinfunction "CO_CL_OUT") (pintype "bidirectional"))
      (node (ref "U$91") (pin "C_IN") (pinfunction "CI_C_IN") (pintype "bidirectional"))
    )
    (net (code "192") (name "Net-(U$90-DO)") (class "Default")
      (node (ref "U$90") (pin "D_OUT") (pinfunction "DO_D_OUT") (pintype "bidirectional"))
      (node (ref "U$91") (pin "D_IN") (pinfunction "DI_D_IN") (pintype "bidirectional"))
    )
    (net (code "193") (name "Net-(U$91-CO)") (class "Default")
      (node (ref "U$91") (pin "CL_OUT") (pinfunction "CO_CL_OUT") (pintype "bidirectional"))
      (node (ref "U$92") (pin "C_IN") (pinfunction "CI_C_IN") (pintype "bidirectional"))
    )
    (net (code "194") (name "Net-(U$91-DO)") (class "Default")
      (node (ref "U$91") (pin "D_OUT") (pinfunction "DO_D_OUT") (pintype "bidirectional"))
      (node (ref "U$92") (pin "D_IN") (pinfunction "DI_D_IN") (pintype "bidirectional"))
    )
    (net (code "195") (name "Net-(U$92-CO)") (class "Default")
      (node (ref "U$92") (pin "CL_OUT") (pinfunction "CO_CL_OUT") (pintype "bidirectional"))
      (node (ref "U$93") (pin "C_IN") (pinfunction "CI_C_IN") (pintype "bidirectional"))
    )
    (net (code "196") (name "Net-(U$92-DO)") (class "Default")
      (node (ref "U$92") (pin "D_OUT") (pinfunction "DO_D_OUT") (pintype "bidirectional"))
      (node (ref "U$93") (pin "D_IN") (pinfunction "DI_D_IN") (pintype "bidirectional"))
    )
    (net (code "197") (name "Net-(U$93-CO)") (class "Default")
      (node (ref "U$93") (pin "CL_OUT") (pinfunction "CO_CL_OUT") (pintype "bidirectional"))
      (node (ref "U$94") (pin "C_IN") (pinfunction "CI_C_IN") (pintype "bidirectional"))
    )
    (net (code "198") (name "Net-(U$93-DO)") (class "Default")
      (node (ref "U$93") (pin "D_OUT") (pinfunction "DO_D_OUT") (pintype "bidirectional"))
      (node (ref "U$94") (pin "D_IN") (pinfunction "DI_D_IN") (pintype "bidirectional"))
    )
    (net (code "199") (name "Net-(U$94-CO)") (class "Default")
      (node (ref "U$94") (pin "CL_OUT") (pinfunction "CO_CL_OUT") (pintype "bidirectional"))
      (node (ref "U$95") (pin "C_IN") (pinfunction "CI_C_IN") (pintype "bidirectional"))
    )
    (net (code "200") (name "Net-(U$94-DO)") (class "Default")
      (node (ref "U$94") (pin "D_OUT") (pinfunction "DO_D_OUT") (pintype "bidirectional"))
      (node (ref "U$95") (pin "D_IN") (pinfunction "DI_D_IN") (pintype "bidirectional"))
    )
    (net (code "201") (name "Net-(U$95-CO)") (class "Default")
      (node (ref "U$95") (pin "CL_OUT") (pinfunction "CO_CL_OUT") (pintype "bidirectional"))
      (node (ref "U$96") (pin "C_IN") (pinfunction "CI_C_IN") (pintype "bidirectional"))
    )
    (net (code "202") (name "Net-(U$95-DO)") (class "Default")
      (node (ref "U$95") (pin "D_OUT") (pinfunction "DO_D_OUT") (pintype "bidirectional"))
      (node (ref "U$96") (pin "D_IN") (pinfunction "DI_D_IN") (pintype "bidirectional"))
    )
    (net (code "203") (name "Net-(U$96-CO)") (class "Default")
      (node (ref "U$96") (pin "CL_OUT") (pinfunction "CO_CL_OUT") (pintype "bidirectional"))
      (node (ref "U$97") (pin "C_IN") (pinfunction "CI_C_IN") (pintype "bidirectional"))
    )
    (net (code "204") (name "Net-(U$96-DO)") (class "Default")
      (node (ref "U$96") (pin "D_OUT") (pinfunction "DO_D_OUT") (pintype "bidirectional"))
      (node (ref "U$97") (pin "D_IN") (pinfunction "DI_D_IN") (pintype "bidirectional"))
    )
    (net (code "205") (name "Net-(U$97-CO)") (class "Default")
      (node (ref "U$97") (pin "CL_OUT") (pinfunction "CO_CL_OUT") (pintype "bidirectional"))
      (node (ref "U$98") (pin "C_IN") (pinfunction "CI_C_IN") (pintype "bidirectional"))
    )
    (net (code "206") (name "Net-(U$97-DO)") (class "Default")
      (node (ref "U$97") (pin "D_OUT") (pinfunction "DO_D_OUT") (pintype "bidirectional"))
      (node (ref "U$98") (pin "D_IN") (pinfunction "DI_D_IN") (pintype "bidirectional"))
    )
    (net (code "207") (name "Net-(U$98-CO)") (class "Default")
      (node (ref "U$98") (pin "CL_OUT") (pinfunction "CO_CL_OUT") (pintype "bidirectional"))
      (node (ref "U$99") (pin "C_IN") (pinfunction "CI_C_IN") (pintype "bidirectional"))
    )
    (net (code "208") (name "Net-(U$98-DO)") (class "Default")
      (node (ref "U$98") (pin "D_OUT") (pinfunction "DO_D_OUT") (pintype "bidirectional"))
      (node (ref "U$99") (pin "D_IN") (pinfunction "DI_D_IN") (pintype "bidirectional"))
    )
    (net (code "209") (name "Net-(U$100-CI)") (class "Default")
      (node (ref "U$100") (pin "C_IN") (pinfunction "CI_C_IN") (pintype "bidirectional"))
      (node (ref "U$99") (pin "CL_OUT") (pinfunction "CO_CL_OUT") (pintype "bidirectional"))
    )
    (net (code "210") (name "Net-(U$100-CO)") (class "Default")
      (node (ref "U$100") (pin "CL_OUT") (pinfunction "CO_CL_OUT") (pintype "bidirectional"))
      (node (ref "U$101") (pin "C_IN") (pinfunction "CI_C_IN") (pintype "bidirectional"))
    )
    (net (code "211") (name "Net-(U$100-DI)") (class "Default")
      (node (ref "U$100") (pin "D_IN") (pinfunction "DI_D_IN") (pintype "bidirectional"))
      (node (ref "U$99") (pin "D_OUT") (pinfunction "DO_D_OUT") (pintype "bidirectional"))
    )
    (net (code "212") (name "Net-(U$100-DO)") (class "Default")
      (node (ref "U$100") (pin "D_OUT") (pinfunction "DO_D_OUT") (pintype "bidirectional"))
      (node (ref "U$101") (pin "D_IN") (pinfunction "DI_D_IN") (pintype "bidirectional"))
    )
    (net (code "213") (name "Net-(U$101-CO)") (class "Default")
      (node (ref "U$101") (pin "CL_OUT") (pinfunction "CO_CL_OUT") (pintype "bidirectional"))
      (node (ref "U$102") (pin "C_IN") (pinfunction "CI_C_IN") (pintype "bidirectional"))
    )
    (net (code "214") (name "Net-(U$101-DO)") (class "Default")
      (node (ref "U$101") (pin "D_OUT") (pinfunction "DO_D_OUT") (pintype "bidirectional"))
      (node (ref "U$102") (pin "D_IN") (pinfunction "DI_D_IN") (pintype "bidirectional"))
    )
    (net (code "215") (name "Net-(U$102-CO)") (class "Default")
      (node (ref "U$102") (pin "CL_OUT") (pinfunction "CO_CL_OUT") (pintype "bidirectional"))
      (node (ref "U$103") (pin "C_IN") (pinfunction "CI_C_IN") (pintype "bidirectional"))
    )
    (net (code "216") (name "Net-(U$102-DO)") (class "Default")
      (node (ref "U$102") (pin "D_OUT") (pinfunction "DO_D_OUT") (pintype "bidirectional"))
      (node (ref "U$103") (pin "D_IN") (pinfunction "DI_D_IN") (pintype "bidirectional"))
    )
    (net (code "217") (name "Net-(U$103-CO)") (class "Default")
      (node (ref "U$103") (pin "CL_OUT") (pinfunction "CO_CL_OUT") (pintype "bidirectional"))
      (node (ref "U$106") (pin "C_IN") (pinfunction "CI_C_IN") (pintype "bidirectional"))
    )
    (net (code "218") (name "Net-(U$103-DO)") (class "Default")
      (node (ref "U$103") (pin "D_OUT") (pinfunction "DO_D_OUT") (pintype "bidirectional"))
      (node (ref "U$106") (pin "D_IN") (pinfunction "DI_D_IN") (pintype "bidirectional"))
    )
    (net (code "219") (name "Net-(U$104-CI)") (class "Default")
      (node (ref "U$104") (pin "C_IN") (pinfunction "CI_C_IN") (pintype "bidirectional"))
      (node (ref "U$130") (pin "CL_OUT") (pinfunction "CO_CL_OUT") (pintype "bidirectional"))
    )
    (net (code "220") (name "Net-(U$104-CO)") (class "Default")
      (node (ref "U$104") (pin "CL_OUT") (pinfunction "CO_CL_OUT") (pintype "bidirectional"))
      (node (ref "U$119") (pin "C_IN") (pinfunction "CI_C_IN") (pintype "bidirectional"))
    )
    (net (code "221") (name "Net-(U$104-DI)") (class "Default")
      (node (ref "U$104") (pin "D_IN") (pinfunction "DI_D_IN") (pintype "bidirectional"))
      (node (ref "U$130") (pin "D_OUT") (pinfunction "DO_D_OUT") (pintype "bidirectional"))
    )
    (net (code "222") (name "Net-(U$104-DO)") (class "Default")
      (node (ref "U$104") (pin "D_OUT") (pinfunction "DO_D_OUT") (pintype "bidirectional"))
      (node (ref "U$119") (pin "D_IN") (pinfunction "DI_D_IN") (pintype "bidirectional"))
    )
    (net (code "223") (name "Net-(U$106-CO)") (class "Default")
      (node (ref "U$106") (pin "CL_OUT") (pinfunction "CO_CL_OUT") (pintype "bidirectional"))
      (node (ref "U$107") (pin "C_IN") (pinfunction "CI_C_IN") (pintype "bidirectional"))
    )
    (net (code "224") (name "Net-(U$106-DO)") (class "Default")
      (node (ref "U$106") (pin "D_OUT") (pinfunction "DO_D_OUT") (pintype "bidirectional"))
      (node (ref "U$107") (pin "D_IN") (pinfunction "DI_D_IN") (pintype "bidirectional"))
    )
    (net (code "225") (name "Net-(U$107-CO)") (class "Default")
      (node (ref "U$107") (pin "CL_OUT") (pinfunction "CO_CL_OUT") (pintype "bidirectional"))
      (node (ref "U$108") (pin "C_IN") (pinfunction "CI_C_IN") (pintype "bidirectional"))
    )
    (net (code "226") (name "Net-(U$107-DO)") (class "Default")
      (node (ref "U$107") (pin "D_OUT") (pinfunction "DO_D_OUT") (pintype "bidirectional"))
      (node (ref "U$108") (pin "D_IN") (pinfunction "DI_D_IN") (pintype "bidirectional"))
    )
    (net (code "227") (name "Net-(U$108-CO)") (class "Default")
      (node (ref "U$108") (pin "CL_OUT") (pinfunction "CO_CL_OUT") (pintype "bidirectional"))
      (node (ref "U$109") (pin "C_IN") (pinfunction "CI_C_IN") (pintype "bidirectional"))
    )
    (net (code "228") (name "Net-(U$108-DO)") (class "Default")
      (node (ref "U$108") (pin "D_OUT") (pinfunction "DO_D_OUT") (pintype "bidirectional"))
      (node (ref "U$109") (pin "D_IN") (pinfunction "DI_D_IN") (pintype "bidirectional"))
    )
    (net (code "229") (name "Net-(U$109-CO)") (class "Default")
      (node (ref "U$109") (pin "CL_OUT") (pinfunction "CO_CL_OUT") (pintype "bidirectional"))
      (node (ref "U$110") (pin "C_IN") (pinfunction "CI_C_IN") (pintype "bidirectional"))
    )
    (net (code "230") (name "Net-(U$109-DO)") (class "Default")
      (node (ref "U$109") (pin "D_OUT") (pinfunction "DO_D_OUT") (pintype "bidirectional"))
      (node (ref "U$110") (pin "D_IN") (pinfunction "DI_D_IN") (pintype "bidirectional"))
    )
    (net (code "231") (name "Net-(U$110-CO)") (class "Default")
      (node (ref "U$110") (pin "CL_OUT") (pinfunction "CO_CL_OUT") (pintype "bidirectional"))
      (node (ref "U$111") (pin "C_IN") (pinfunction "CI_C_IN") (pintype "bidirectional"))
    )
    (net (code "232") (name "Net-(U$110-DO)") (class "Default")
      (node (ref "U$110") (pin "D_OUT") (pinfunction "DO_D_OUT") (pintype "bidirectional"))
      (node (ref "U$111") (pin "D_IN") (pinfunction "DI_D_IN") (pintype "bidirectional"))
    )
    (net (code "233") (name "Net-(U$111-CO)") (class "Default")
      (node (ref "U$111") (pin "CL_OUT") (pinfunction "CO_CL_OUT") (pintype "bidirectional"))
      (node (ref "U$112") (pin "C_IN") (pinfunction "CI_C_IN") (pintype "bidirectional"))
    )
    (net (code "234") (name "Net-(U$111-DO)") (class "Default")
      (node (ref "U$111") (pin "D_OUT") (pinfunction "DO_D_OUT") (pintype "bidirectional"))
      (node (ref "U$112") (pin "D_IN") (pinfunction "DI_D_IN") (pintype "bidirectional"))
    )
    (net (code "235") (name "Net-(U$112-CO)") (class "Default")
      (node (ref "U$112") (pin "CL_OUT") (pinfunction "CO_CL_OUT") (pintype "bidirectional"))
      (node (ref "U$113") (pin "C_IN") (pinfunction "CI_C_IN") (pintype "bidirectional"))
    )
    (net (code "236") (name "Net-(U$112-DO)") (class "Default")
      (node (ref "U$112") (pin "D_OUT") (pinfunction "DO_D_OUT") (pintype "bidirectional"))
      (node (ref "U$113") (pin "D_IN") (pinfunction "DI_D_IN") (pintype "bidirectional"))
    )
    (net (code "237") (name "Net-(U$113-CO)") (class "Default")
      (node (ref "U$113") (pin "CL_OUT") (pinfunction "CO_CL_OUT") (pintype "bidirectional"))
      (node (ref "U$114") (pin "C_IN") (pinfunction "CI_C_IN") (pintype "bidirectional"))
    )
    (net (code "238") (name "Net-(U$113-DO)") (class "Default")
      (node (ref "U$113") (pin "D_OUT") (pinfunction "DO_D_OUT") (pintype "bidirectional"))
      (node (ref "U$114") (pin "D_IN") (pinfunction "DI_D_IN") (pintype "bidirectional"))
    )
    (net (code "239") (name "Net-(U$114-CO)") (class "Default")
      (node (ref "U$114") (pin "CL_OUT") (pinfunction "CO_CL_OUT") (pintype "bidirectional"))
      (node (ref "U$115") (pin "C_IN") (pinfunction "CI_C_IN") (pintype "bidirectional"))
    )
    (net (code "240") (name "Net-(U$114-DO)") (class "Default")
      (node (ref "U$114") (pin "D_OUT") (pinfunction "DO_D_OUT") (pintype "bidirectional"))
      (node (ref "U$115") (pin "D_IN") (pinfunction "DI_D_IN") (pintype "bidirectional"))
    )
    (net (code "241") (name "Net-(U$115-CO)") (class "Default")
      (node (ref "U$115") (pin "CL_OUT") (pinfunction "CO_CL_OUT") (pintype "bidirectional"))
      (node (ref "U$116") (pin "C_IN") (pinfunction "CI_C_IN") (pintype "bidirectional"))
    )
    (net (code "242") (name "Net-(U$115-DO)") (class "Default")
      (node (ref "U$115") (pin "D_OUT") (pinfunction "DO_D_OUT") (pintype "bidirectional"))
      (node (ref "U$116") (pin "D_IN") (pinfunction "DI_D_IN") (pintype "bidirectional"))
    )
    (net (code "243") (name "Net-(U$116-CO)") (class "Default")
      (node (ref "U$116") (pin "CL_OUT") (pinfunction "CO_CL_OUT") (pintype "bidirectional"))
      (node (ref "U$117") (pin "C_IN") (pinfunction "CI_C_IN") (pintype "bidirectional"))
    )
    (net (code "244") (name "Net-(U$116-DO)") (class "Default")
      (node (ref "U$116") (pin "D_OUT") (pinfunction "DO_D_OUT") (pintype "bidirectional"))
      (node (ref "U$117") (pin "D_IN") (pinfunction "DI_D_IN") (pintype "bidirectional"))
    )
    (net (code "245") (name "Net-(U$117-CO)") (class "Default")
      (node (ref "U$117") (pin "CL_OUT") (pinfunction "CO_CL_OUT") (pintype "bidirectional"))
      (node (ref "U$118") (pin "C_IN") (pinfunction "CI_C_IN") (pintype "bidirectional"))
    )
    (net (code "246") (name "Net-(U$117-DO)") (class "Default")
      (node (ref "U$117") (pin "D_OUT") (pinfunction "DO_D_OUT") (pintype "bidirectional"))
      (node (ref "U$118") (pin "D_IN") (pinfunction "DI_D_IN") (pintype "bidirectional"))
    )
    (net (code "247") (name "Net-(U$119-CO)") (class "Default")
      (node (ref "U$119") (pin "CL_OUT") (pinfunction "CO_CL_OUT") (pintype "bidirectional"))
      (node (ref "U$120") (pin "C_IN") (pinfunction "CI_C_IN") (pintype "bidirectional"))
    )
    (net (code "248") (name "Net-(U$119-DO)") (class "Default")
      (node (ref "U$119") (pin "D_OUT") (pinfunction "DO_D_OUT") (pintype "bidirectional"))
      (node (ref "U$120") (pin "D_IN") (pinfunction "DI_D_IN") (pintype "bidirectional"))
    )
    (net (code "249") (name "Net-(U$120-CO)") (class "Default")
      (node (ref "U$120") (pin "CL_OUT") (pinfunction "CO_CL_OUT") (pintype "bidirectional"))
      (node (ref "U$121") (pin "C_IN") (pinfunction "CI_C_IN") (pintype "bidirectional"))
    )
    (net (code "250") (name "Net-(U$120-DO)") (class "Default")
      (node (ref "U$120") (pin "D_OUT") (pinfunction "DO_D_OUT") (pintype "bidirectional"))
      (node (ref "U$121") (pin "D_IN") (pinfunction "DI_D_IN") (pintype "bidirectional"))
    )
    (net (code "251") (name "Net-(U$121-CO)") (class "Default")
      (node (ref "U$121") (pin "CL_OUT") (pinfunction "CO_CL_OUT") (pintype "bidirectional"))
      (node (ref "U$122") (pin "C_IN") (pinfunction "CI_C_IN") (pintype "bidirectional"))
    )
    (net (code "252") (name "Net-(U$121-DO)") (class "Default")
      (node (ref "U$121") (pin "D_OUT") (pinfunction "DO_D_OUT") (pintype "bidirectional"))
      (node (ref "U$122") (pin "D_IN") (pinfunction "DI_D_IN") (pintype "bidirectional"))
    )
    (net (code "253") (name "Net-(U$122-CO)") (class "Default")
      (node (ref "U$122") (pin "CL_OUT") (pinfunction "CO_CL_OUT") (pintype "bidirectional"))
      (node (ref "U$123") (pin "C_IN") (pinfunction "CI_C_IN") (pintype "bidirectional"))
    )
    (net (code "254") (name "Net-(U$122-DO)") (class "Default")
      (node (ref "U$122") (pin "D_OUT") (pinfunction "DO_D_OUT") (pintype "bidirectional"))
      (node (ref "U$123") (pin "D_IN") (pinfunction "DI_D_IN") (pintype "bidirectional"))
    )
    (net (code "255") (name "Net-(U$123-CO)") (class "Default")
      (node (ref "U$123") (pin "CL_OUT") (pinfunction "CO_CL_OUT") (pintype "bidirectional"))
      (node (ref "U$124") (pin "C_IN") (pinfunction "CI_C_IN") (pintype "bidirectional"))
    )
    (net (code "256") (name "Net-(U$123-DO)") (class "Default")
      (node (ref "U$123") (pin "D_OUT") (pinfunction "DO_D_OUT") (pintype "bidirectional"))
      (node (ref "U$124") (pin "D_IN") (pinfunction "DI_D_IN") (pintype "bidirectional"))
    )
    (net (code "257") (name "Net-(U$124-CO)") (class "Default")
      (node (ref "U$124") (pin "CL_OUT") (pinfunction "CO_CL_OUT") (pintype "bidirectional"))
      (node (ref "U$125") (pin "C_IN") (pinfunction "CI_C_IN") (pintype "bidirectional"))
    )
    (net (code "258") (name "Net-(U$124-DO)") (class "Default")
      (node (ref "U$124") (pin "D_OUT") (pinfunction "DO_D_OUT") (pintype "bidirectional"))
      (node (ref "U$125") (pin "D_IN") (pinfunction "DI_D_IN") (pintype "bidirectional"))
    )
    (net (code "259") (name "Net-(U$125-CO)") (class "Default")
      (node (ref "U$125") (pin "CL_OUT") (pinfunction "CO_CL_OUT") (pintype "bidirectional"))
      (node (ref "U$126") (pin "C_IN") (pinfunction "CI_C_IN") (pintype "bidirectional"))
    )
    (net (code "260") (name "Net-(U$125-DO)") (class "Default")
      (node (ref "U$125") (pin "D_OUT") (pinfunction "DO_D_OUT") (pintype "bidirectional"))
      (node (ref "U$126") (pin "D_IN") (pinfunction "DI_D_IN") (pintype "bidirectional"))
    )
    (net (code "261") (name "Net-(U$126-CO)") (class "Default")
      (node (ref "U$126") (pin "CL_OUT") (pinfunction "CO_CL_OUT") (pintype "bidirectional"))
      (node (ref "U$127") (pin "C_IN") (pinfunction "CI_C_IN") (pintype "bidirectional"))
    )
    (net (code "262") (name "Net-(U$126-DO)") (class "Default")
      (node (ref "U$126") (pin "D_OUT") (pinfunction "DO_D_OUT") (pintype "bidirectional"))
      (node (ref "U$127") (pin "D_IN") (pinfunction "DI_D_IN") (pintype "bidirectional"))
    )
    (net (code "263") (name "Net-(U$127-CO)") (class "Default")
      (node (ref "U$127") (pin "CL_OUT") (pinfunction "CO_CL_OUT") (pintype "bidirectional"))
      (node (ref "U$128") (pin "C_IN") (pinfunction "CI_C_IN") (pintype "bidirectional"))
    )
    (net (code "264") (name "Net-(U$127-DO)") (class "Default")
      (node (ref "U$127") (pin "D_OUT") (pinfunction "DO_D_OUT") (pintype "bidirectional"))
      (node (ref "U$128") (pin "D_IN") (pinfunction "DI_D_IN") (pintype "bidirectional"))
    )
    (net (code "265") (name "Net-(U$128-CO)") (class "Default")
      (node (ref "U$128") (pin "CL_OUT") (pinfunction "CO_CL_OUT") (pintype "bidirectional"))
      (node (ref "U$129") (pin "C_IN") (pinfunction "CI_C_IN") (pintype "bidirectional"))
    )
    (net (code "266") (name "Net-(U$128-DO)") (class "Default")
      (node (ref "U$128") (pin "D_OUT") (pinfunction "DO_D_OUT") (pintype "bidirectional"))
      (node (ref "U$129") (pin "D_IN") (pinfunction "DI_D_IN") (pintype "bidirectional"))
    )
    (net (code "267") (name "Net-(U$129-CO)") (class "Default")
      (node (ref "U$129") (pin "CL_OUT") (pinfunction "CO_CL_OUT") (pintype "bidirectional"))
      (node (ref "U$32") (pin "C_IN") (pinfunction "CI_C_IN") (pintype "bidirectional"))
    )
    (net (code "268") (name "Net-(U$129-DO)") (class "Default")
      (node (ref "U$129") (pin "D_OUT") (pinfunction "DO_D_OUT") (pintype "bidirectional"))
      (node (ref "U$32") (pin "D_IN") (pinfunction "DI_D_IN") (pintype "bidirectional"))
    )
    (net (code "269") (name "Net-(U$130-CI)") (class "Default")
      (node (ref "U$130") (pin "C_IN") (pinfunction "CI_C_IN") (pintype "bidirectional"))
      (node (ref "U$31") (pin "CL_OUT") (pinfunction "CO_CL_OUT") (pintype "bidirectional"))
    )
    (net (code "270") (name "Net-(U$130-DI)") (class "Default")
      (node (ref "U$130") (pin "D_IN") (pinfunction "DI_D_IN") (pintype "bidirectional"))
      (node (ref "U$31") (pin "D_OUT") (pinfunction "DO_D_OUT") (pintype "bidirectional"))
    )
    (net (code "271") (name "Net-(U$131-CAPN)") (class "Default")
      (node (ref "C20") (pin "2") (pinfunction "2_2") (pintype "passive"))
      (node (ref "U$131") (pin "10") (pinfunction "CAPN_10") (pintype "bidirectional"))
    )
    (net (code "272") (name "Net-(U$131-CAPP)") (class "Default")
      (node (ref "C20") (pin "1") (pinfunction "1_1") (pintype "passive"))
      (node (ref "U$131") (pin "9") (pinfunction "CAPP_9") (pintype "bidirectional"))
    )
    (net (code "273") (name "Net-(U$131-CPLL)") (class "Default")
      (node (ref "C68") (pin "1") (pinfunction "1_1") (pintype "passive"))
      (node (ref "U$131") (pin "11") (pinfunction "CPLL_11") (pintype "bidirectional"))
    )
    (net (code "274") (name "Net-(U$131-VBG)") (class "Default")
      (node (ref "C73") (pin "1") (pinfunction "1_1") (pintype "passive"))
      (node (ref "U$131") (pin "27") (pinfunction "VBG_27") (pintype "bidirectional"))
    )
    (net (code "275") (name "Net-(U$131-VCM)") (class "Default")
      (node (ref "C71") (pin "1") (pinfunction "1_1") (pintype "passive"))
      (node (ref "U$131") (pin "25") (pinfunction "VCM_25") (pintype "bidirectional"))
    )
    (net (code "276") (name "Net-(U$131-VREF)") (class "Default")
      (node (ref "C70") (pin "1") (pinfunction "1_1") (pintype "passive"))
      (node (ref "U$131") (pin "23") (pinfunction "VREF_23") (pintype "bidirectional"))
    )
    (net (code "277") (name "Net-(U1-USBDM)") (class "Default")
      (node (ref "R14") (pin "2") (pinfunction "2_2") (pintype "passive"))
      (node (ref "U1") (pin "12") (pinfunction "USBDM_12") (pintype "bidirectional"))
    )
    (net (code "278") (name "Net-(U1-USBDP)") (class "Default")
      (node (ref "R15") (pin "2") (pinfunction "2_2") (pintype "passive"))
      (node (ref "U1") (pin "11") (pinfunction "USBDP_11") (pintype "bidirectional"))
    )
    (net (code "279") (name "Net-(U3-PROG)") (class "Default")
      (node (ref "R17") (pin "2") (pinfunction "2_2") (pintype "passive"))
      (node (ref "U3") (pin "5") (pinfunction "PROG_5") (pintype "input"))
    )
    (net (code "280") (name "Net-(U3-STAT)") (class "Default")
      (node (ref "CHG2") (pin "C") (pinfunction "C_C") (pintype "passive"))
      (node (ref "U3") (pin "1") (pinfunction "STAT_1") (pintype "output"))
    )
    (net (code "281") (name "RTS") (class "Default")
      (node (ref "Q1") (pin "4") (pinfunction "E_4") (pintype "passive"))
      (node (ref "R10") (pin "1") (pinfunction "1_1") (pintype "passive"))
      (node (ref "U1") (pin "2") (pinfunction "~{RTS}_2") (pintype "bidirectional"))
    )
    (net (code "282") (name "RXD") (class "Default")
      (node (ref "R13") (pin "2") (pinfunction "2_2") (pintype "passive"))
      (node (ref "U1") (pin "4") (pinfunction "RXD_4") (pintype "bidirectional"))
    )
    (net (code "283") (name "SCL") (class "Default")
      (node (ref "IC1") (pin "39") (pinfunction "IO22_39") (pintype "bidirectional"))
      (node (ref "R7") (pin "1") (pinfunction "1_1") (pintype "passive"))
      (node (ref "U2") (pin "13") (pinfunction "SCL_13") (pintype "bidirectional"))
    )
    (net (code "284") (name "SCLK") (class "Default")
      (node (ref "IC1") (pin "35") (pinfunction "IO18_35") (pintype "bidirectional"))
      (node (ref "U$131") (pin "16") (pinfunction "SCLK_16") (pintype "bidirectional"))
    )
    (net (code "285") (name "SDA") (class "Default")
      (node (ref "IC1") (pin "42") (pinfunction "IO21_42") (pintype "power_in"))
      (node (ref "R4") (pin "1") (pinfunction "1_1") (pintype "passive"))
      (node (ref "U2") (pin "14") (pinfunction "SDA_14") (pintype "bidirectional"))
    )
    (net (code "286") (name "SENSOR_CAPN") (class "Default")
      (node (ref "IC1") (pin "7") (pinfunction "SENSOR_CAPN_7") (pintype "power_in"))
    )
    (net (code "287") (name "TXD") (class "Default")
      (node (ref "R12") (pin "2") (pinfunction "2_2") (pintype "passive"))
      (node (ref "U1") (pin "20") (pinfunction "TXD_20") (pintype "bidirectional"))
    )
    (net (code "288") (name "U0RXD") (class "Default")
      (node (ref "IC1") (pin "40") (pinfunction "U0RXD_40") (pintype "bidirectional"))
      (node (ref "R12") (pin "1") (pinfunction "1_1") (pintype "passive"))
    )
    (net (code "289") (name "U0TXD") (class "Default")
      (node (ref "IC1") (pin "41") (pinfunction "U0TXD_41") (pintype "bidirectional"))
      (node (ref "R13") (pin "1") (pinfunction "1_1") (pintype "passive"))
    )
    (net (code "290") (name "VBAT") (class "Default")
      (node (ref "C65") (pin "1") (pinfunction "1_1") (pintype "passive"))
      (node (ref "Q2") (pin "3") (pinfunction "D_3") (pintype "passive"))
      (node (ref "R25") (pin "2") (pinfunction "2_2") (pintype "passive"))
      (node (ref "TP5") (pin "TP-1") (pinfunction "TP_TP-1") (pintype "input"))
      (node (ref "U3") (pin "3") (pinfunction "VBAT_3") (pintype "power_in"))
    )
    (net (code "291") (name "VIN") (class "Default")
      (node (ref "C120") (pin "2") (pinfunction "2_2") (pintype "passive"))
      (node (ref "C121") (pin "1") (pinfunction "1_1") (pintype "passive"))
      (node (ref "C63") (pin "1") (pinfunction "1_1") (pintype "passive"))
      (node (ref "C72") (pin "2") (pinfunction "2_2") (pintype "passive"))
      (node (ref "D1") (pin "C") (pinfunction "C_C") (pintype "passive"))
      (node (ref "Q2") (pin "2") (pinfunction "S_2") (pintype "passive"))
      (node (ref "R18") (pin "1") (pinfunction "1_1") (pintype "passive"))
      (node (ref "S2") (pin "3") (pinfunction "S_3") (pintype "passive"))
      (node (ref "U$2") (pin "4") (pinfunction "IN_4") (pintype "bidirectional"))
      (node (ref "U$2") (pin "6") (pinfunction "IN_6") (pintype "bidirectional"))
      (node (ref "U8") (pin "1") (pinfunction "IN_1") (pintype "input"))
      (node (ref "U9") (pin "1") (pinfunction "IN_1") (pintype "input"))
    )
    (net (code "292") (name "VUSB") (class "Default")
      (node (ref "C60") (pin "1") (pinfunction "1_1") (pintype "passive"))
      (node (ref "C61") (pin "1") (pinfunction "1_1") (pintype "passive"))
      (node (ref "C64") (pin "1") (pinfunction "1_1") (pintype "passive"))
      (node (ref "D1") (pin "A") (pinfunction "A_A") (pintype "passive"))
      (node (ref "JP7") (pin "1") (pinfunction "VCC_1") (pintype "bidirectional"))
      (node (ref "Q2") (pin "1") (pinfunction "G_1") (pintype "passive"))
      (node (ref "R16") (pin "1") (pinfunction "1_1") (pintype "passive"))
      (node (ref "R23") (pin "2") (pinfunction "2_2") (pintype "passive"))
      (node (ref "U1") (pin "15") (pinfunction "VCC_15") (pintype "bidirectional"))
      (node (ref "U3") (pin "4") (pinfunction "VIN_4") (pintype "power_in"))
    )
    (net (code "293") (name "unconnected-(IC1A-CAP1_NC-Pad48)") (class "Default")
      (node (ref "IC1") (pin "48") (pinfunction "CAP1_NC_48") (pintype "bidirectional"))
    )
    (net (code "294") (name "unconnected-(IC1A-CAP2_NC-Pad47)") (class "Default")
      (node (ref "IC1") (pin "47") (pinfunction "CAP2_NC_47") (pintype "bidirectional"))
    )
    (net (code "295") (name "unconnected-(IC1A-CLK-Pad31)") (class "Default")
      (node (ref "IC1") (pin "31") (pinfunction "CLK_31") (pintype "bidirectional"))
    )
    (net (code "296") (name "unconnected-(IC1A-CMD-Pad30)") (class "Default")
      (node (ref "IC1") (pin "30") (pinfunction "CMD_30") (pintype "bidirectional"))
    )
    (net (code "297") (name "unconnected-(IC1A-IO2-Pad22)") (class "Default")
      (node (ref "IC1") (pin "22") (pinfunction "IO2_22") (pintype "bidirectional"))
    )
    (net (code "298") (name "unconnected-(IC1A-IO5-Pad34)") (class "Default")
      (node (ref "IC1") (pin "34") (pinfunction "IO5_34") (pintype "bidirectional"))
    )
    (net (code "299") (name "unconnected-(IC1A-IO13-Pad20)") (class "Default")
      (node (ref "IC1") (pin "20") (pinfunction "IO13_20") (pintype "bidirectional"))
    )
    (net (code "300") (name "unconnected-(IC1A-IO15-Pad21)") (class "Default")
      (node (ref "IC1") (pin "21") (pinfunction "IO15_21") (pintype "bidirectional"))
    )
    (net (code "301") (name "unconnected-(IC1A-IO16-Pad25)") (class "Default")
      (node (ref "IC1") (pin "25") (pinfunction "IO16_25") (pintype "bidirectional"))
    )
    (net (code "302") (name "unconnected-(IC1A-IO17-Pad27)") (class "Default")
      (node (ref "IC1") (pin "27") (pinfunction "IO17_27") (pintype "bidirectional"))
    )
    (net (code "303") (name "unconnected-(IC1A-SD0-Pad32)") (class "Default")
      (node (ref "IC1") (pin "32") (pinfunction "SD0_32") (pintype "bidirectional"))
    )
    (net (code "304") (name "unconnected-(IC1A-SD1-Pad33)") (class "Default")
      (node (ref "IC1") (pin "33") (pinfunction "SD1_33") (pintype "bidirectional"))
    )
    (net (code "305") (name "unconnected-(IC1A-SD2-Pad28)") (class "Default")
      (node (ref "IC1") (pin "28") (pinfunction "SD2_28") (pintype "bidirectional"))
    )
    (net (code "306") (name "unconnected-(IC1A-SD3-Pad29)") (class "Default")
      (node (ref "IC1") (pin "29") (pinfunction "SD3_29") (pintype "bidirectional"))
    )
    (net (code "307") (name "unconnected-(IC1A-SENSOR_CAPP-Pad6)") (class "Default")
      (node (ref "IC1") (pin "6") (pinfunction "SENSOR_CAPP_6") (pintype "bidirectional"))
    )
    (net (code "308") (name "unconnected-(IC1A-SENSOR_VN-Pad8)") (class "Default")
      (node (ref "IC1") (pin "8") (pinfunction "SENSOR_VN_8") (pintype "bidirectional"))
    )
    (net (code "309") (name "unconnected-(IC1A-SENSOR_VP-Pad5)") (class "Default")
      (node (ref "IC1") (pin "5") (pinfunction "SENSOR_VP_5") (pintype "bidirectional"))
    )
    (net (code "310") (name "unconnected-(IC1A-XTAL_N_NC-Pad44)") (class "Default")
      (node (ref "IC1") (pin "44") (pinfunction "XTAL_N_NC_44") (pintype "bidirectional"))
    )
    (net (code "311") (name "unconnected-(IC1A-XTAL_P_NC-Pad45)") (class "Default")
      (node (ref "IC1") (pin "45") (pinfunction "XTAL_P_NC_45") (pintype "bidirectional"))
    )
    (net (code "312") (name "unconnected-(JP7-ID-Pad4)") (class "Default")
      (node (ref "JP7") (pin "4") (pinfunction "ID_4") (pintype "bidirectional"))
    )
    (net (code "313") (name "unconnected-(SW2-P1-PadA')") (class "Default")
      (node (ref "SW2") (pin "A'") (pinfunction "P1_A'") (pintype "passive"))
    )
    (net (code "314") (name "unconnected-(U$118-CO-PadCL_OUT)") (class "Default")
      (node (ref "U$118") (pin "CL_OUT") (pinfunction "CO_CL_OUT") (pintype "bidirectional"))
    )
    (net (code "315") (name "unconnected-(U$118-DO-PadD_OUT)") (class "Default")
      (node (ref "U$118") (pin "D_OUT") (pinfunction "DO_D_OUT") (pintype "bidirectional"))
    )
    (net (code "316") (name "unconnected-(U$131-INT2B-Pad20)") (class "Default")
      (node (ref "U$131") (pin "20") (pinfunction "INT2B_20") (pintype "bidirectional"))
    )
    (net (code "317") (name "unconnected-(U$134-NC-Pad1)") (class "Default")
      (node (ref "U$134") (pin "1") (pinfunction "NC_1") (pintype "bidirectional"))
    )
    (net (code "318") (name "unconnected-(U1-CBUS0-Pad18)") (class "Default")
      (node (ref "U1") (pin "18") (pinfunction "CBUS0_18") (pintype "bidirectional"))
    )
    (net (code "319") (name "unconnected-(U1-CBUS1-Pad17)") (class "Default")
      (node (ref "U1") (pin "17") (pinfunction "CBUS1_17") (pintype "bidirectional"))
    )
    (net (code "320") (name "unconnected-(U1-CBUS2-Pad10)") (class "Default")
      (node (ref "U1") (pin "10") (pinfunction "CBUS2_10") (pintype "bidirectional"))
    )
    (net (code "321") (name "unconnected-(U1-CBUS3-Pad19)") (class "Default")
      (node (ref "U1") (pin "19") (pinfunction "CBUS3_19") (pintype "bidirectional"))
    )
    (net (code "322") (name "unconnected-(U1-~{CTS}-Pad9)") (class "Default")
      (node (ref "U1") (pin "9") (pinfunction "~{CTS}_9") (pintype "bidirectional"))
    )
    (net (code "323") (name "unconnected-(U1-~{DCD}-Pad8)") (class "Default")
      (node (ref "U1") (pin "8") (pinfunction "~{DCD}_8") (pintype "bidirectional"))
    )
    (net (code "324") (name "unconnected-(U1-~{DSR}-Pad7)") (class "Default")
      (node (ref "U1") (pin "7") (pinfunction "~{DSR}_7") (pintype "bidirectional"))
    )
    (net (code "325") (name "unconnected-(U1-~{RI}-Pad5)") (class "Default")
      (node (ref "U1") (pin "5") (pinfunction "~{RI}_5") (pintype "bidirectional"))
    )
    (net (code "326") (name "unconnected-(U2-INT1-Pad4)") (class "Default")
      (node (ref "U2") (pin "4") (pinfunction "INT1_4") (pintype "bidirectional"))
    )
    (net (code "327") (name "unconnected-(U2-INT2-Pad9)") (class "Default")
      (node (ref "U2") (pin "9") (pinfunction "INT2_9") (pintype "bidirectional"))
    )
    (net (code "328") (name "unconnected-(U2-NC-Pad11)") (class "Default")
      (node (ref "U2") (pin "11") (pinfunction "NC_11") (pintype "bidirectional"))
    )
    (net (code "329") (name "unconnected-(U2-OCS-Pad10)") (class "Default")
      (node (ref "U2") (pin "10") (pinfunction "OCS_10") (pintype "bidirectional"))
    )
    (net (code "330") (name "unconnected-(U8-BP-Pad4)") (class "Default")
      (node (ref "U8") (pin "4") (pinfunction "BP_4") (pintype "input"))
    )
    (net (code "331") (name "unconnected-(U9-BP-Pad4)") (class "Default")
      (node (ref "U9") (pin "4") (pinfunction "BP_4") (pintype "input"))
    )
  )
)
